# schem.net
KiCad netlist of a schematic drawn in EAGLE
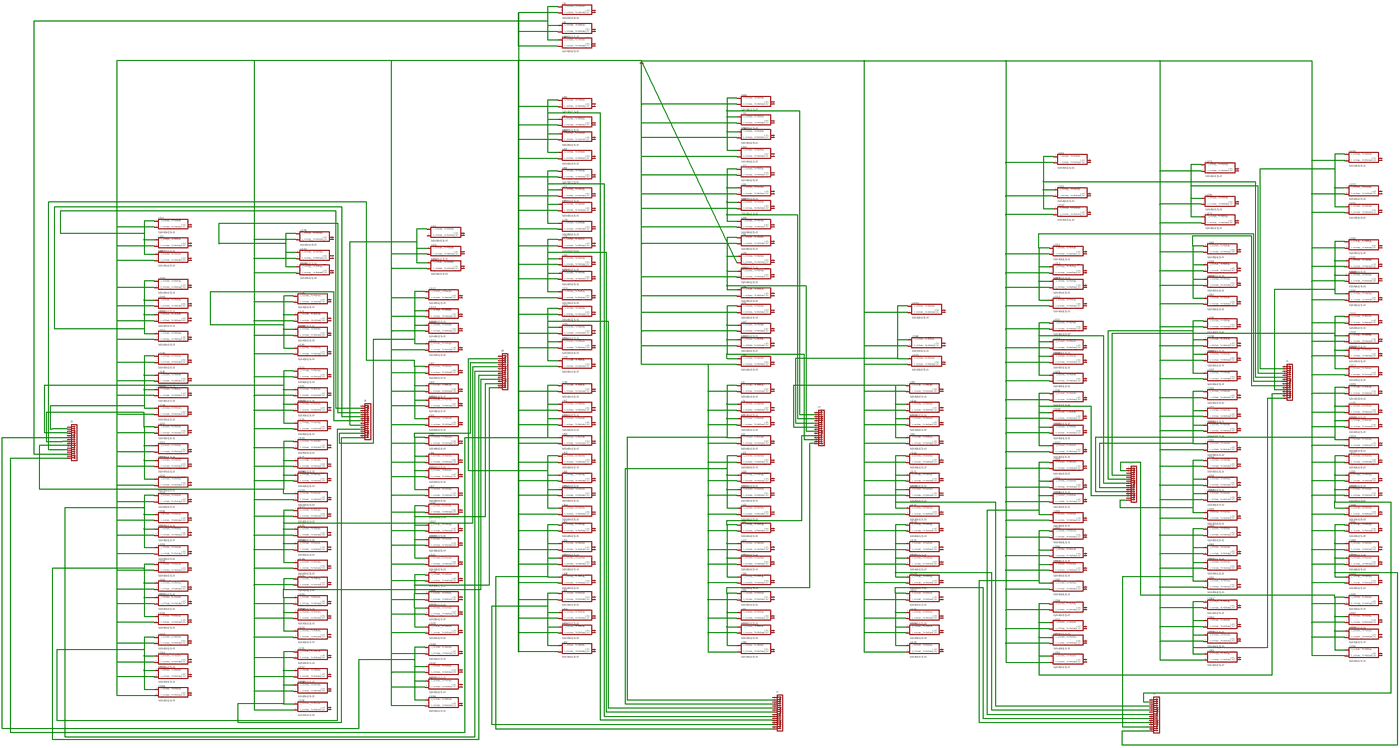
[diagram p0: schematic, sheet 1, overview]
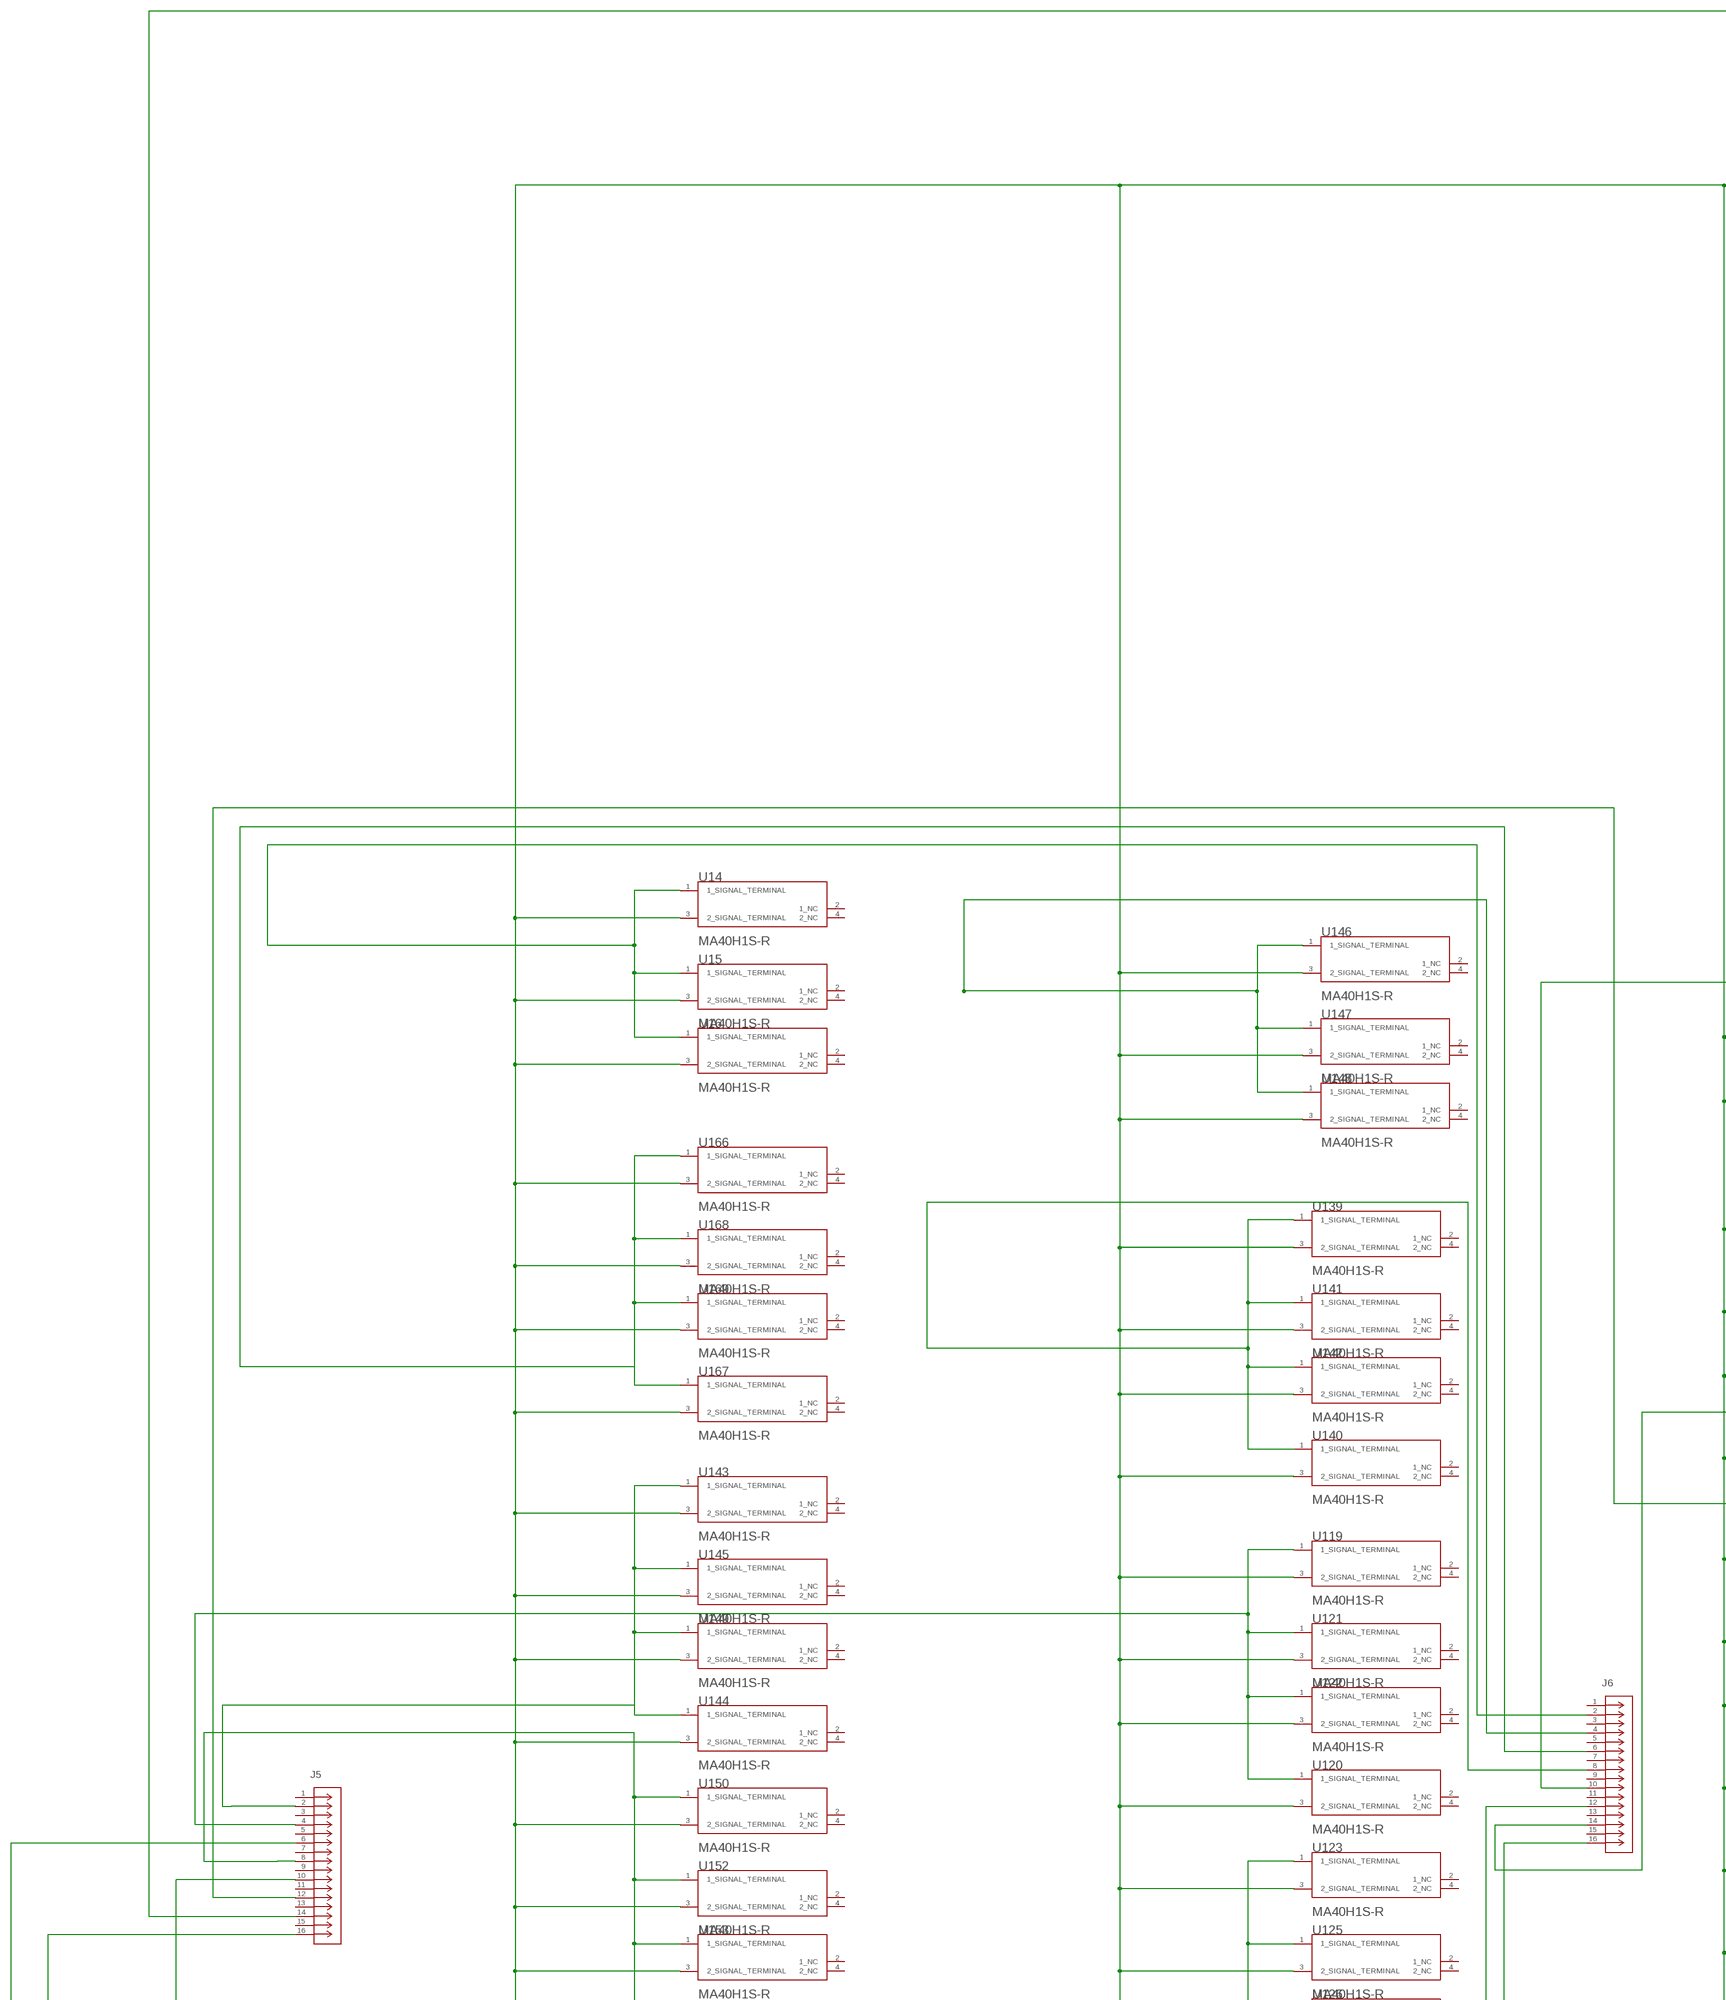
[diagram p1: schematic, sheet 1, part 1 of 8]
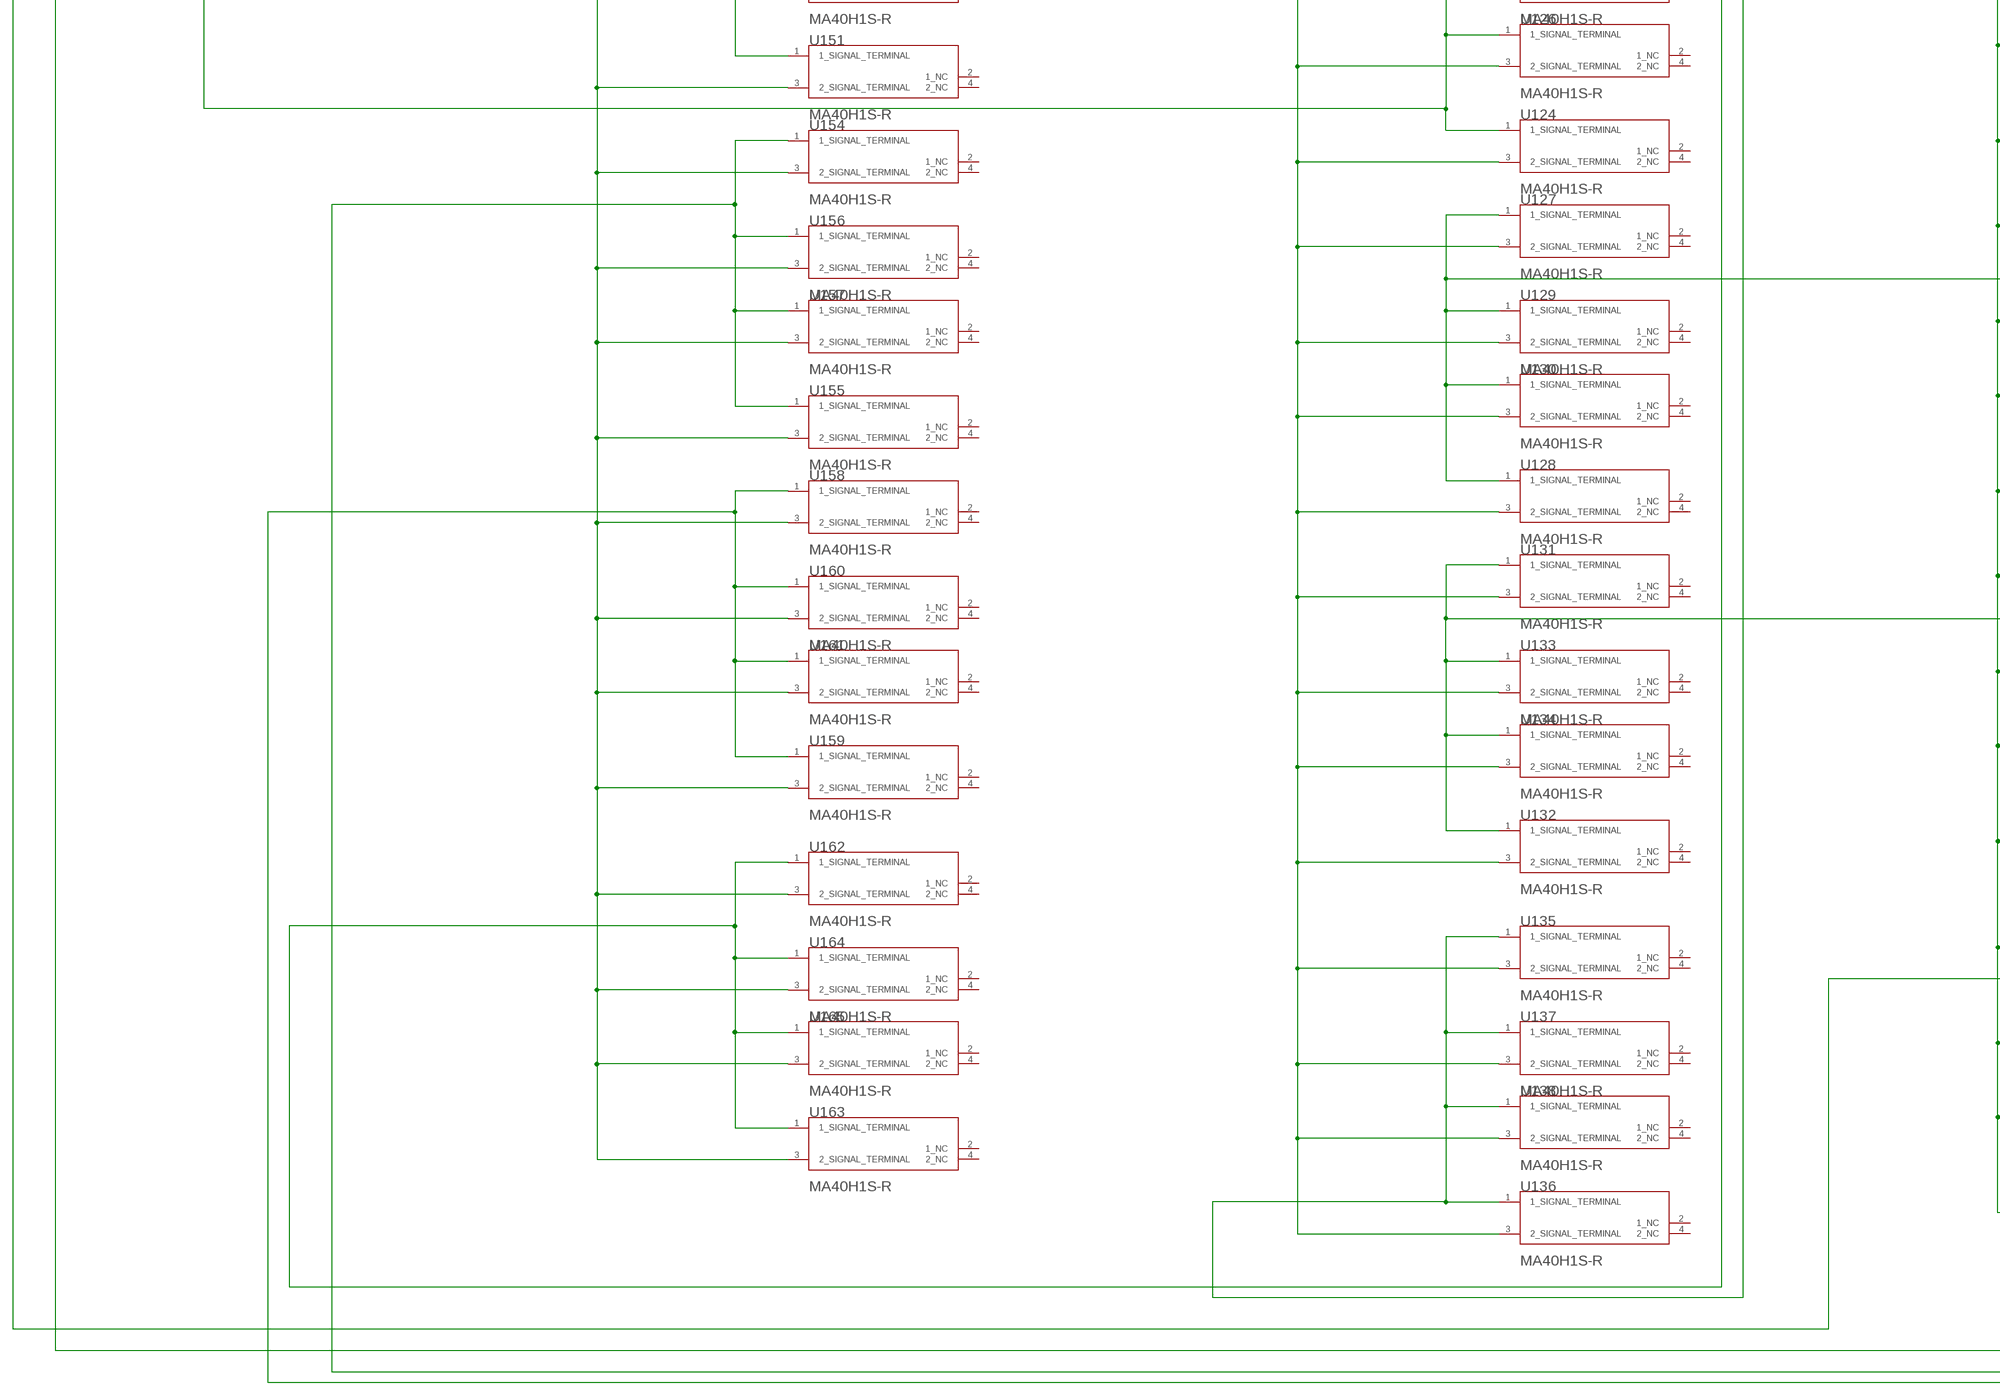
[diagram p2: schematic, sheet 1, part 2 of 8]
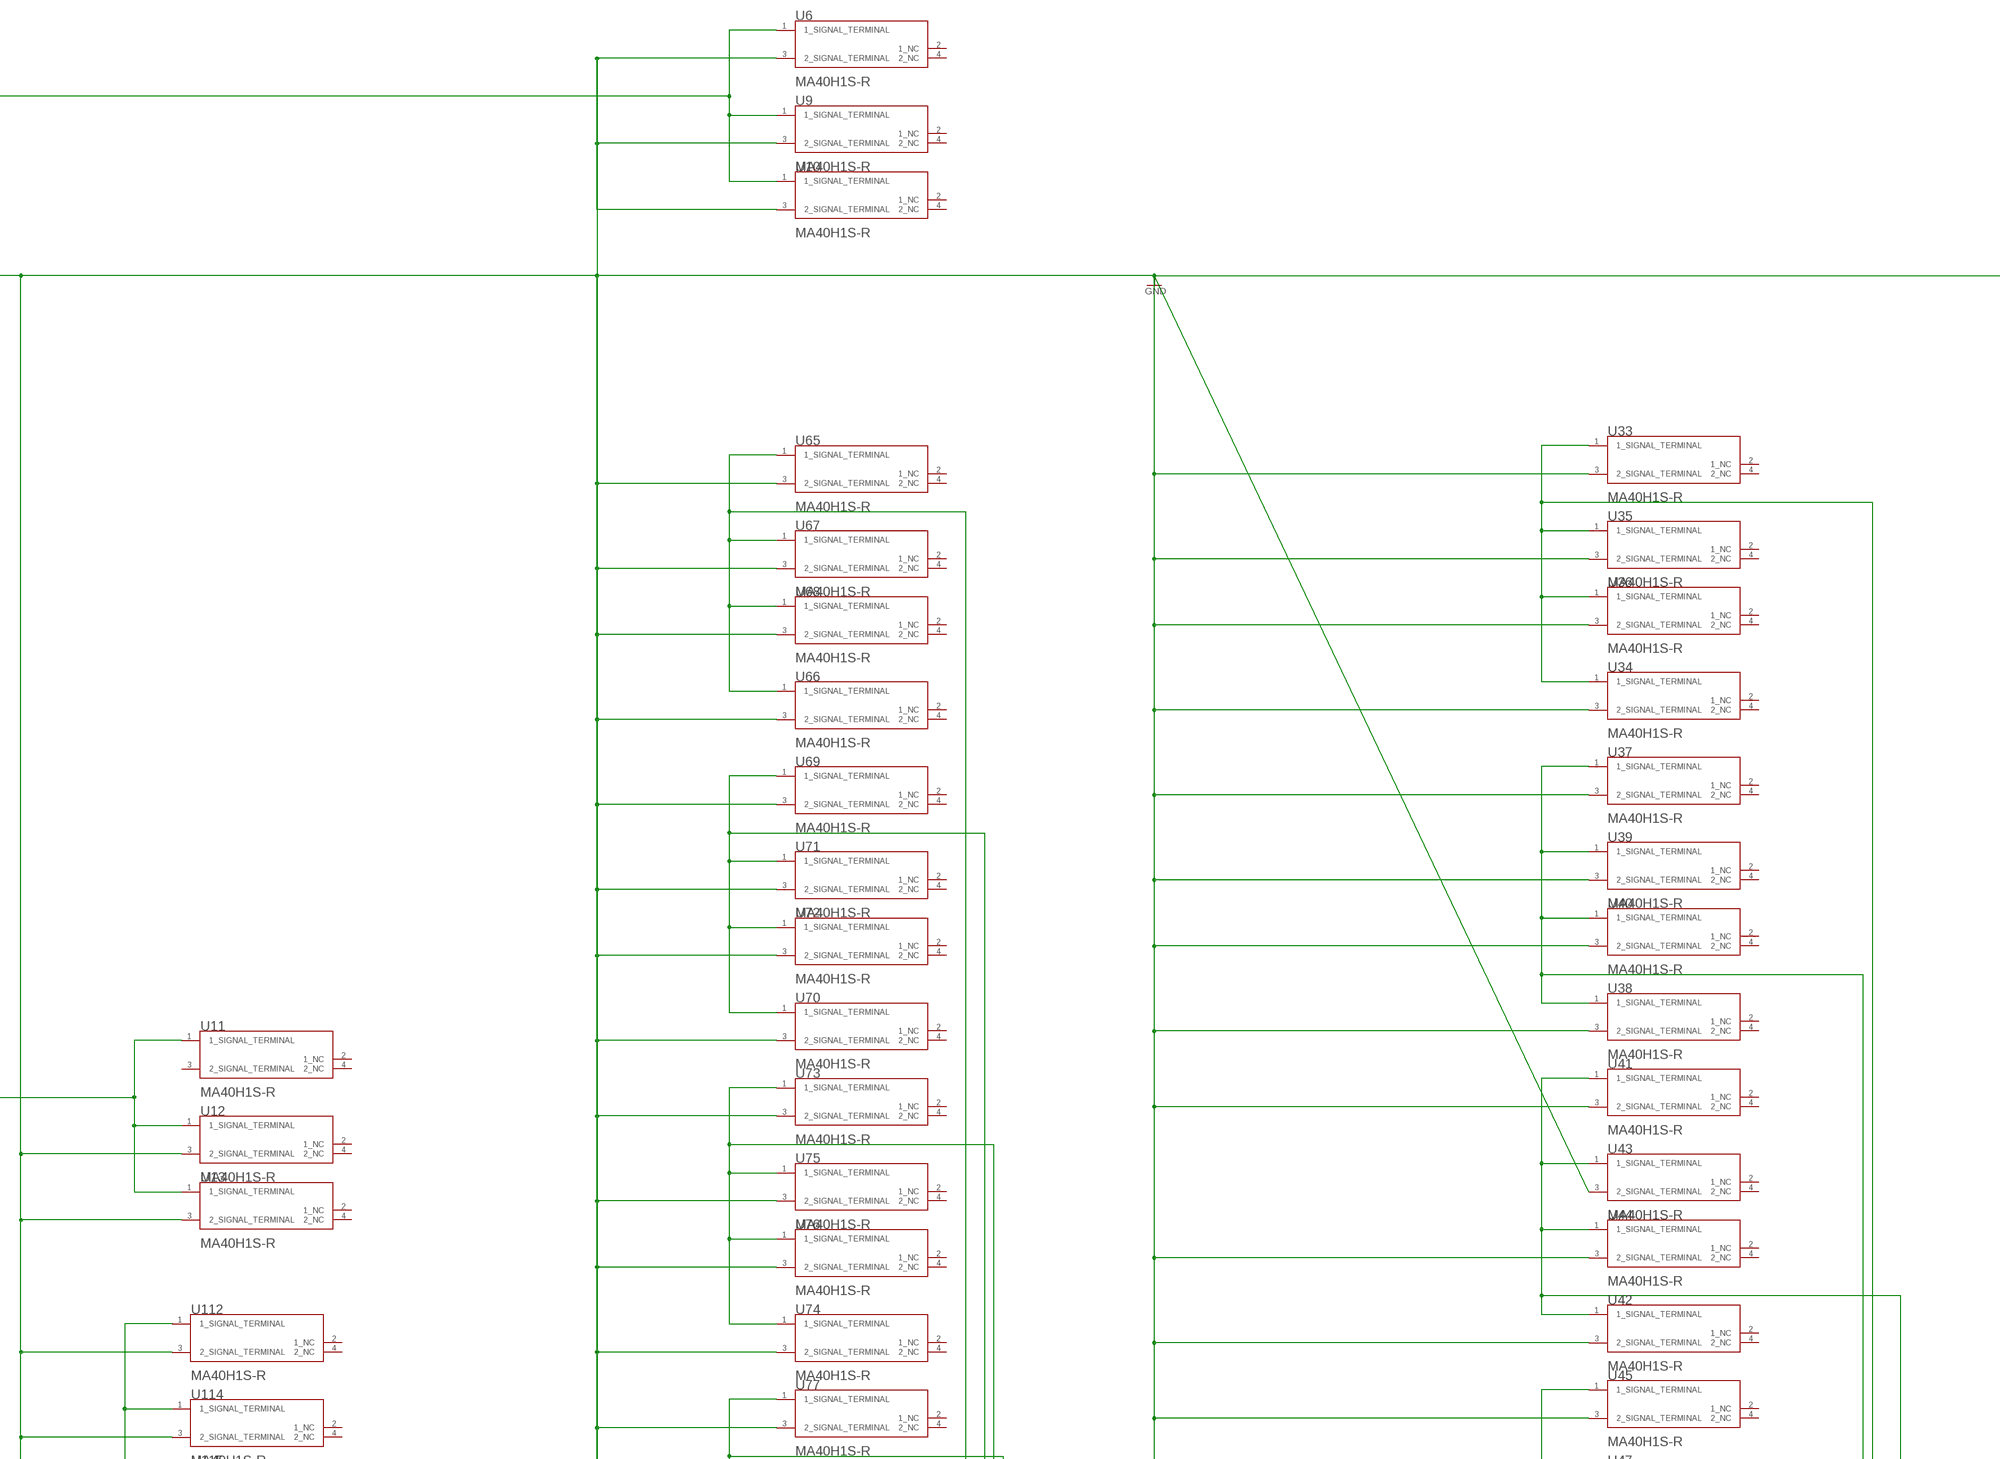
[diagram p3: schematic, sheet 1, part 3 of 8]
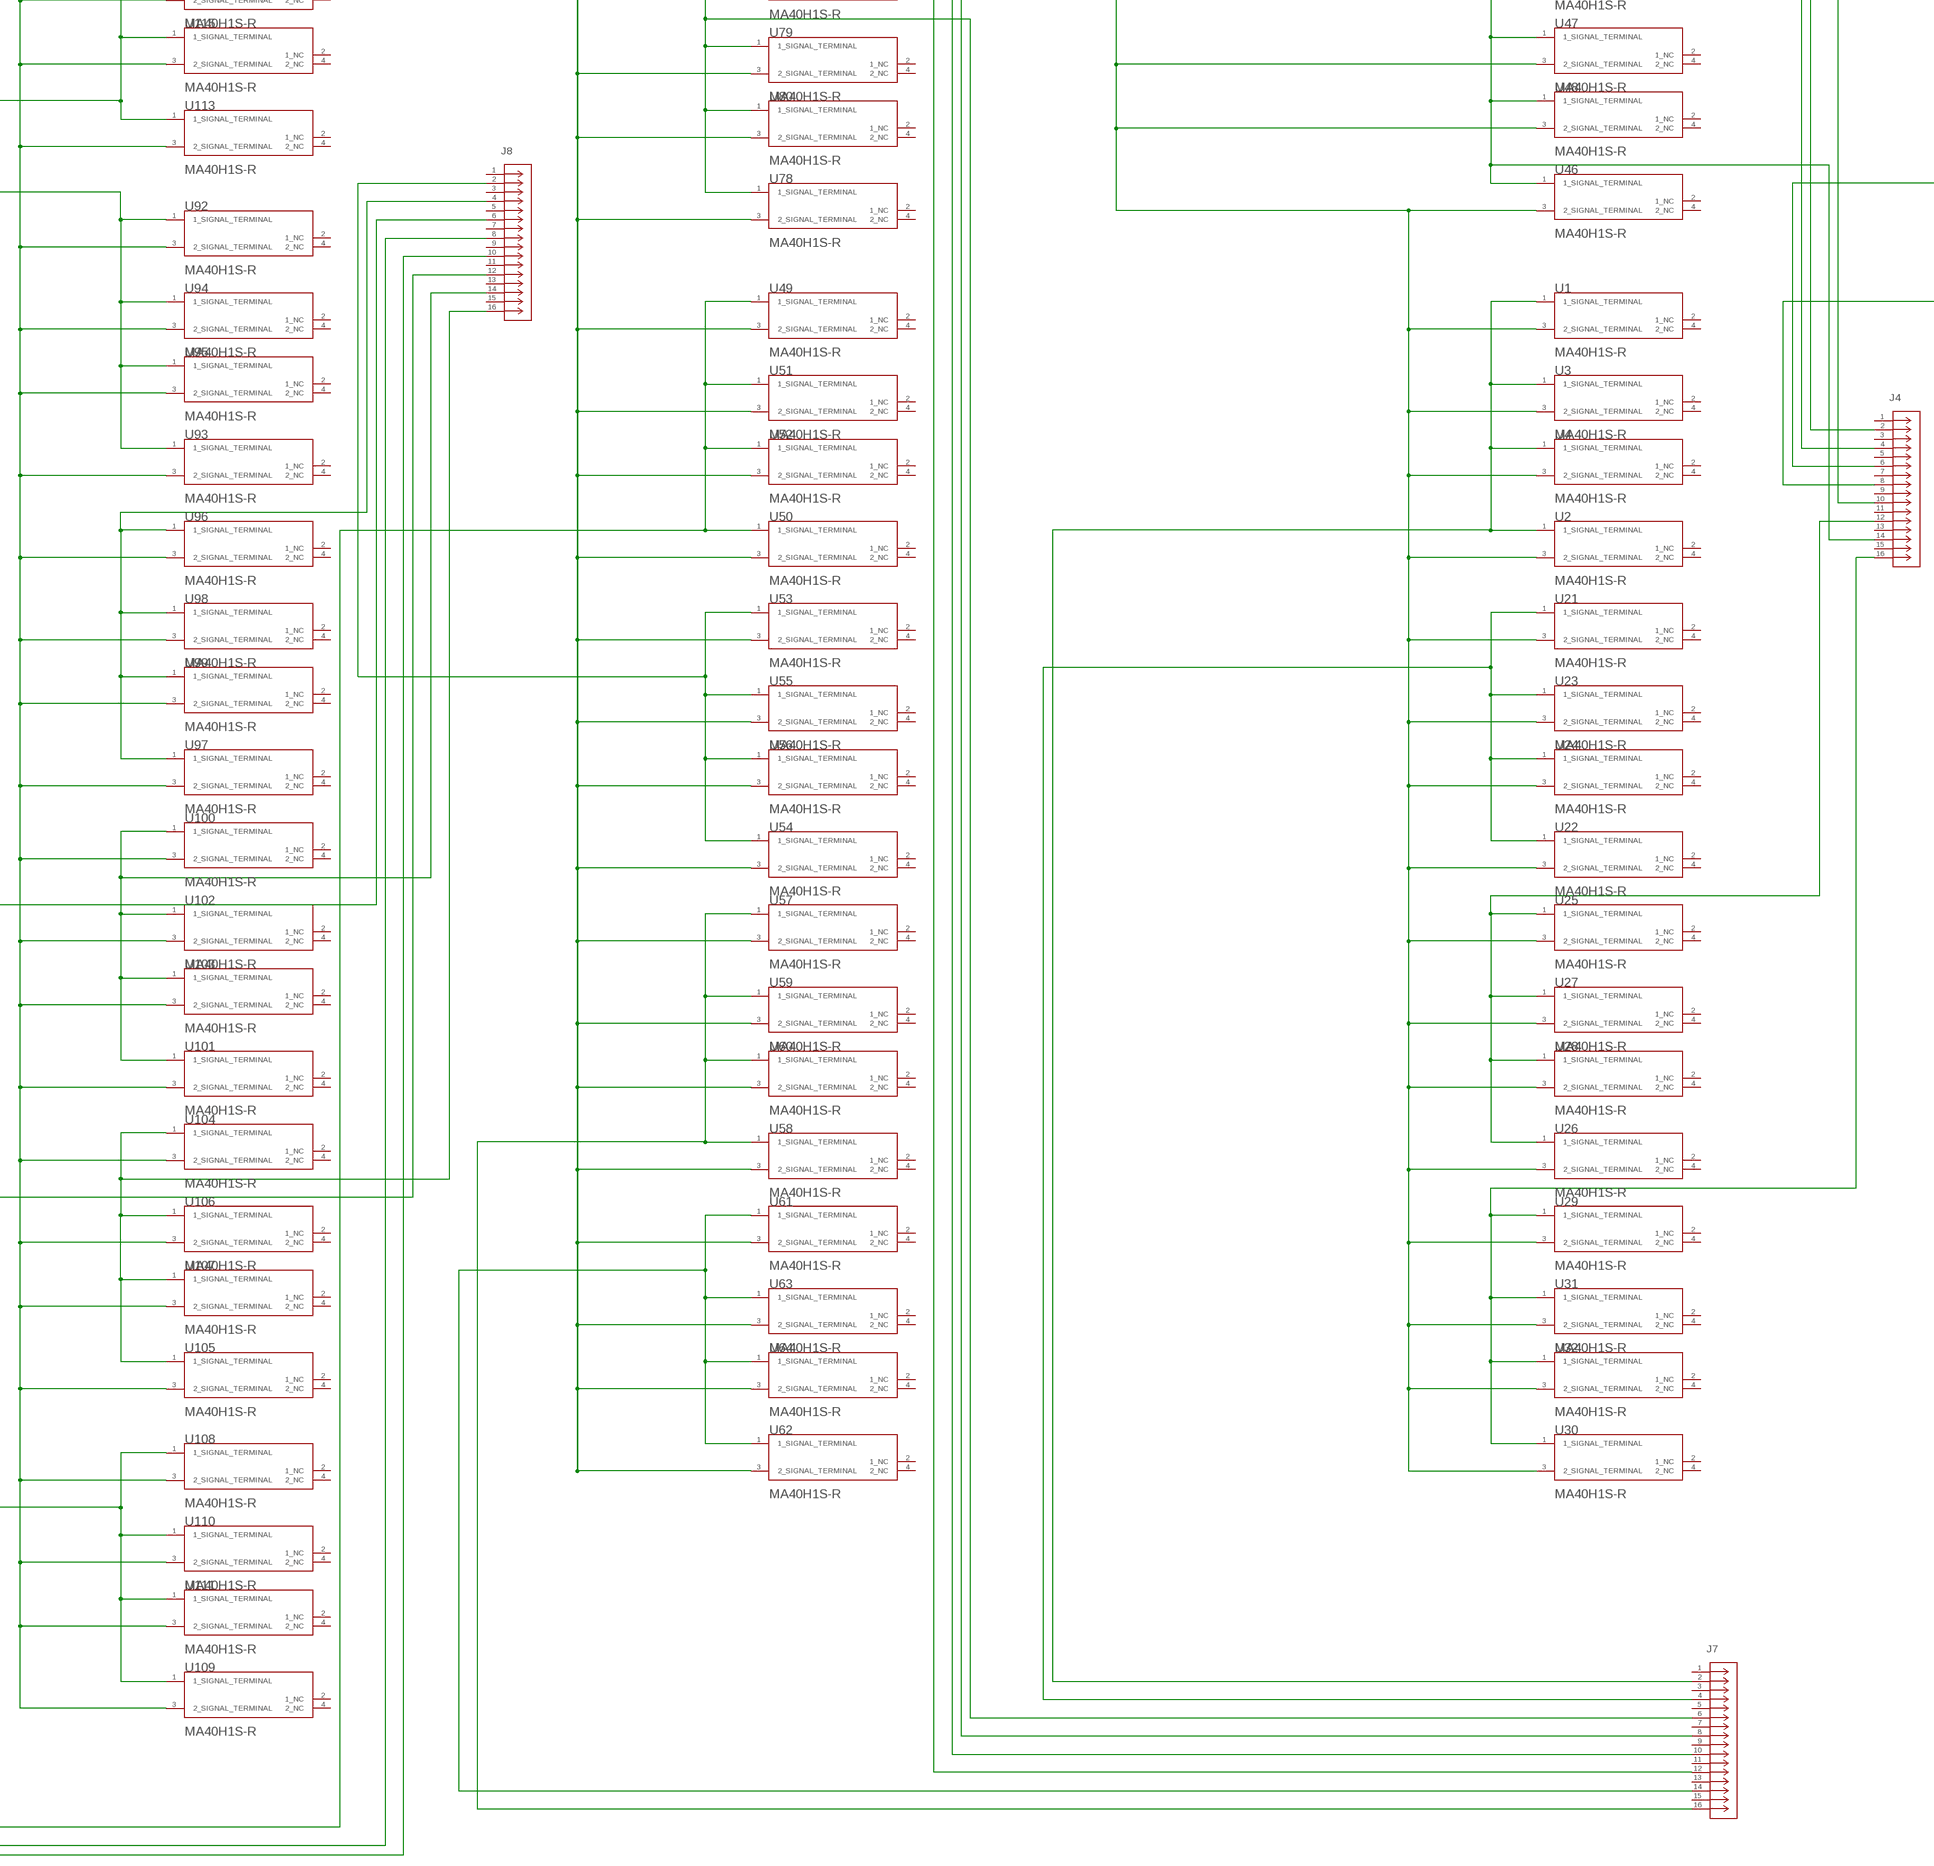
[diagram p4: schematic, sheet 1, part 4 of 8]
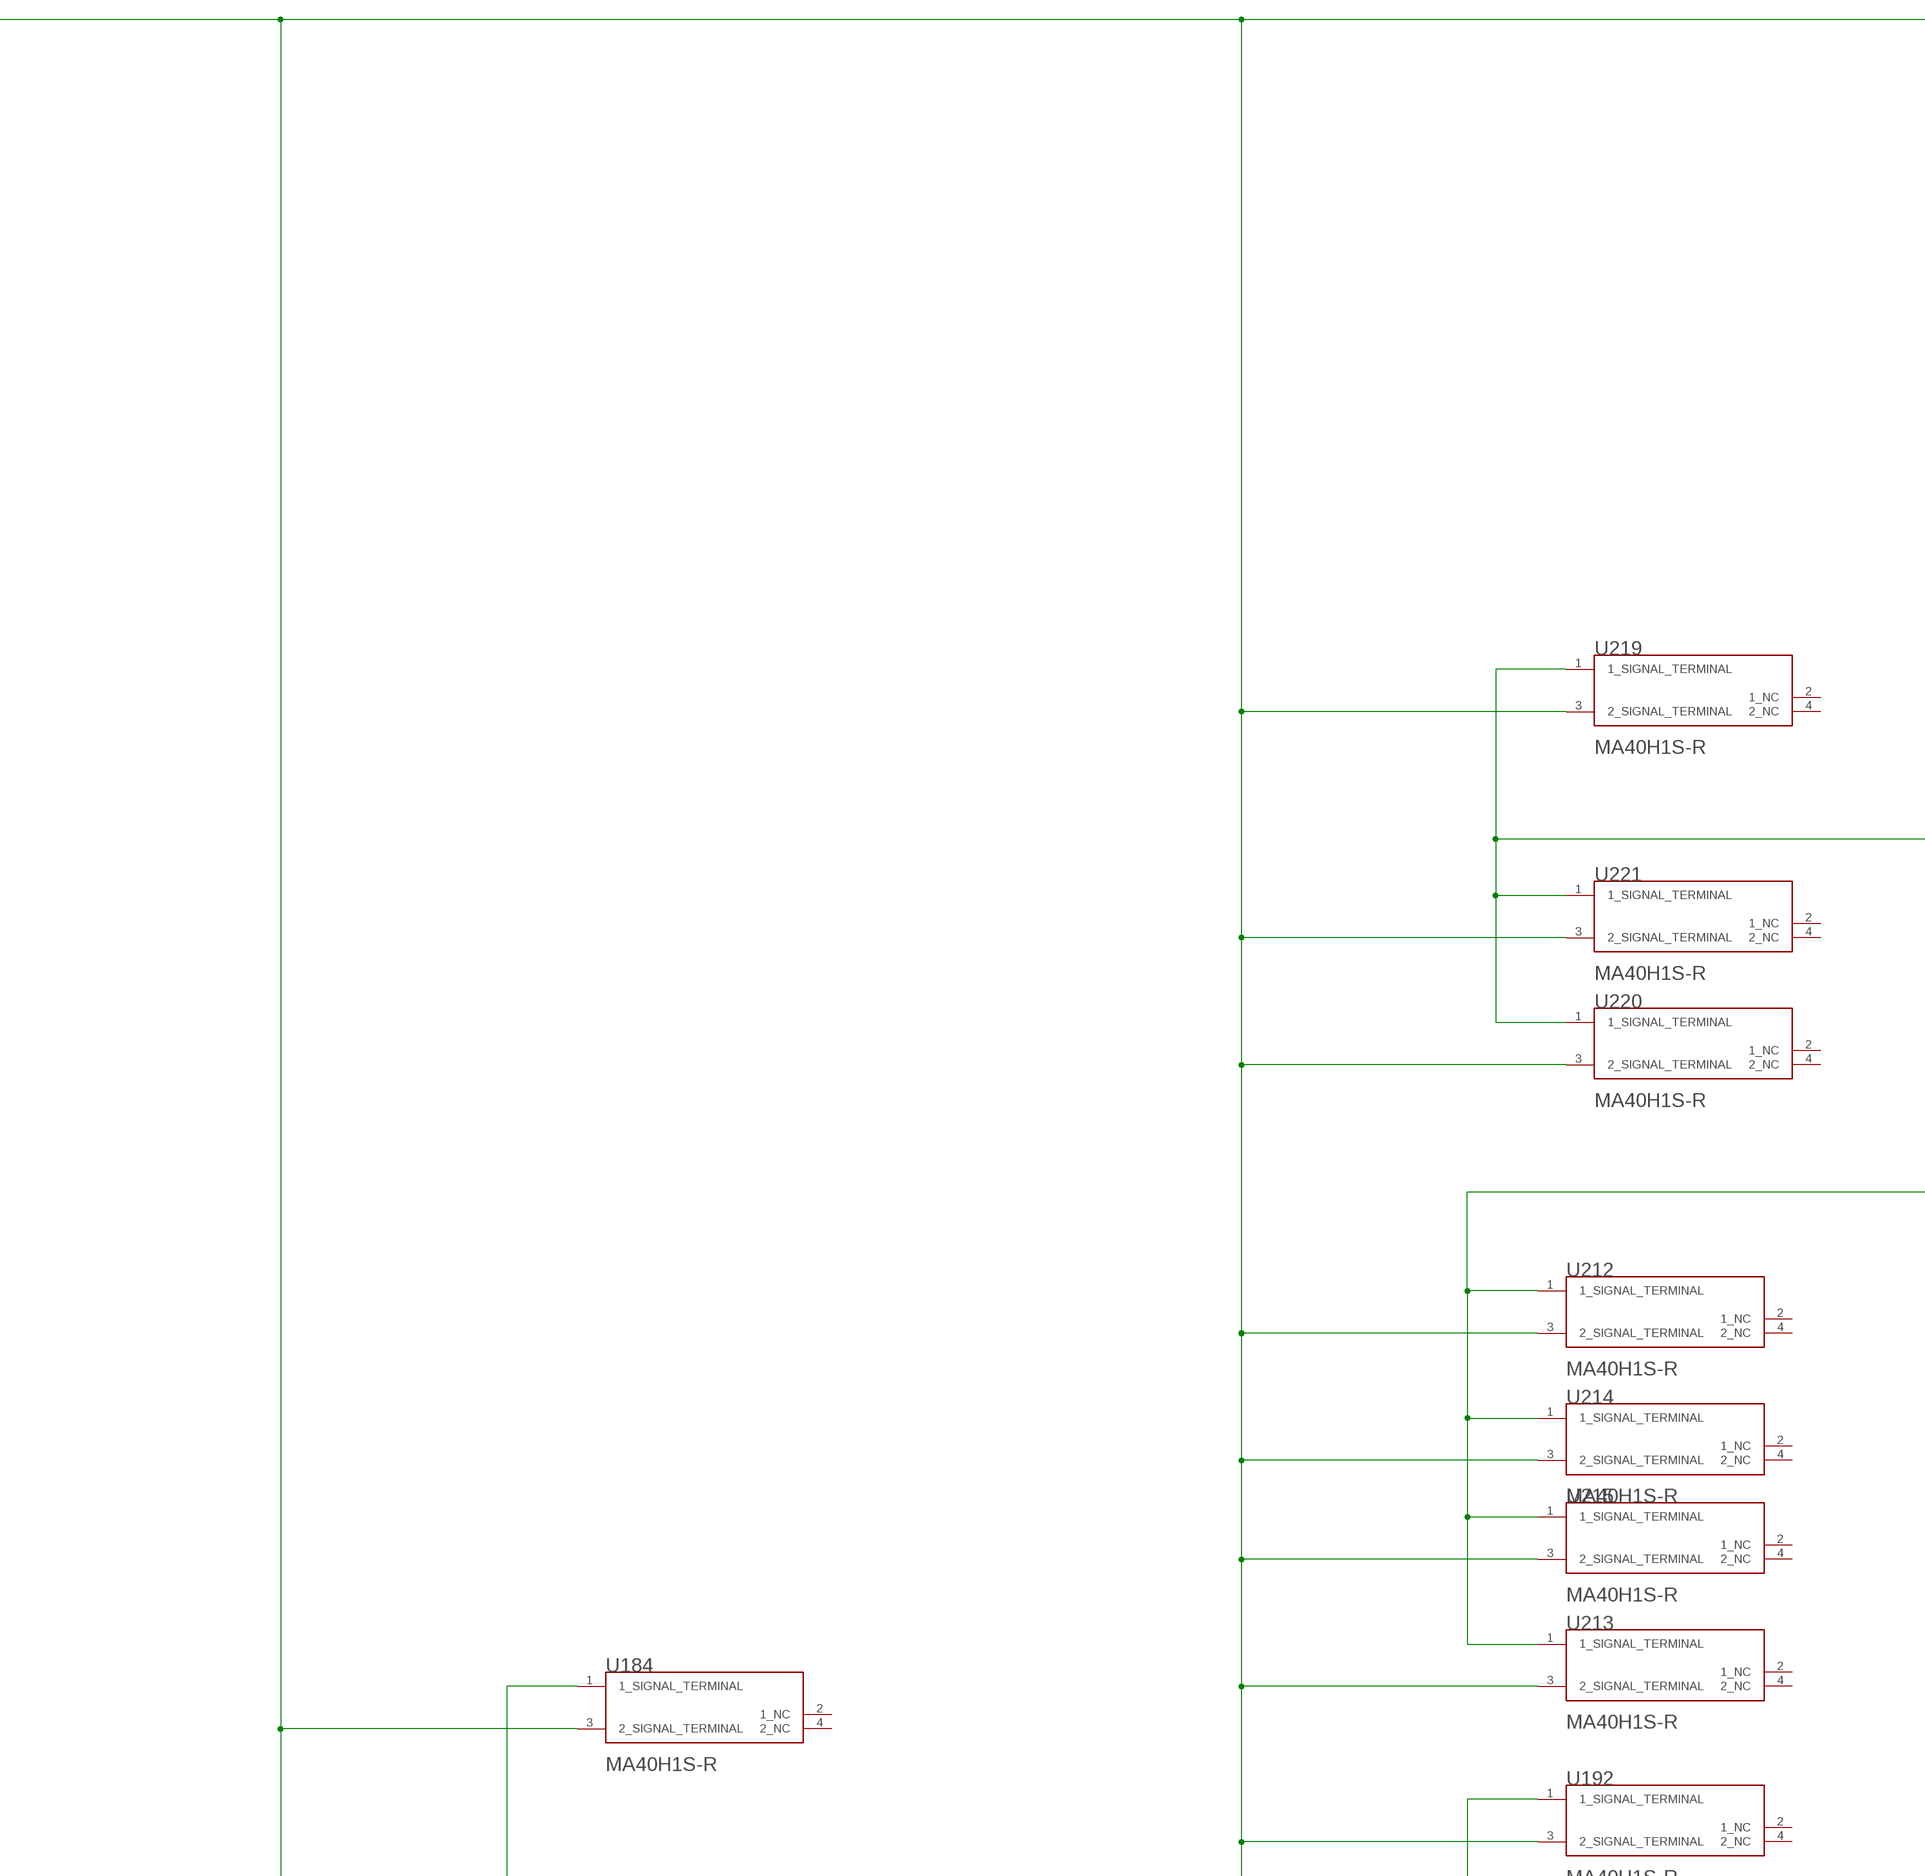
[diagram p5: schematic, sheet 1, part 5 of 8]
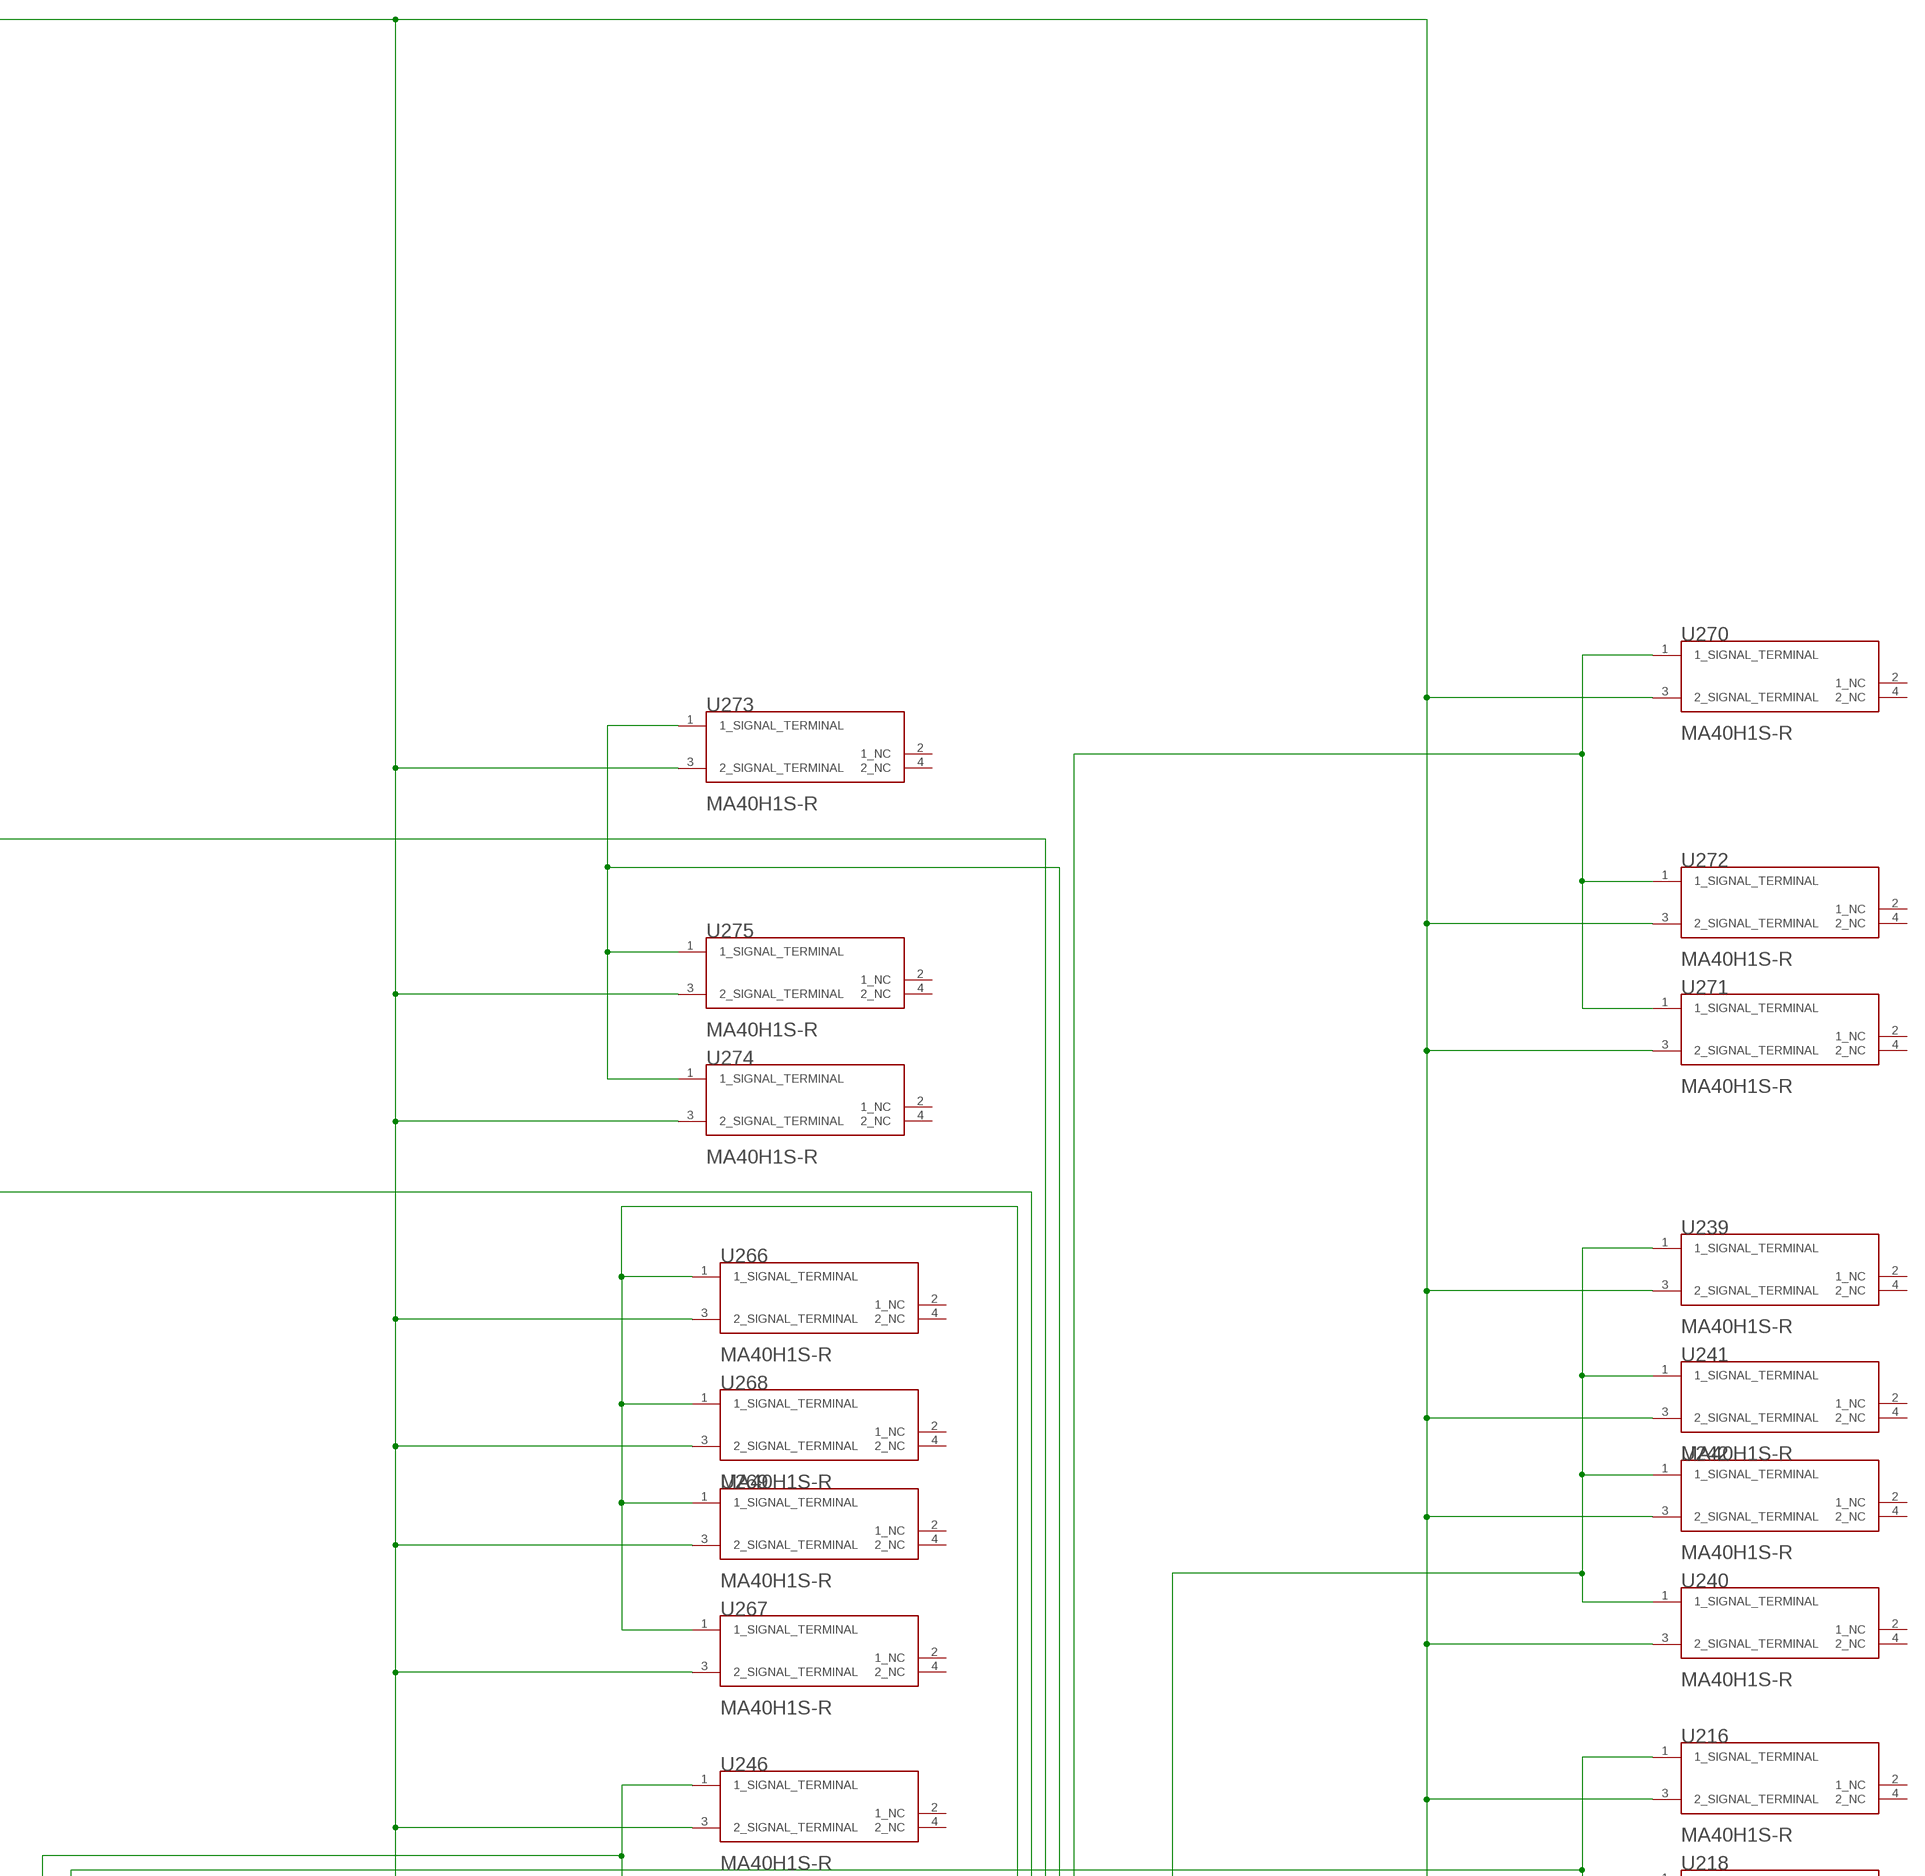
[diagram p6: schematic, sheet 1, part 6 of 8]
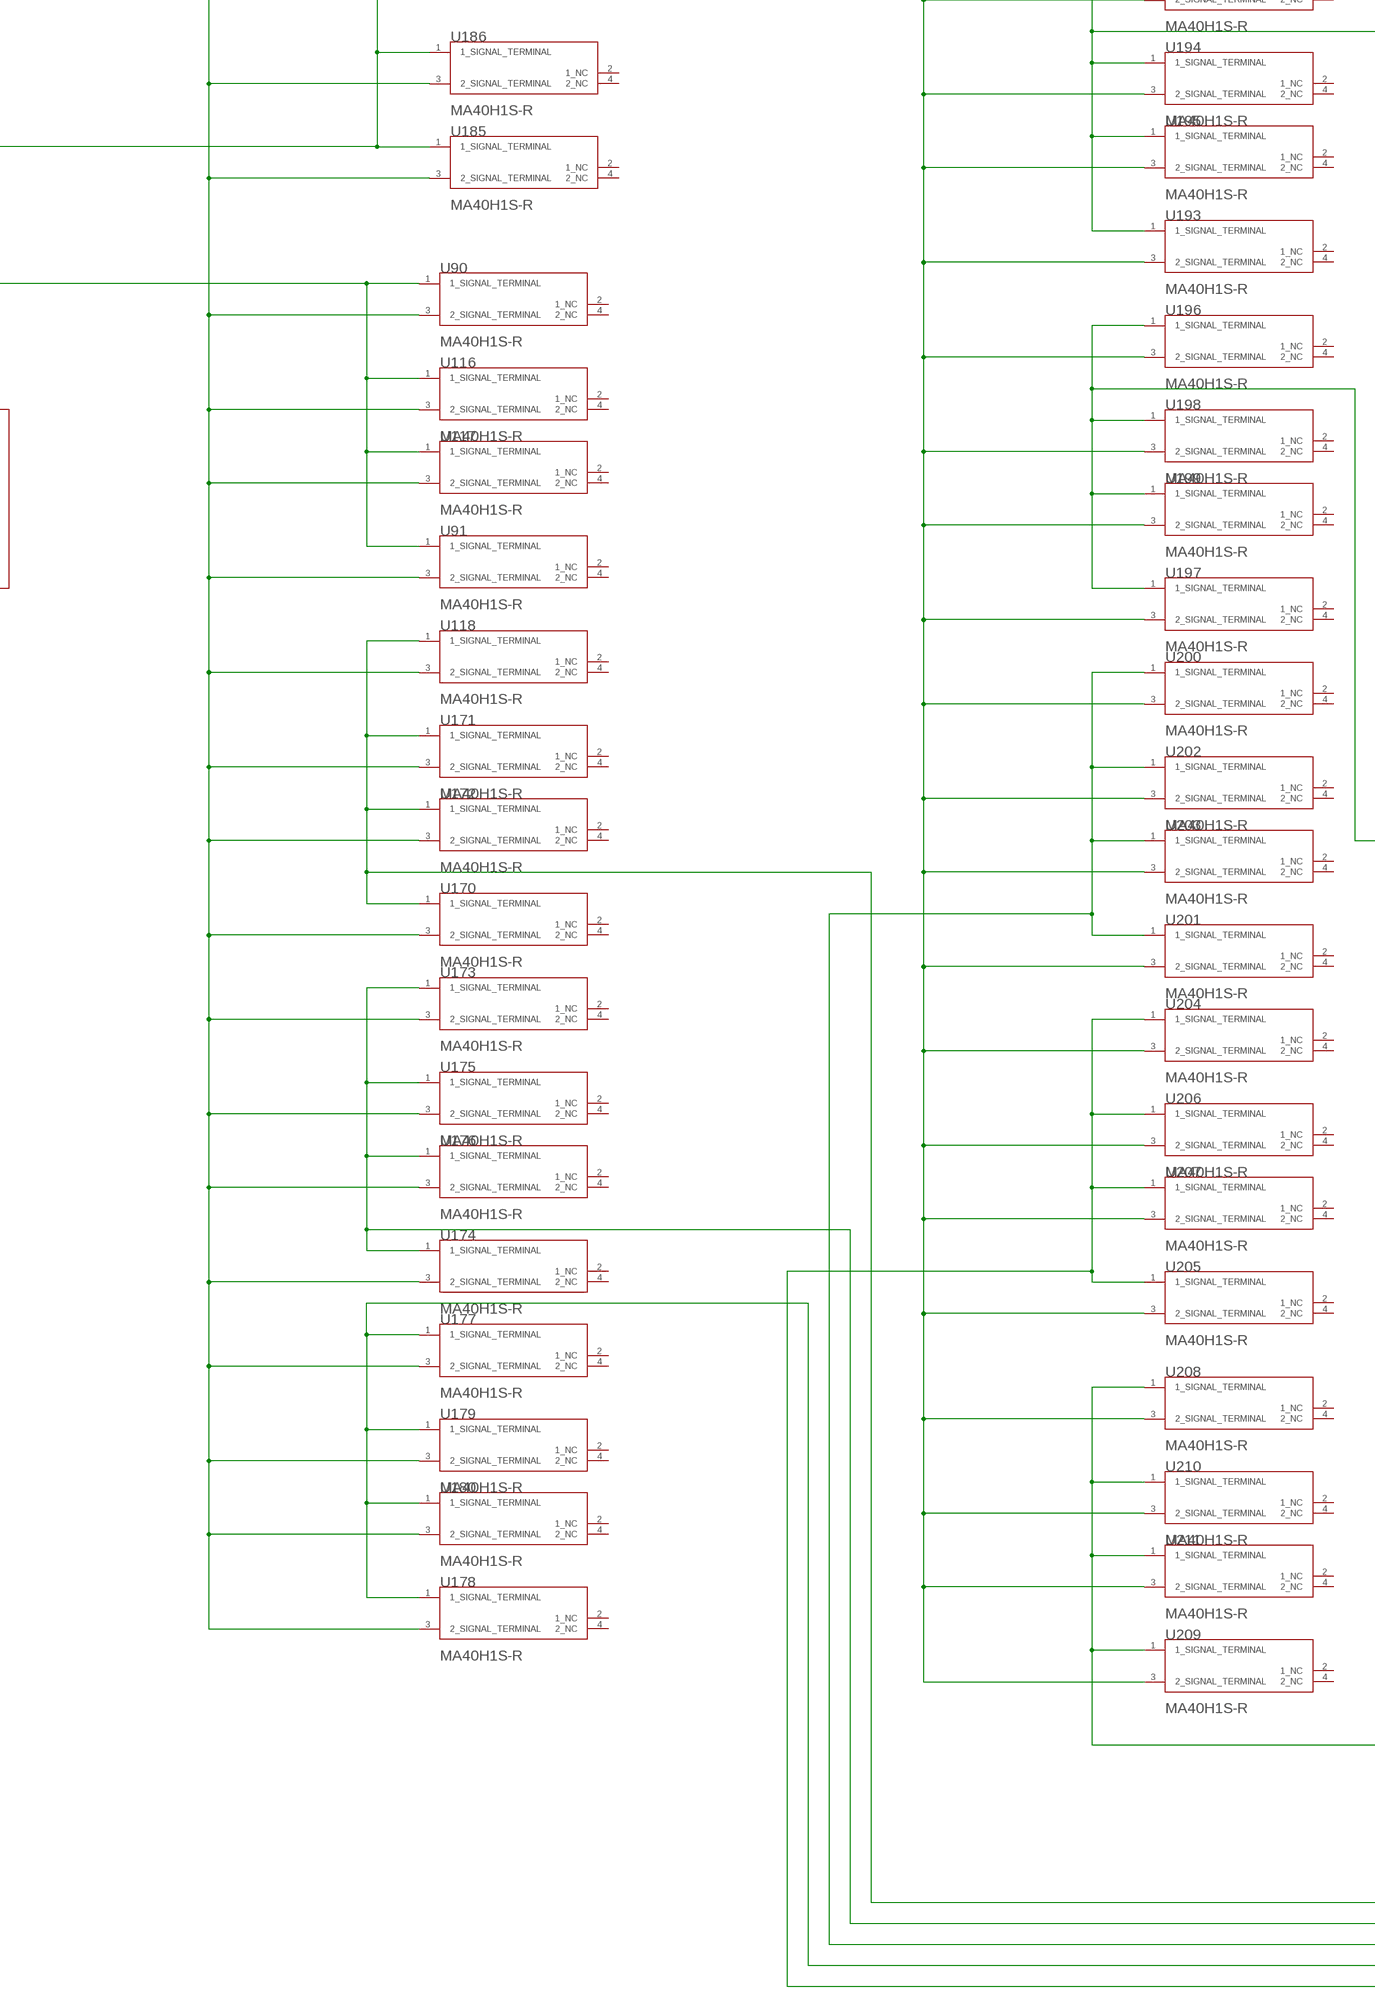
[diagram p7: schematic, sheet 1, part 7 of 8]
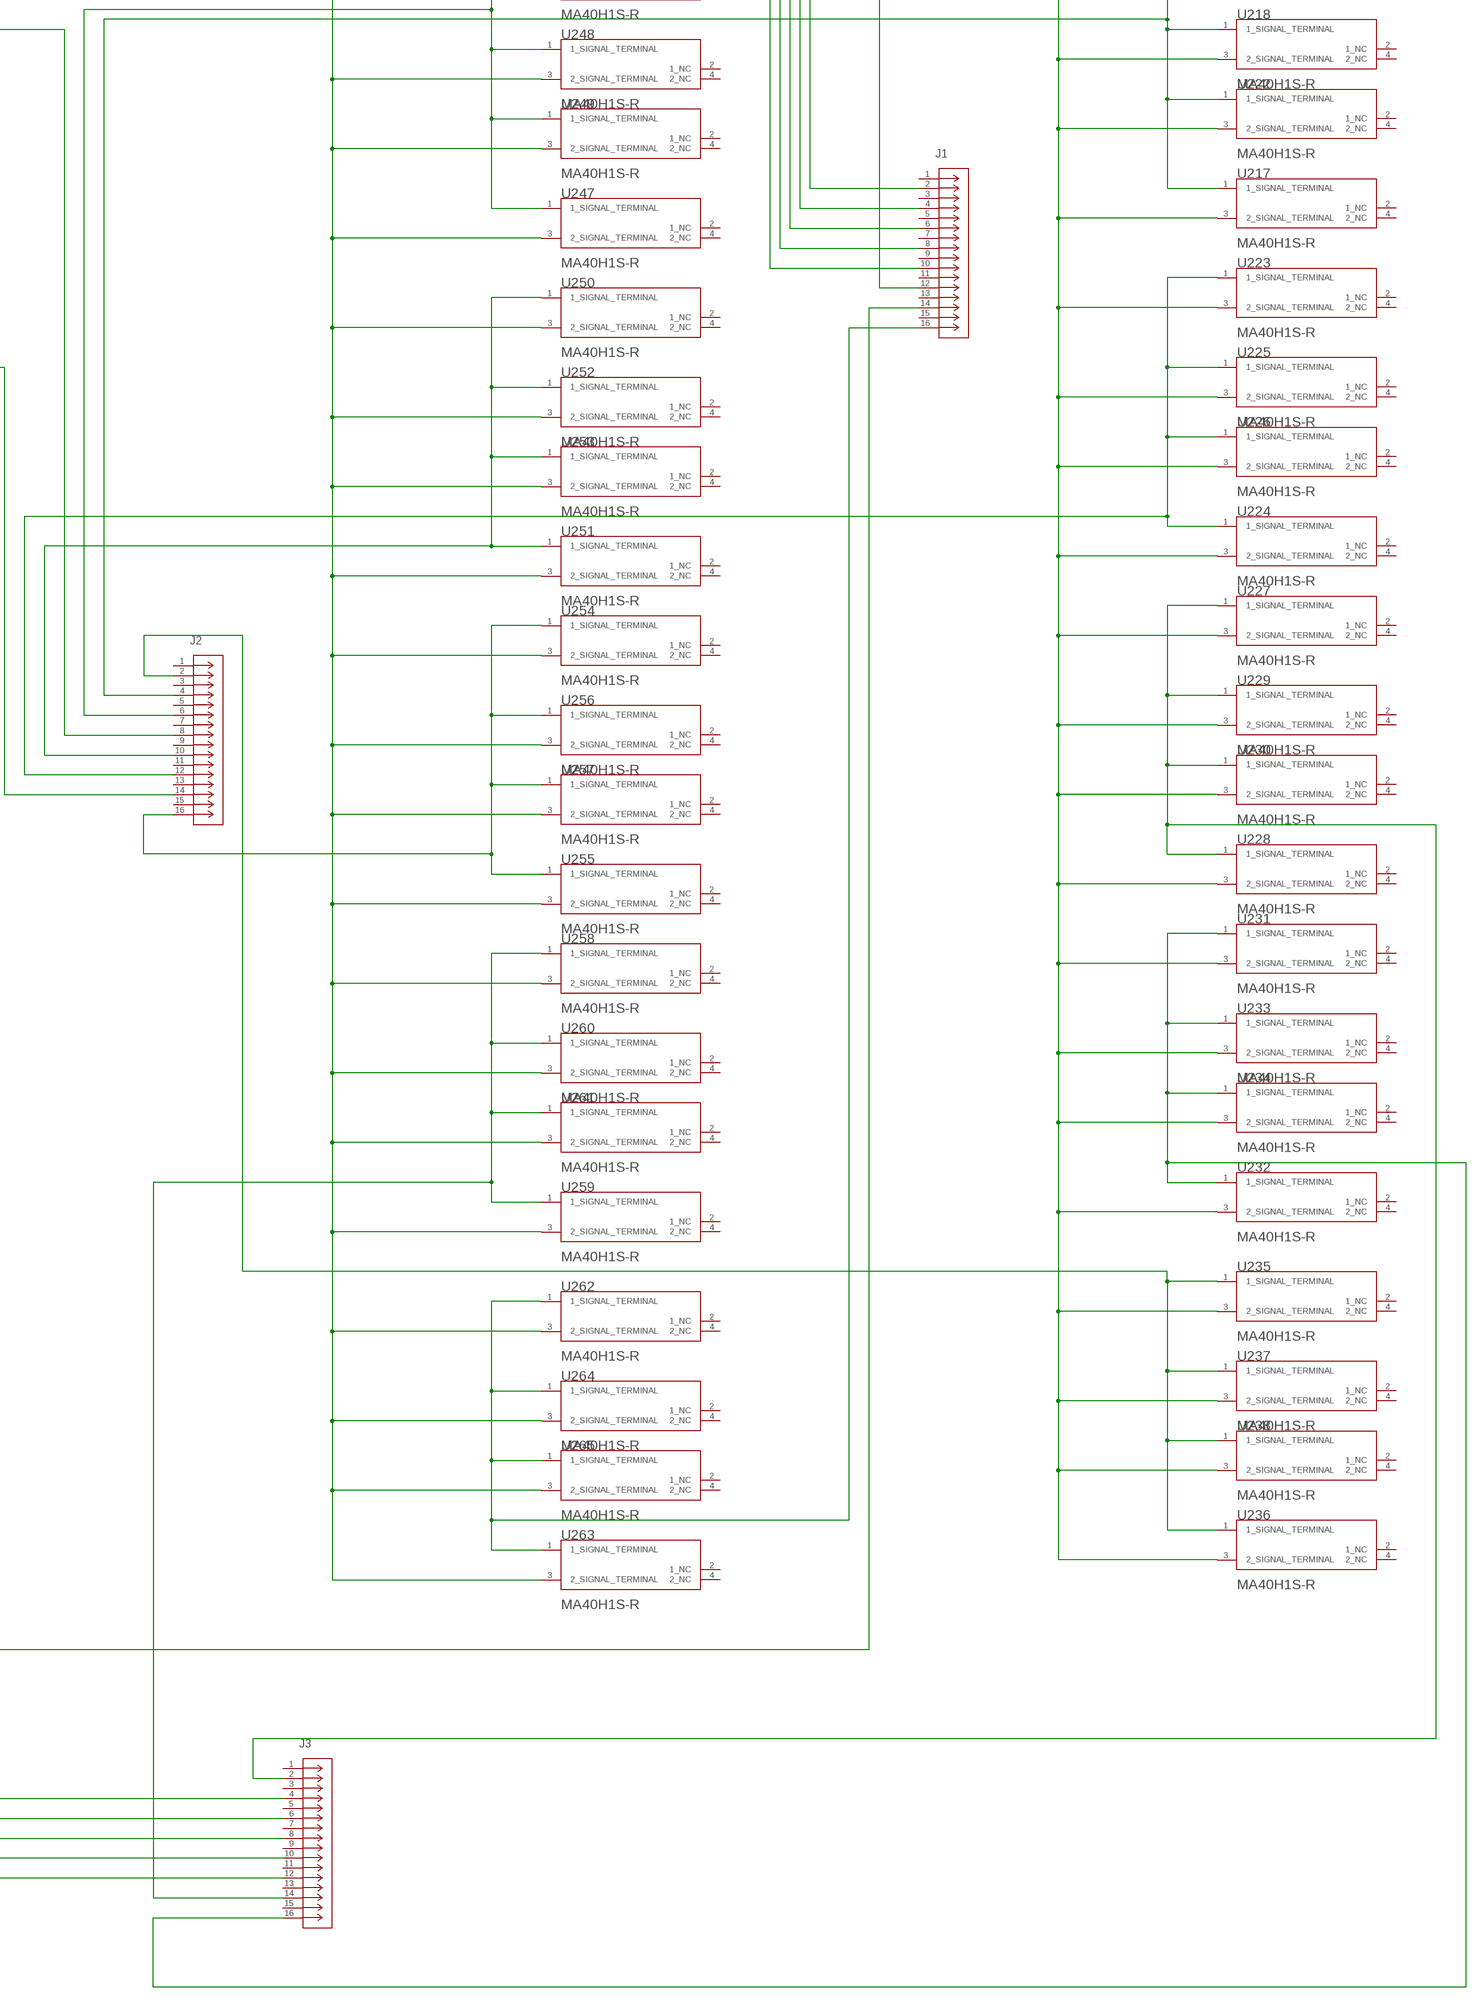
[diagram p8: schematic, sheet 1, part 8 of 8]

(export (version "E")
  (design (tool "Eeschema 10.0.6"))
  (components
    (comp (ref "J1")
      (value "70246-1201")
      (footprint "eagle-import:CONN_70246-1201_MOL")
      (fields (field (name "COPYRIGHT") "Copyright (C) 2018 Accelerated Designs. All rights reserved"))
      (libsource (lib "eagle-import") (part "70246-1201"))
    )
    (comp (ref "J2")
      (value "70246-1201")
      (footprint "eagle-import:CONN_70246-1201_MOL")
      (fields (field (name "COPYRIGHT") "Copyright (C) 2018 Accelerated Designs. All rights reserved"))
      (libsource (lib "eagle-import") (part "70246-1201"))
    )
    (comp (ref "J3")
      (value "70246-1201")
      (footprint "eagle-import:CONN_70246-1201_MOL")
      (fields (field (name "COPYRIGHT") "Copyright (C) 2018 Accelerated Designs. All rights reserved"))
      (libsource (lib "eagle-import") (part "70246-1201"))
    )
    (comp (ref "J4")
      (value "70246-1201")
      (footprint "eagle-import:CONN_70246-1201_MOL")
      (fields (field (name "COPYRIGHT") "Copyright (C) 2018 Accelerated Designs. All rights reserved"))
      (libsource (lib "eagle-import") (part "70246-1201"))
    )
    (comp (ref "J5")
      (value "70246-1201")
      (footprint "eagle-import:CONN_70246-1201_MOL")
      (fields (field (name "COPYRIGHT") "Copyright (C) 2018 Accelerated Designs. All rights reserved"))
      (libsource (lib "eagle-import") (part "70246-1201"))
    )
    (comp (ref "J6")
      (value "70246-1201")
      (footprint "eagle-import:CONN_70246-1201_MOL")
      (fields (field (name "COPYRIGHT") "Copyright (C) 2018 Accelerated Designs. All rights reserved"))
      (libsource (lib "eagle-import") (part "70246-1201"))
    )
    (comp (ref "J7")
      (value "70246-1201")
      (footprint "eagle-import:CONN_70246-1201_MOL")
      (fields (field (name "COPYRIGHT") "Copyright (C) 2018 Accelerated Designs. All rights reserved"))
      (libsource (lib "eagle-import") (part "70246-1201"))
    )
    (comp (ref "J8")
      (value "70246-1201")
      (footprint "eagle-import:CONN_70246-1201_MOL")
      (fields (field (name "COPYRIGHT") "Copyright (C) 2018 Accelerated Designs. All rights reserved"))
      (libsource (lib "eagle-import") (part "70246-1201"))
    )
    (comp (ref "U1")
      (value "MURATA_MA40H1S-RMURATA_MA40H1S-R_0_0")
      (footprint "eagle-import:MURATA_MA40H1S-R_0")
      (fields
        (field (name "DIGIKEY_PART_NUMBER") "490-MA40H1S-RCT-ND")
        (field (name "MF") "Murata")
        (field (name "MOUSER_PART_NUMBER") "81-MA40H1S-R")
      )
      (libsource (lib "eagle-import") (part "MURATA_MA40H1S-RMURATA_MA40H1S-R_0_0"))
    )
    (comp (ref "U2")
      (value "MURATA_MA40H1S-RMURATA_MA40H1S-R_0_0")
      (footprint "eagle-import:MURATA_MA40H1S-R_0")
      (fields
        (field (name "DIGIKEY_PART_NUMBER") "490-MA40H1S-RCT-ND")
        (field (name "MF") "Murata")
        (field (name "MOUSER_PART_NUMBER") "81-MA40H1S-R")
      )
      (libsource (lib "eagle-import") (part "MURATA_MA40H1S-RMURATA_MA40H1S-R_0_0"))
    )
    (comp (ref "U3")
      (value "MURATA_MA40H1S-RMURATA_MA40H1S-R_0_0")
      (footprint "eagle-import:MURATA_MA40H1S-R_0")
      (fields
        (field (name "DIGIKEY_PART_NUMBER") "490-MA40H1S-RCT-ND")
        (field (name "MF") "Murata")
        (field (name "MOUSER_PART_NUMBER") "81-MA40H1S-R")
      )
      (libsource (lib "eagle-import") (part "MURATA_MA40H1S-RMURATA_MA40H1S-R_0_0"))
    )
    (comp (ref "U4")
      (value "MURATA_MA40H1S-RMURATA_MA40H1S-R_0_0")
      (footprint "eagle-import:MURATA_MA40H1S-R_0")
      (fields
        (field (name "DIGIKEY_PART_NUMBER") "490-MA40H1S-RCT-ND")
        (field (name "MF") "Murata")
        (field (name "MOUSER_PART_NUMBER") "81-MA40H1S-R")
      )
      (libsource (lib "eagle-import") (part "MURATA_MA40H1S-RMURATA_MA40H1S-R_0_0"))
    )
    (comp (ref "U6")
      (value "MURATA_MA40H1S-RMURATA_MA40H1S-R_0_0")
      (footprint "eagle-import:MURATA_MA40H1S-R_0")
      (fields
        (field (name "DIGIKEY_PART_NUMBER") "490-MA40H1S-RCT-ND")
        (field (name "MF") "Murata")
        (field (name "MOUSER_PART_NUMBER") "81-MA40H1S-R")
      )
      (libsource (lib "eagle-import") (part "MURATA_MA40H1S-RMURATA_MA40H1S-R_0_0"))
    )
    (comp (ref "U9")
      (value "MURATA_MA40H1S-RMURATA_MA40H1S-R_0_0")
      (footprint "eagle-import:MURATA_MA40H1S-R_0")
      (fields
        (field (name "DIGIKEY_PART_NUMBER") "490-MA40H1S-RCT-ND")
        (field (name "MF") "Murata")
        (field (name "MOUSER_PART_NUMBER") "81-MA40H1S-R")
      )
      (libsource (lib "eagle-import") (part "MURATA_MA40H1S-RMURATA_MA40H1S-R_0_0"))
    )
    (comp (ref "U10")
      (value "MURATA_MA40H1S-RMURATA_MA40H1S-R_0_0")
      (footprint "eagle-import:MURATA_MA40H1S-R_0")
      (fields
        (field (name "DIGIKEY_PART_NUMBER") "490-MA40H1S-RCT-ND")
        (field (name "MF") "Murata")
        (field (name "MOUSER_PART_NUMBER") "81-MA40H1S-R")
      )
      (libsource (lib "eagle-import") (part "MURATA_MA40H1S-RMURATA_MA40H1S-R_0_0"))
    )
    (comp (ref "U11")
      (value "MURATA_MA40H1S-RMURATA_MA40H1S-R_0_0")
      (footprint "eagle-import:MURATA_MA40H1S-R_0")
      (fields
        (field (name "DIGIKEY_PART_NUMBER") "490-MA40H1S-RCT-ND")
        (field (name "MF") "Murata")
        (field (name "MOUSER_PART_NUMBER") "81-MA40H1S-R")
      )
      (libsource (lib "eagle-import") (part "MURATA_MA40H1S-RMURATA_MA40H1S-R_0_0"))
    )
    (comp (ref "U12")
      (value "MURATA_MA40H1S-RMURATA_MA40H1S-R_0_0")
      (footprint "eagle-import:MURATA_MA40H1S-R_0")
      (fields
        (field (name "DIGIKEY_PART_NUMBER") "490-MA40H1S-RCT-ND")
        (field (name "MF") "Murata")
        (field (name "MOUSER_PART_NUMBER") "81-MA40H1S-R")
      )
      (libsource (lib "eagle-import") (part "MURATA_MA40H1S-RMURATA_MA40H1S-R_0_0"))
    )
    (comp (ref "U13")
      (value "MURATA_MA40H1S-RMURATA_MA40H1S-R_0_0")
      (footprint "eagle-import:MURATA_MA40H1S-R_0")
      (fields
        (field (name "DIGIKEY_PART_NUMBER") "490-MA40H1S-RCT-ND")
        (field (name "MF") "Murata")
        (field (name "MOUSER_PART_NUMBER") "81-MA40H1S-R")
      )
      (libsource (lib "eagle-import") (part "MURATA_MA40H1S-RMURATA_MA40H1S-R_0_0"))
    )
    (comp (ref "U14")
      (value "MURATA_MA40H1S-RMURATA_MA40H1S-R_0_0")
      (footprint "eagle-import:MURATA_MA40H1S-R_0")
      (fields
        (field (name "DIGIKEY_PART_NUMBER") "490-MA40H1S-RCT-ND")
        (field (name "MF") "Murata")
        (field (name "MOUSER_PART_NUMBER") "81-MA40H1S-R")
      )
      (libsource (lib "eagle-import") (part "MURATA_MA40H1S-RMURATA_MA40H1S-R_0_0"))
    )
    (comp (ref "U15")
      (value "MURATA_MA40H1S-RMURATA_MA40H1S-R_0_0")
      (footprint "eagle-import:MURATA_MA40H1S-R_0")
      (fields
        (field (name "DIGIKEY_PART_NUMBER") "490-MA40H1S-RCT-ND")
        (field (name "MF") "Murata")
        (field (name "MOUSER_PART_NUMBER") "81-MA40H1S-R")
      )
      (libsource (lib "eagle-import") (part "MURATA_MA40H1S-RMURATA_MA40H1S-R_0_0"))
    )
    (comp (ref "U16")
      (value "MURATA_MA40H1S-RMURATA_MA40H1S-R_0_0")
      (footprint "eagle-import:MURATA_MA40H1S-R_0")
      (fields
        (field (name "DIGIKEY_PART_NUMBER") "490-MA40H1S-RCT-ND")
        (field (name "MF") "Murata")
        (field (name "MOUSER_PART_NUMBER") "81-MA40H1S-R")
      )
      (libsource (lib "eagle-import") (part "MURATA_MA40H1S-RMURATA_MA40H1S-R_0_0"))
    )
    (comp (ref "U21")
      (value "MURATA_MA40H1S-RMURATA_MA40H1S-R_0_0")
      (footprint "eagle-import:MURATA_MA40H1S-R_0")
      (fields
        (field (name "DIGIKEY_PART_NUMBER") "490-MA40H1S-RCT-ND")
        (field (name "MF") "Murata")
        (field (name "MOUSER_PART_NUMBER") "81-MA40H1S-R")
      )
      (libsource (lib "eagle-import") (part "MURATA_MA40H1S-RMURATA_MA40H1S-R_0_0"))
    )
    (comp (ref "U22")
      (value "MURATA_MA40H1S-RMURATA_MA40H1S-R_0_0")
      (footprint "eagle-import:MURATA_MA40H1S-R_0")
      (fields
        (field (name "DIGIKEY_PART_NUMBER") "490-MA40H1S-RCT-ND")
        (field (name "MF") "Murata")
        (field (name "MOUSER_PART_NUMBER") "81-MA40H1S-R")
      )
      (libsource (lib "eagle-import") (part "MURATA_MA40H1S-RMURATA_MA40H1S-R_0_0"))
    )
    (comp (ref "U23")
      (value "MURATA_MA40H1S-RMURATA_MA40H1S-R_0_0")
      (footprint "eagle-import:MURATA_MA40H1S-R_0")
      (fields
        (field (name "DIGIKEY_PART_NUMBER") "490-MA40H1S-RCT-ND")
        (field (name "MF") "Murata")
        (field (name "MOUSER_PART_NUMBER") "81-MA40H1S-R")
      )
      (libsource (lib "eagle-import") (part "MURATA_MA40H1S-RMURATA_MA40H1S-R_0_0"))
    )
    (comp (ref "U24")
      (value "MURATA_MA40H1S-RMURATA_MA40H1S-R_0_0")
      (footprint "eagle-import:MURATA_MA40H1S-R_0")
      (fields
        (field (name "DIGIKEY_PART_NUMBER") "490-MA40H1S-RCT-ND")
        (field (name "MF") "Murata")
        (field (name "MOUSER_PART_NUMBER") "81-MA40H1S-R")
      )
      (libsource (lib "eagle-import") (part "MURATA_MA40H1S-RMURATA_MA40H1S-R_0_0"))
    )
    (comp (ref "U25")
      (value "MURATA_MA40H1S-RMURATA_MA40H1S-R_0_0")
      (footprint "eagle-import:MURATA_MA40H1S-R_0")
      (fields
        (field (name "DIGIKEY_PART_NUMBER") "490-MA40H1S-RCT-ND")
        (field (name "MF") "Murata")
        (field (name "MOUSER_PART_NUMBER") "81-MA40H1S-R")
      )
      (libsource (lib "eagle-import") (part "MURATA_MA40H1S-RMURATA_MA40H1S-R_0_0"))
    )
    (comp (ref "U26")
      (value "MURATA_MA40H1S-RMURATA_MA40H1S-R_0_0")
      (footprint "eagle-import:MURATA_MA40H1S-R_0")
      (fields
        (field (name "DIGIKEY_PART_NUMBER") "490-MA40H1S-RCT-ND")
        (field (name "MF") "Murata")
        (field (name "MOUSER_PART_NUMBER") "81-MA40H1S-R")
      )
      (libsource (lib "eagle-import") (part "MURATA_MA40H1S-RMURATA_MA40H1S-R_0_0"))
    )
    (comp (ref "U27")
      (value "MURATA_MA40H1S-RMURATA_MA40H1S-R_0_0")
      (footprint "eagle-import:MURATA_MA40H1S-R_0")
      (fields
        (field (name "DIGIKEY_PART_NUMBER") "490-MA40H1S-RCT-ND")
        (field (name "MF") "Murata")
        (field (name "MOUSER_PART_NUMBER") "81-MA40H1S-R")
      )
      (libsource (lib "eagle-import") (part "MURATA_MA40H1S-RMURATA_MA40H1S-R_0_0"))
    )
    (comp (ref "U28")
      (value "MURATA_MA40H1S-RMURATA_MA40H1S-R_0_0")
      (footprint "eagle-import:MURATA_MA40H1S-R_0")
      (fields
        (field (name "DIGIKEY_PART_NUMBER") "490-MA40H1S-RCT-ND")
        (field (name "MF") "Murata")
        (field (name "MOUSER_PART_NUMBER") "81-MA40H1S-R")
      )
      (libsource (lib "eagle-import") (part "MURATA_MA40H1S-RMURATA_MA40H1S-R_0_0"))
    )
    (comp (ref "U29")
      (value "MURATA_MA40H1S-RMURATA_MA40H1S-R_0_0")
      (footprint "eagle-import:MURATA_MA40H1S-R_0")
      (fields
        (field (name "DIGIKEY_PART_NUMBER") "490-MA40H1S-RCT-ND")
        (field (name "MF") "Murata")
        (field (name "MOUSER_PART_NUMBER") "81-MA40H1S-R")
      )
      (libsource (lib "eagle-import") (part "MURATA_MA40H1S-RMURATA_MA40H1S-R_0_0"))
    )
    (comp (ref "U30")
      (value "MURATA_MA40H1S-RMURATA_MA40H1S-R_0_0")
      (footprint "eagle-import:MURATA_MA40H1S-R_0")
      (fields
        (field (name "DIGIKEY_PART_NUMBER") "490-MA40H1S-RCT-ND")
        (field (name "MF") "Murata")
        (field (name "MOUSER_PART_NUMBER") "81-MA40H1S-R")
      )
      (libsource (lib "eagle-import") (part "MURATA_MA40H1S-RMURATA_MA40H1S-R_0_0"))
    )
    (comp (ref "U31")
      (value "MURATA_MA40H1S-RMURATA_MA40H1S-R_0_0")
      (footprint "eagle-import:MURATA_MA40H1S-R_0")
      (fields
        (field (name "DIGIKEY_PART_NUMBER") "490-MA40H1S-RCT-ND")
        (field (name "MF") "Murata")
        (field (name "MOUSER_PART_NUMBER") "81-MA40H1S-R")
      )
      (libsource (lib "eagle-import") (part "MURATA_MA40H1S-RMURATA_MA40H1S-R_0_0"))
    )
    (comp (ref "U32")
      (value "MURATA_MA40H1S-RMURATA_MA40H1S-R_0_0")
      (footprint "eagle-import:MURATA_MA40H1S-R_0")
      (fields
        (field (name "DIGIKEY_PART_NUMBER") "490-MA40H1S-RCT-ND")
        (field (name "MF") "Murata")
        (field (name "MOUSER_PART_NUMBER") "81-MA40H1S-R")
      )
      (libsource (lib "eagle-import") (part "MURATA_MA40H1S-RMURATA_MA40H1S-R_0_0"))
    )
    (comp (ref "U33")
      (value "MURATA_MA40H1S-RMURATA_MA40H1S-R_0_0")
      (footprint "eagle-import:MURATA_MA40H1S-R_0")
      (fields
        (field (name "DIGIKEY_PART_NUMBER") "490-MA40H1S-RCT-ND")
        (field (name "MF") "Murata")
        (field (name "MOUSER_PART_NUMBER") "81-MA40H1S-R")
      )
      (libsource (lib "eagle-import") (part "MURATA_MA40H1S-RMURATA_MA40H1S-R_0_0"))
    )
    (comp (ref "U34")
      (value "MURATA_MA40H1S-RMURATA_MA40H1S-R_0_0")
      (footprint "eagle-import:MURATA_MA40H1S-R_0")
      (fields
        (field (name "DIGIKEY_PART_NUMBER") "490-MA40H1S-RCT-ND")
        (field (name "MF") "Murata")
        (field (name "MOUSER_PART_NUMBER") "81-MA40H1S-R")
      )
      (libsource (lib "eagle-import") (part "MURATA_MA40H1S-RMURATA_MA40H1S-R_0_0"))
    )
    (comp (ref "U35")
      (value "MURATA_MA40H1S-RMURATA_MA40H1S-R_0_0")
      (footprint "eagle-import:MURATA_MA40H1S-R_0")
      (fields
        (field (name "DIGIKEY_PART_NUMBER") "490-MA40H1S-RCT-ND")
        (field (name "MF") "Murata")
        (field (name "MOUSER_PART_NUMBER") "81-MA40H1S-R")
      )
      (libsource (lib "eagle-import") (part "MURATA_MA40H1S-RMURATA_MA40H1S-R_0_0"))
    )
    (comp (ref "U36")
      (value "MURATA_MA40H1S-RMURATA_MA40H1S-R_0_0")
      (footprint "eagle-import:MURATA_MA40H1S-R_0")
      (fields
        (field (name "DIGIKEY_PART_NUMBER") "490-MA40H1S-RCT-ND")
        (field (name "MF") "Murata")
        (field (name "MOUSER_PART_NUMBER") "81-MA40H1S-R")
      )
      (libsource (lib "eagle-import") (part "MURATA_MA40H1S-RMURATA_MA40H1S-R_0_0"))
    )
    (comp (ref "U37")
      (value "MURATA_MA40H1S-RMURATA_MA40H1S-R_0_0")
      (footprint "eagle-import:MURATA_MA40H1S-R_0")
      (fields
        (field (name "DIGIKEY_PART_NUMBER") "490-MA40H1S-RCT-ND")
        (field (name "MF") "Murata")
        (field (name "MOUSER_PART_NUMBER") "81-MA40H1S-R")
      )
      (libsource (lib "eagle-import") (part "MURATA_MA40H1S-RMURATA_MA40H1S-R_0_0"))
    )
    (comp (ref "U38")
      (value "MURATA_MA40H1S-RMURATA_MA40H1S-R_0_0")
      (footprint "eagle-import:MURATA_MA40H1S-R_0")
      (fields
        (field (name "DIGIKEY_PART_NUMBER") "490-MA40H1S-RCT-ND")
        (field (name "MF") "Murata")
        (field (name "MOUSER_PART_NUMBER") "81-MA40H1S-R")
      )
      (libsource (lib "eagle-import") (part "MURATA_MA40H1S-RMURATA_MA40H1S-R_0_0"))
    )
    (comp (ref "U39")
      (value "MURATA_MA40H1S-RMURATA_MA40H1S-R_0_0")
      (footprint "eagle-import:MURATA_MA40H1S-R_0")
      (fields
        (field (name "DIGIKEY_PART_NUMBER") "490-MA40H1S-RCT-ND")
        (field (name "MF") "Murata")
        (field (name "MOUSER_PART_NUMBER") "81-MA40H1S-R")
      )
      (libsource (lib "eagle-import") (part "MURATA_MA40H1S-RMURATA_MA40H1S-R_0_0"))
    )
    (comp (ref "U40")
      (value "MURATA_MA40H1S-RMURATA_MA40H1S-R_0_0")
      (footprint "eagle-import:MURATA_MA40H1S-R_0")
      (fields
        (field (name "DIGIKEY_PART_NUMBER") "490-MA40H1S-RCT-ND")
        (field (name "MF") "Murata")
        (field (name "MOUSER_PART_NUMBER") "81-MA40H1S-R")
      )
      (libsource (lib "eagle-import") (part "MURATA_MA40H1S-RMURATA_MA40H1S-R_0_0"))
    )
    (comp (ref "U41")
      (value "MURATA_MA40H1S-RMURATA_MA40H1S-R_0_0")
      (footprint "eagle-import:MURATA_MA40H1S-R_0")
      (fields
        (field (name "DIGIKEY_PART_NUMBER") "490-MA40H1S-RCT-ND")
        (field (name "MF") "Murata")
        (field (name "MOUSER_PART_NUMBER") "81-MA40H1S-R")
      )
      (libsource (lib "eagle-import") (part "MURATA_MA40H1S-RMURATA_MA40H1S-R_0_0"))
    )
    (comp (ref "U42")
      (value "MURATA_MA40H1S-RMURATA_MA40H1S-R_0_0")
      (footprint "eagle-import:MURATA_MA40H1S-R_0")
      (fields
        (field (name "DIGIKEY_PART_NUMBER") "490-MA40H1S-RCT-ND")
        (field (name "MF") "Murata")
        (field (name "MOUSER_PART_NUMBER") "81-MA40H1S-R")
      )
      (libsource (lib "eagle-import") (part "MURATA_MA40H1S-RMURATA_MA40H1S-R_0_0"))
    )
    (comp (ref "U43")
      (value "MURATA_MA40H1S-RMURATA_MA40H1S-R_0_0")
      (footprint "eagle-import:MURATA_MA40H1S-R_0")
      (fields
        (field (name "DIGIKEY_PART_NUMBER") "490-MA40H1S-RCT-ND")
        (field (name "MF") "Murata")
        (field (name "MOUSER_PART_NUMBER") "81-MA40H1S-R")
      )
      (libsource (lib "eagle-import") (part "MURATA_MA40H1S-RMURATA_MA40H1S-R_0_0"))
    )
    (comp (ref "U44")
      (value "MURATA_MA40H1S-RMURATA_MA40H1S-R_0_0")
      (footprint "eagle-import:MURATA_MA40H1S-R_0")
      (fields
        (field (name "DIGIKEY_PART_NUMBER") "490-MA40H1S-RCT-ND")
        (field (name "MF") "Murata")
        (field (name "MOUSER_PART_NUMBER") "81-MA40H1S-R")
      )
      (libsource (lib "eagle-import") (part "MURATA_MA40H1S-RMURATA_MA40H1S-R_0_0"))
    )
    (comp (ref "U45")
      (value "MURATA_MA40H1S-RMURATA_MA40H1S-R_0_0")
      (footprint "eagle-import:MURATA_MA40H1S-R_0")
      (fields
        (field (name "DIGIKEY_PART_NUMBER") "490-MA40H1S-RCT-ND")
        (field (name "MF") "Murata")
        (field (name "MOUSER_PART_NUMBER") "81-MA40H1S-R")
      )
      (libsource (lib "eagle-import") (part "MURATA_MA40H1S-RMURATA_MA40H1S-R_0_0"))
    )
    (comp (ref "U46")
      (value "MURATA_MA40H1S-RMURATA_MA40H1S-R_0_0")
      (footprint "eagle-import:MURATA_MA40H1S-R_0")
      (fields
        (field (name "DIGIKEY_PART_NUMBER") "490-MA40H1S-RCT-ND")
        (field (name "MF") "Murata")
        (field (name "MOUSER_PART_NUMBER") "81-MA40H1S-R")
      )
      (libsource (lib "eagle-import") (part "MURATA_MA40H1S-RMURATA_MA40H1S-R_0_0"))
    )
    (comp (ref "U47")
      (value "MURATA_MA40H1S-RMURATA_MA40H1S-R_0_0")
      (footprint "eagle-import:MURATA_MA40H1S-R_0")
      (fields
        (field (name "DIGIKEY_PART_NUMBER") "490-MA40H1S-RCT-ND")
        (field (name "MF") "Murata")
        (field (name "MOUSER_PART_NUMBER") "81-MA40H1S-R")
      )
      (libsource (lib "eagle-import") (part "MURATA_MA40H1S-RMURATA_MA40H1S-R_0_0"))
    )
    (comp (ref "U48")
      (value "MURATA_MA40H1S-RMURATA_MA40H1S-R_0_0")
      (footprint "eagle-import:MURATA_MA40H1S-R_0")
      (fields
        (field (name "DIGIKEY_PART_NUMBER") "490-MA40H1S-RCT-ND")
        (field (name "MF") "Murata")
        (field (name "MOUSER_PART_NUMBER") "81-MA40H1S-R")
      )
      (libsource (lib "eagle-import") (part "MURATA_MA40H1S-RMURATA_MA40H1S-R_0_0"))
    )
    (comp (ref "U49")
      (value "MURATA_MA40H1S-RMURATA_MA40H1S-R_0_0")
      (footprint "eagle-import:MURATA_MA40H1S-R_0")
      (fields
        (field (name "DIGIKEY_PART_NUMBER") "490-MA40H1S-RCT-ND")
        (field (name "MF") "Murata")
        (field (name "MOUSER_PART_NUMBER") "81-MA40H1S-R")
      )
      (libsource (lib "eagle-import") (part "MURATA_MA40H1S-RMURATA_MA40H1S-R_0_0"))
    )
    (comp (ref "U50")
      (value "MURATA_MA40H1S-RMURATA_MA40H1S-R_0_0")
      (footprint "eagle-import:MURATA_MA40H1S-R_0")
      (fields
        (field (name "DIGIKEY_PART_NUMBER") "490-MA40H1S-RCT-ND")
        (field (name "MF") "Murata")
        (field (name "MOUSER_PART_NUMBER") "81-MA40H1S-R")
      )
      (libsource (lib "eagle-import") (part "MURATA_MA40H1S-RMURATA_MA40H1S-R_0_0"))
    )
    (comp (ref "U51")
      (value "MURATA_MA40H1S-RMURATA_MA40H1S-R_0_0")
      (footprint "eagle-import:MURATA_MA40H1S-R_0")
      (fields
        (field (name "DIGIKEY_PART_NUMBER") "490-MA40H1S-RCT-ND")
        (field (name "MF") "Murata")
        (field (name "MOUSER_PART_NUMBER") "81-MA40H1S-R")
      )
      (libsource (lib "eagle-import") (part "MURATA_MA40H1S-RMURATA_MA40H1S-R_0_0"))
    )
    (comp (ref "U52")
      (value "MURATA_MA40H1S-RMURATA_MA40H1S-R_0_0")
      (footprint "eagle-import:MURATA_MA40H1S-R_0")
      (fields
        (field (name "DIGIKEY_PART_NUMBER") "490-MA40H1S-RCT-ND")
        (field (name "MF") "Murata")
        (field (name "MOUSER_PART_NUMBER") "81-MA40H1S-R")
      )
      (libsource (lib "eagle-import") (part "MURATA_MA40H1S-RMURATA_MA40H1S-R_0_0"))
    )
    (comp (ref "U53")
      (value "MURATA_MA40H1S-RMURATA_MA40H1S-R_0_0")
      (footprint "eagle-import:MURATA_MA40H1S-R_0")
      (fields
        (field (name "DIGIKEY_PART_NUMBER") "490-MA40H1S-RCT-ND")
        (field (name "MF") "Murata")
        (field (name "MOUSER_PART_NUMBER") "81-MA40H1S-R")
      )
      (libsource (lib "eagle-import") (part "MURATA_MA40H1S-RMURATA_MA40H1S-R_0_0"))
    )
    (comp (ref "U54")
      (value "MURATA_MA40H1S-RMURATA_MA40H1S-R_0_0")
      (footprint "eagle-import:MURATA_MA40H1S-R_0")
      (fields
        (field (name "DIGIKEY_PART_NUMBER") "490-MA40H1S-RCT-ND")
        (field (name "MF") "Murata")
        (field (name "MOUSER_PART_NUMBER") "81-MA40H1S-R")
      )
      (libsource (lib "eagle-import") (part "MURATA_MA40H1S-RMURATA_MA40H1S-R_0_0"))
    )
    (comp (ref "U55")
      (value "MURATA_MA40H1S-RMURATA_MA40H1S-R_0_0")
      (footprint "eagle-import:MURATA_MA40H1S-R_0")
      (fields
        (field (name "DIGIKEY_PART_NUMBER") "490-MA40H1S-RCT-ND")
        (field (name "MF") "Murata")
        (field (name "MOUSER_PART_NUMBER") "81-MA40H1S-R")
      )
      (libsource (lib "eagle-import") (part "MURATA_MA40H1S-RMURATA_MA40H1S-R_0_0"))
    )
    (comp (ref "U56")
      (value "MURATA_MA40H1S-RMURATA_MA40H1S-R_0_0")
      (footprint "eagle-import:MURATA_MA40H1S-R_0")
      (fields
        (field (name "DIGIKEY_PART_NUMBER") "490-MA40H1S-RCT-ND")
        (field (name "MF") "Murata")
        (field (name "MOUSER_PART_NUMBER") "81-MA40H1S-R")
      )
      (libsource (lib "eagle-import") (part "MURATA_MA40H1S-RMURATA_MA40H1S-R_0_0"))
    )
    (comp (ref "U57")
      (value "MURATA_MA40H1S-RMURATA_MA40H1S-R_0_0")
      (footprint "eagle-import:MURATA_MA40H1S-R_0")
      (fields
        (field (name "DIGIKEY_PART_NUMBER") "490-MA40H1S-RCT-ND")
        (field (name "MF") "Murata")
        (field (name "MOUSER_PART_NUMBER") "81-MA40H1S-R")
      )
      (libsource (lib "eagle-import") (part "MURATA_MA40H1S-RMURATA_MA40H1S-R_0_0"))
    )
    (comp (ref "U58")
      (value "MURATA_MA40H1S-RMURATA_MA40H1S-R_0_0")
      (footprint "eagle-import:MURATA_MA40H1S-R_0")
      (fields
        (field (name "DIGIKEY_PART_NUMBER") "490-MA40H1S-RCT-ND")
        (field (name "MF") "Murata")
        (field (name "MOUSER_PART_NUMBER") "81-MA40H1S-R")
      )
      (libsource (lib "eagle-import") (part "MURATA_MA40H1S-RMURATA_MA40H1S-R_0_0"))
    )
    (comp (ref "U59")
      (value "MURATA_MA40H1S-RMURATA_MA40H1S-R_0_0")
      (footprint "eagle-import:MURATA_MA40H1S-R_0")
      (fields
        (field (name "DIGIKEY_PART_NUMBER") "490-MA40H1S-RCT-ND")
        (field (name "MF") "Murata")
        (field (name "MOUSER_PART_NUMBER") "81-MA40H1S-R")
      )
      (libsource (lib "eagle-import") (part "MURATA_MA40H1S-RMURATA_MA40H1S-R_0_0"))
    )
    (comp (ref "U60")
      (value "MURATA_MA40H1S-RMURATA_MA40H1S-R_0_0")
      (footprint "eagle-import:MURATA_MA40H1S-R_0")
      (fields
        (field (name "DIGIKEY_PART_NUMBER") "490-MA40H1S-RCT-ND")
        (field (name "MF") "Murata")
        (field (name "MOUSER_PART_NUMBER") "81-MA40H1S-R")
      )
      (libsource (lib "eagle-import") (part "MURATA_MA40H1S-RMURATA_MA40H1S-R_0_0"))
    )
    (comp (ref "U61")
      (value "MURATA_MA40H1S-RMURATA_MA40H1S-R_0_0")
      (footprint "eagle-import:MURATA_MA40H1S-R_0")
      (fields
        (field (name "DIGIKEY_PART_NUMBER") "490-MA40H1S-RCT-ND")
        (field (name "MF") "Murata")
        (field (name "MOUSER_PART_NUMBER") "81-MA40H1S-R")
      )
      (libsource (lib "eagle-import") (part "MURATA_MA40H1S-RMURATA_MA40H1S-R_0_0"))
    )
    (comp (ref "U62")
      (value "MURATA_MA40H1S-RMURATA_MA40H1S-R_0_0")
      (footprint "eagle-import:MURATA_MA40H1S-R_0")
      (fields
        (field (name "DIGIKEY_PART_NUMBER") "490-MA40H1S-RCT-ND")
        (field (name "MF") "Murata")
        (field (name "MOUSER_PART_NUMBER") "81-MA40H1S-R")
      )
      (libsource (lib "eagle-import") (part "MURATA_MA40H1S-RMURATA_MA40H1S-R_0_0"))
    )
    (comp (ref "U63")
      (value "MURATA_MA40H1S-RMURATA_MA40H1S-R_0_0")
      (footprint "eagle-import:MURATA_MA40H1S-R_0")
      (fields
        (field (name "DIGIKEY_PART_NUMBER") "490-MA40H1S-RCT-ND")
        (field (name "MF") "Murata")
        (field (name "MOUSER_PART_NUMBER") "81-MA40H1S-R")
      )
      (libsource (lib "eagle-import") (part "MURATA_MA40H1S-RMURATA_MA40H1S-R_0_0"))
    )
    (comp (ref "U64")
      (value "MURATA_MA40H1S-RMURATA_MA40H1S-R_0_0")
      (footprint "eagle-import:MURATA_MA40H1S-R_0")
      (fields
        (field (name "DIGIKEY_PART_NUMBER") "490-MA40H1S-RCT-ND")
        (field (name "MF") "Murata")
        (field (name "MOUSER_PART_NUMBER") "81-MA40H1S-R")
      )
      (libsource (lib "eagle-import") (part "MURATA_MA40H1S-RMURATA_MA40H1S-R_0_0"))
    )
    (comp (ref "U65")
      (value "MURATA_MA40H1S-RMURATA_MA40H1S-R_0_0")
      (footprint "eagle-import:MURATA_MA40H1S-R_0")
      (fields
        (field (name "DIGIKEY_PART_NUMBER") "490-MA40H1S-RCT-ND")
        (field (name "MF") "Murata")
        (field (name "MOUSER_PART_NUMBER") "81-MA40H1S-R")
      )
      (libsource (lib "eagle-import") (part "MURATA_MA40H1S-RMURATA_MA40H1S-R_0_0"))
    )
    (comp (ref "U66")
      (value "MURATA_MA40H1S-RMURATA_MA40H1S-R_0_0")
      (footprint "eagle-import:MURATA_MA40H1S-R_0")
      (fields
        (field (name "DIGIKEY_PART_NUMBER") "490-MA40H1S-RCT-ND")
        (field (name "MF") "Murata")
        (field (name "MOUSER_PART_NUMBER") "81-MA40H1S-R")
      )
      (libsource (lib "eagle-import") (part "MURATA_MA40H1S-RMURATA_MA40H1S-R_0_0"))
    )
    (comp (ref "U67")
      (value "MURATA_MA40H1S-RMURATA_MA40H1S-R_0_0")
      (footprint "eagle-import:MURATA_MA40H1S-R_0")
      (fields
        (field (name "DIGIKEY_PART_NUMBER") "490-MA40H1S-RCT-ND")
        (field (name "MF") "Murata")
        (field (name "MOUSER_PART_NUMBER") "81-MA40H1S-R")
      )
      (libsource (lib "eagle-import") (part "MURATA_MA40H1S-RMURATA_MA40H1S-R_0_0"))
    )
    (comp (ref "U68")
      (value "MURATA_MA40H1S-RMURATA_MA40H1S-R_0_0")
      (footprint "eagle-import:MURATA_MA40H1S-R_0")
      (fields
        (field (name "DIGIKEY_PART_NUMBER") "490-MA40H1S-RCT-ND")
        (field (name "MF") "Murata")
        (field (name "MOUSER_PART_NUMBER") "81-MA40H1S-R")
      )
      (libsource (lib "eagle-import") (part "MURATA_MA40H1S-RMURATA_MA40H1S-R_0_0"))
    )
    (comp (ref "U69")
      (value "MURATA_MA40H1S-RMURATA_MA40H1S-R_0_0")
      (footprint "eagle-import:MURATA_MA40H1S-R_0")
      (fields
        (field (name "DIGIKEY_PART_NUMBER") "490-MA40H1S-RCT-ND")
        (field (name "MF") "Murata")
        (field (name "MOUSER_PART_NUMBER") "81-MA40H1S-R")
      )
      (libsource (lib "eagle-import") (part "MURATA_MA40H1S-RMURATA_MA40H1S-R_0_0"))
    )
    (comp (ref "U70")
      (value "MURATA_MA40H1S-RMURATA_MA40H1S-R_0_0")
      (footprint "eagle-import:MURATA_MA40H1S-R_0")
      (fields
        (field (name "DIGIKEY_PART_NUMBER") "490-MA40H1S-RCT-ND")
        (field (name "MF") "Murata")
        (field (name "MOUSER_PART_NUMBER") "81-MA40H1S-R")
      )
      (libsource (lib "eagle-import") (part "MURATA_MA40H1S-RMURATA_MA40H1S-R_0_0"))
    )
    (comp (ref "U71")
      (value "MURATA_MA40H1S-RMURATA_MA40H1S-R_0_0")
      (footprint "eagle-import:MURATA_MA40H1S-R_0")
      (fields
        (field (name "DIGIKEY_PART_NUMBER") "490-MA40H1S-RCT-ND")
        (field (name "MF") "Murata")
        (field (name "MOUSER_PART_NUMBER") "81-MA40H1S-R")
      )
      (libsource (lib "eagle-import") (part "MURATA_MA40H1S-RMURATA_MA40H1S-R_0_0"))
    )
    (comp (ref "U72")
      (value "MURATA_MA40H1S-RMURATA_MA40H1S-R_0_0")
      (footprint "eagle-import:MURATA_MA40H1S-R_0")
      (fields
        (field (name "DIGIKEY_PART_NUMBER") "490-MA40H1S-RCT-ND")
        (field (name "MF") "Murata")
        (field (name "MOUSER_PART_NUMBER") "81-MA40H1S-R")
      )
      (libsource (lib "eagle-import") (part "MURATA_MA40H1S-RMURATA_MA40H1S-R_0_0"))
    )
    (comp (ref "U73")
      (value "MURATA_MA40H1S-RMURATA_MA40H1S-R_0_0")
      (footprint "eagle-import:MURATA_MA40H1S-R_0")
      (fields
        (field (name "DIGIKEY_PART_NUMBER") "490-MA40H1S-RCT-ND")
        (field (name "MF") "Murata")
        (field (name "MOUSER_PART_NUMBER") "81-MA40H1S-R")
      )
      (libsource (lib "eagle-import") (part "MURATA_MA40H1S-RMURATA_MA40H1S-R_0_0"))
    )
    (comp (ref "U74")
      (value "MURATA_MA40H1S-RMURATA_MA40H1S-R_0_0")
      (footprint "eagle-import:MURATA_MA40H1S-R_0")
      (fields
        (field (name "DIGIKEY_PART_NUMBER") "490-MA40H1S-RCT-ND")
        (field (name "MF") "Murata")
        (field (name "MOUSER_PART_NUMBER") "81-MA40H1S-R")
      )
      (libsource (lib "eagle-import") (part "MURATA_MA40H1S-RMURATA_MA40H1S-R_0_0"))
    )
    (comp (ref "U75")
      (value "MURATA_MA40H1S-RMURATA_MA40H1S-R_0_0")
      (footprint "eagle-import:MURATA_MA40H1S-R_0")
      (fields
        (field (name "DIGIKEY_PART_NUMBER") "490-MA40H1S-RCT-ND")
        (field (name "MF") "Murata")
        (field (name "MOUSER_PART_NUMBER") "81-MA40H1S-R")
      )
      (libsource (lib "eagle-import") (part "MURATA_MA40H1S-RMURATA_MA40H1S-R_0_0"))
    )
    (comp (ref "U76")
      (value "MURATA_MA40H1S-RMURATA_MA40H1S-R_0_0")
      (footprint "eagle-import:MURATA_MA40H1S-R_0")
      (fields
        (field (name "DIGIKEY_PART_NUMBER") "490-MA40H1S-RCT-ND")
        (field (name "MF") "Murata")
        (field (name "MOUSER_PART_NUMBER") "81-MA40H1S-R")
      )
      (libsource (lib "eagle-import") (part "MURATA_MA40H1S-RMURATA_MA40H1S-R_0_0"))
    )
    (comp (ref "U77")
      (value "MURATA_MA40H1S-RMURATA_MA40H1S-R_0_0")
      (footprint "eagle-import:MURATA_MA40H1S-R_0")
      (fields
        (field (name "DIGIKEY_PART_NUMBER") "490-MA40H1S-RCT-ND")
        (field (name "MF") "Murata")
        (field (name "MOUSER_PART_NUMBER") "81-MA40H1S-R")
      )
      (libsource (lib "eagle-import") (part "MURATA_MA40H1S-RMURATA_MA40H1S-R_0_0"))
    )
    (comp (ref "U78")
      (value "MURATA_MA40H1S-RMURATA_MA40H1S-R_0_0")
      (footprint "eagle-import:MURATA_MA40H1S-R_0")
      (fields
        (field (name "DIGIKEY_PART_NUMBER") "490-MA40H1S-RCT-ND")
        (field (name "MF") "Murata")
        (field (name "MOUSER_PART_NUMBER") "81-MA40H1S-R")
      )
      (libsource (lib "eagle-import") (part "MURATA_MA40H1S-RMURATA_MA40H1S-R_0_0"))
    )
    (comp (ref "U79")
      (value "MURATA_MA40H1S-RMURATA_MA40H1S-R_0_0")
      (footprint "eagle-import:MURATA_MA40H1S-R_0")
      (fields
        (field (name "DIGIKEY_PART_NUMBER") "490-MA40H1S-RCT-ND")
        (field (name "MF") "Murata")
        (field (name "MOUSER_PART_NUMBER") "81-MA40H1S-R")
      )
      (libsource (lib "eagle-import") (part "MURATA_MA40H1S-RMURATA_MA40H1S-R_0_0"))
    )
    (comp (ref "U80")
      (value "MURATA_MA40H1S-RMURATA_MA40H1S-R_0_0")
      (footprint "eagle-import:MURATA_MA40H1S-R_0")
      (fields
        (field (name "DIGIKEY_PART_NUMBER") "490-MA40H1S-RCT-ND")
        (field (name "MF") "Murata")
        (field (name "MOUSER_PART_NUMBER") "81-MA40H1S-R")
      )
      (libsource (lib "eagle-import") (part "MURATA_MA40H1S-RMURATA_MA40H1S-R_0_0"))
    )
    (comp (ref "U90")
      (value "MURATA_MA40H1S-RMURATA_MA40H1S-R_0_0")
      (footprint "eagle-import:MURATA_MA40H1S-R_0")
      (fields
        (field (name "DIGIKEY_PART_NUMBER") "490-MA40H1S-RCT-ND")
        (field (name "MF") "Murata")
        (field (name "MOUSER_PART_NUMBER") "81-MA40H1S-R")
      )
      (libsource (lib "eagle-import") (part "MURATA_MA40H1S-RMURATA_MA40H1S-R_0_0"))
    )
    (comp (ref "U91")
      (value "MURATA_MA40H1S-RMURATA_MA40H1S-R_0_0")
      (footprint "eagle-import:MURATA_MA40H1S-R_0")
      (fields
        (field (name "DIGIKEY_PART_NUMBER") "490-MA40H1S-RCT-ND")
        (field (name "MF") "Murata")
        (field (name "MOUSER_PART_NUMBER") "81-MA40H1S-R")
      )
      (libsource (lib "eagle-import") (part "MURATA_MA40H1S-RMURATA_MA40H1S-R_0_0"))
    )
    (comp (ref "U92")
      (value "MURATA_MA40H1S-RMURATA_MA40H1S-R_0_0")
      (footprint "eagle-import:MURATA_MA40H1S-R_0")
      (fields
        (field (name "DIGIKEY_PART_NUMBER") "490-MA40H1S-RCT-ND")
        (field (name "MF") "Murata")
        (field (name "MOUSER_PART_NUMBER") "81-MA40H1S-R")
      )
      (libsource (lib "eagle-import") (part "MURATA_MA40H1S-RMURATA_MA40H1S-R_0_0"))
    )
    (comp (ref "U93")
      (value "MURATA_MA40H1S-RMURATA_MA40H1S-R_0_0")
      (footprint "eagle-import:MURATA_MA40H1S-R_0")
      (fields
        (field (name "DIGIKEY_PART_NUMBER") "490-MA40H1S-RCT-ND")
        (field (name "MF") "Murata")
        (field (name "MOUSER_PART_NUMBER") "81-MA40H1S-R")
      )
      (libsource (lib "eagle-import") (part "MURATA_MA40H1S-RMURATA_MA40H1S-R_0_0"))
    )
    (comp (ref "U94")
      (value "MURATA_MA40H1S-RMURATA_MA40H1S-R_0_0")
      (footprint "eagle-import:MURATA_MA40H1S-R_0")
      (fields
        (field (name "DIGIKEY_PART_NUMBER") "490-MA40H1S-RCT-ND")
        (field (name "MF") "Murata")
        (field (name "MOUSER_PART_NUMBER") "81-MA40H1S-R")
      )
      (libsource (lib "eagle-import") (part "MURATA_MA40H1S-RMURATA_MA40H1S-R_0_0"))
    )
    (comp (ref "U95")
      (value "MURATA_MA40H1S-RMURATA_MA40H1S-R_0_0")
      (footprint "eagle-import:MURATA_MA40H1S-R_0")
      (fields
        (field (name "DIGIKEY_PART_NUMBER") "490-MA40H1S-RCT-ND")
        (field (name "MF") "Murata")
        (field (name "MOUSER_PART_NUMBER") "81-MA40H1S-R")
      )
      (libsource (lib "eagle-import") (part "MURATA_MA40H1S-RMURATA_MA40H1S-R_0_0"))
    )
    (comp (ref "U96")
      (value "MURATA_MA40H1S-RMURATA_MA40H1S-R_0_0")
      (footprint "eagle-import:MURATA_MA40H1S-R_0")
      (fields
        (field (name "DIGIKEY_PART_NUMBER") "490-MA40H1S-RCT-ND")
        (field (name "MF") "Murata")
        (field (name "MOUSER_PART_NUMBER") "81-MA40H1S-R")
      )
      (libsource (lib "eagle-import") (part "MURATA_MA40H1S-RMURATA_MA40H1S-R_0_0"))
    )
    (comp (ref "U97")
      (value "MURATA_MA40H1S-RMURATA_MA40H1S-R_0_0")
      (footprint "eagle-import:MURATA_MA40H1S-R_0")
      (fields
        (field (name "DIGIKEY_PART_NUMBER") "490-MA40H1S-RCT-ND")
        (field (name "MF") "Murata")
        (field (name "MOUSER_PART_NUMBER") "81-MA40H1S-R")
      )
      (libsource (lib "eagle-import") (part "MURATA_MA40H1S-RMURATA_MA40H1S-R_0_0"))
    )
    (comp (ref "U98")
      (value "MURATA_MA40H1S-RMURATA_MA40H1S-R_0_0")
      (footprint "eagle-import:MURATA_MA40H1S-R_0")
      (fields
        (field (name "DIGIKEY_PART_NUMBER") "490-MA40H1S-RCT-ND")
        (field (name "MF") "Murata")
        (field (name "MOUSER_PART_NUMBER") "81-MA40H1S-R")
      )
      (libsource (lib "eagle-import") (part "MURATA_MA40H1S-RMURATA_MA40H1S-R_0_0"))
    )
    (comp (ref "U99")
      (value "MURATA_MA40H1S-RMURATA_MA40H1S-R_0_0")
      (footprint "eagle-import:MURATA_MA40H1S-R_0")
      (fields
        (field (name "DIGIKEY_PART_NUMBER") "490-MA40H1S-RCT-ND")
        (field (name "MF") "Murata")
        (field (name "MOUSER_PART_NUMBER") "81-MA40H1S-R")
      )
      (libsource (lib "eagle-import") (part "MURATA_MA40H1S-RMURATA_MA40H1S-R_0_0"))
    )
    (comp (ref "U100")
      (value "MURATA_MA40H1S-RMURATA_MA40H1S-R_0_0")
      (footprint "eagle-import:MURATA_MA40H1S-R_0")
      (fields
        (field (name "DIGIKEY_PART_NUMBER") "490-MA40H1S-RCT-ND")
        (field (name "MF") "Murata")
        (field (name "MOUSER_PART_NUMBER") "81-MA40H1S-R")
      )
      (libsource (lib "eagle-import") (part "MURATA_MA40H1S-RMURATA_MA40H1S-R_0_0"))
    )
    (comp (ref "U101")
      (value "MURATA_MA40H1S-RMURATA_MA40H1S-R_0_0")
      (footprint "eagle-import:MURATA_MA40H1S-R_0")
      (fields
        (field (name "DIGIKEY_PART_NUMBER") "490-MA40H1S-RCT-ND")
        (field (name "MF") "Murata")
        (field (name "MOUSER_PART_NUMBER") "81-MA40H1S-R")
      )
      (libsource (lib "eagle-import") (part "MURATA_MA40H1S-RMURATA_MA40H1S-R_0_0"))
    )
    (comp (ref "U102")
      (value "MURATA_MA40H1S-RMURATA_MA40H1S-R_0_0")
      (footprint "eagle-import:MURATA_MA40H1S-R_0")
      (fields
        (field (name "DIGIKEY_PART_NUMBER") "490-MA40H1S-RCT-ND")
        (field (name "MF") "Murata")
        (field (name "MOUSER_PART_NUMBER") "81-MA40H1S-R")
      )
      (libsource (lib "eagle-import") (part "MURATA_MA40H1S-RMURATA_MA40H1S-R_0_0"))
    )
    (comp (ref "U103")
      (value "MURATA_MA40H1S-RMURATA_MA40H1S-R_0_0")
      (footprint "eagle-import:MURATA_MA40H1S-R_0")
      (fields
        (field (name "DIGIKEY_PART_NUMBER") "490-MA40H1S-RCT-ND")
        (field (name "MF") "Murata")
        (field (name "MOUSER_PART_NUMBER") "81-MA40H1S-R")
      )
      (libsource (lib "eagle-import") (part "MURATA_MA40H1S-RMURATA_MA40H1S-R_0_0"))
    )
    (comp (ref "U104")
      (value "MURATA_MA40H1S-RMURATA_MA40H1S-R_0_0")
      (footprint "eagle-import:MURATA_MA40H1S-R_0")
      (fields
        (field (name "DIGIKEY_PART_NUMBER") "490-MA40H1S-RCT-ND")
        (field (name "MF") "Murata")
        (field (name "MOUSER_PART_NUMBER") "81-MA40H1S-R")
      )
      (libsource (lib "eagle-import") (part "MURATA_MA40H1S-RMURATA_MA40H1S-R_0_0"))
    )
    (comp (ref "U105")
      (value "MURATA_MA40H1S-RMURATA_MA40H1S-R_0_0")
      (footprint "eagle-import:MURATA_MA40H1S-R_0")
      (fields
        (field (name "DIGIKEY_PART_NUMBER") "490-MA40H1S-RCT-ND")
        (field (name "MF") "Murata")
        (field (name "MOUSER_PART_NUMBER") "81-MA40H1S-R")
      )
      (libsource (lib "eagle-import") (part "MURATA_MA40H1S-RMURATA_MA40H1S-R_0_0"))
    )
    (comp (ref "U106")
      (value "MURATA_MA40H1S-RMURATA_MA40H1S-R_0_0")
      (footprint "eagle-import:MURATA_MA40H1S-R_0")
      (fields
        (field (name "DIGIKEY_PART_NUMBER") "490-MA40H1S-RCT-ND")
        (field (name "MF") "Murata")
        (field (name "MOUSER_PART_NUMBER") "81-MA40H1S-R")
      )
      (libsource (lib "eagle-import") (part "MURATA_MA40H1S-RMURATA_MA40H1S-R_0_0"))
    )
    (comp (ref "U107")
      (value "MURATA_MA40H1S-RMURATA_MA40H1S-R_0_0")
      (footprint "eagle-import:MURATA_MA40H1S-R_0")
      (fields
        (field (name "DIGIKEY_PART_NUMBER") "490-MA40H1S-RCT-ND")
        (field (name "MF") "Murata")
        (field (name "MOUSER_PART_NUMBER") "81-MA40H1S-R")
      )
      (libsource (lib "eagle-import") (part "MURATA_MA40H1S-RMURATA_MA40H1S-R_0_0"))
    )
    (comp (ref "U108")
      (value "MURATA_MA40H1S-RMURATA_MA40H1S-R_0_0")
      (footprint "eagle-import:MURATA_MA40H1S-R_0")
      (fields
        (field (name "DIGIKEY_PART_NUMBER") "490-MA40H1S-RCT-ND")
        (field (name "MF") "Murata")
        (field (name "MOUSER_PART_NUMBER") "81-MA40H1S-R")
      )
      (libsource (lib "eagle-import") (part "MURATA_MA40H1S-RMURATA_MA40H1S-R_0_0"))
    )
    (comp (ref "U109")
      (value "MURATA_MA40H1S-RMURATA_MA40H1S-R_0_0")
      (footprint "eagle-import:MURATA_MA40H1S-R_0")
      (fields
        (field (name "DIGIKEY_PART_NUMBER") "490-MA40H1S-RCT-ND")
        (field (name "MF") "Murata")
        (field (name "MOUSER_PART_NUMBER") "81-MA40H1S-R")
      )
      (libsource (lib "eagle-import") (part "MURATA_MA40H1S-RMURATA_MA40H1S-R_0_0"))
    )
    (comp (ref "U110")
      (value "MURATA_MA40H1S-RMURATA_MA40H1S-R_0_0")
      (footprint "eagle-import:MURATA_MA40H1S-R_0")
      (fields
        (field (name "DIGIKEY_PART_NUMBER") "490-MA40H1S-RCT-ND")
        (field (name "MF") "Murata")
        (field (name "MOUSER_PART_NUMBER") "81-MA40H1S-R")
      )
      (libsource (lib "eagle-import") (part "MURATA_MA40H1S-RMURATA_MA40H1S-R_0_0"))
    )
    (comp (ref "U111")
      (value "MURATA_MA40H1S-RMURATA_MA40H1S-R_0_0")
      (footprint "eagle-import:MURATA_MA40H1S-R_0")
      (fields
        (field (name "DIGIKEY_PART_NUMBER") "490-MA40H1S-RCT-ND")
        (field (name "MF") "Murata")
        (field (name "MOUSER_PART_NUMBER") "81-MA40H1S-R")
      )
      (libsource (lib "eagle-import") (part "MURATA_MA40H1S-RMURATA_MA40H1S-R_0_0"))
    )
    (comp (ref "U112")
      (value "MURATA_MA40H1S-RMURATA_MA40H1S-R_0_0")
      (footprint "eagle-import:MURATA_MA40H1S-R_0")
      (fields
        (field (name "DIGIKEY_PART_NUMBER") "490-MA40H1S-RCT-ND")
        (field (name "MF") "Murata")
        (field (name "MOUSER_PART_NUMBER") "81-MA40H1S-R")
      )
      (libsource (lib "eagle-import") (part "MURATA_MA40H1S-RMURATA_MA40H1S-R_0_0"))
    )
    (comp (ref "U113")
      (value "MURATA_MA40H1S-RMURATA_MA40H1S-R_0_0")
      (footprint "eagle-import:MURATA_MA40H1S-R_0")
      (fields
        (field (name "DIGIKEY_PART_NUMBER") "490-MA40H1S-RCT-ND")
        (field (name "MF") "Murata")
        (field (name "MOUSER_PART_NUMBER") "81-MA40H1S-R")
      )
      (libsource (lib "eagle-import") (part "MURATA_MA40H1S-RMURATA_MA40H1S-R_0_0"))
    )
    (comp (ref "U114")
      (value "MURATA_MA40H1S-RMURATA_MA40H1S-R_0_0")
      (footprint "eagle-import:MURATA_MA40H1S-R_0")
      (fields
        (field (name "DIGIKEY_PART_NUMBER") "490-MA40H1S-RCT-ND")
        (field (name "MF") "Murata")
        (field (name "MOUSER_PART_NUMBER") "81-MA40H1S-R")
      )
      (libsource (lib "eagle-import") (part "MURATA_MA40H1S-RMURATA_MA40H1S-R_0_0"))
    )
    (comp (ref "U115")
      (value "MURATA_MA40H1S-RMURATA_MA40H1S-R_0_0")
      (footprint "eagle-import:MURATA_MA40H1S-R_0")
      (fields
        (field (name "DIGIKEY_PART_NUMBER") "490-MA40H1S-RCT-ND")
        (field (name "MF") "Murata")
        (field (name "MOUSER_PART_NUMBER") "81-MA40H1S-R")
      )
      (libsource (lib "eagle-import") (part "MURATA_MA40H1S-RMURATA_MA40H1S-R_0_0"))
    )
    (comp (ref "U116")
      (value "MURATA_MA40H1S-RMURATA_MA40H1S-R_0_0")
      (footprint "eagle-import:MURATA_MA40H1S-R_0")
      (fields
        (field (name "DIGIKEY_PART_NUMBER") "490-MA40H1S-RCT-ND")
        (field (name "MF") "Murata")
        (field (name "MOUSER_PART_NUMBER") "81-MA40H1S-R")
      )
      (libsource (lib "eagle-import") (part "MURATA_MA40H1S-RMURATA_MA40H1S-R_0_0"))
    )
    (comp (ref "U117")
      (value "MURATA_MA40H1S-RMURATA_MA40H1S-R_0_0")
      (footprint "eagle-import:MURATA_MA40H1S-R_0")
      (fields
        (field (name "DIGIKEY_PART_NUMBER") "490-MA40H1S-RCT-ND")
        (field (name "MF") "Murata")
        (field (name "MOUSER_PART_NUMBER") "81-MA40H1S-R")
      )
      (libsource (lib "eagle-import") (part "MURATA_MA40H1S-RMURATA_MA40H1S-R_0_0"))
    )
    (comp (ref "U118")
      (value "MURATA_MA40H1S-RMURATA_MA40H1S-R_0_0")
      (footprint "eagle-import:MURATA_MA40H1S-R_0")
      (fields
        (field (name "DIGIKEY_PART_NUMBER") "490-MA40H1S-RCT-ND")
        (field (name "MF") "Murata")
        (field (name "MOUSER_PART_NUMBER") "81-MA40H1S-R")
      )
      (libsource (lib "eagle-import") (part "MURATA_MA40H1S-RMURATA_MA40H1S-R_0_0"))
    )
    (comp (ref "U119")
      (value "MURATA_MA40H1S-RMURATA_MA40H1S-R_0_0")
      (footprint "eagle-import:MURATA_MA40H1S-R_0")
      (fields
        (field (name "DIGIKEY_PART_NUMBER") "490-MA40H1S-RCT-ND")
        (field (name "MF") "Murata")
        (field (name "MOUSER_PART_NUMBER") "81-MA40H1S-R")
      )
      (libsource (lib "eagle-import") (part "MURATA_MA40H1S-RMURATA_MA40H1S-R_0_0"))
    )
    (comp (ref "U120")
      (value "MURATA_MA40H1S-RMURATA_MA40H1S-R_0_0")
      (footprint "eagle-import:MURATA_MA40H1S-R_0")
      (fields
        (field (name "DIGIKEY_PART_NUMBER") "490-MA40H1S-RCT-ND")
        (field (name "MF") "Murata")
        (field (name "MOUSER_PART_NUMBER") "81-MA40H1S-R")
      )
      (libsource (lib "eagle-import") (part "MURATA_MA40H1S-RMURATA_MA40H1S-R_0_0"))
    )
    (comp (ref "U121")
      (value "MURATA_MA40H1S-RMURATA_MA40H1S-R_0_0")
      (footprint "eagle-import:MURATA_MA40H1S-R_0")
      (fields
        (field (name "DIGIKEY_PART_NUMBER") "490-MA40H1S-RCT-ND")
        (field (name "MF") "Murata")
        (field (name "MOUSER_PART_NUMBER") "81-MA40H1S-R")
      )
      (libsource (lib "eagle-import") (part "MURATA_MA40H1S-RMURATA_MA40H1S-R_0_0"))
    )
    (comp (ref "U122")
      (value "MURATA_MA40H1S-RMURATA_MA40H1S-R_0_0")
      (footprint "eagle-import:MURATA_MA40H1S-R_0")
      (fields
        (field (name "DIGIKEY_PART_NUMBER") "490-MA40H1S-RCT-ND")
        (field (name "MF") "Murata")
        (field (name "MOUSER_PART_NUMBER") "81-MA40H1S-R")
      )
      (libsource (lib "eagle-import") (part "MURATA_MA40H1S-RMURATA_MA40H1S-R_0_0"))
    )
    (comp (ref "U123")
      (value "MURATA_MA40H1S-RMURATA_MA40H1S-R_0_0")
      (footprint "eagle-import:MURATA_MA40H1S-R_0")
      (fields
        (field (name "DIGIKEY_PART_NUMBER") "490-MA40H1S-RCT-ND")
        (field (name "MF") "Murata")
        (field (name "MOUSER_PART_NUMBER") "81-MA40H1S-R")
      )
      (libsource (lib "eagle-import") (part "MURATA_MA40H1S-RMURATA_MA40H1S-R_0_0"))
    )
    (comp (ref "U124")
      (value "MURATA_MA40H1S-RMURATA_MA40H1S-R_0_0")
      (footprint "eagle-import:MURATA_MA40H1S-R_0")
      (fields
        (field (name "DIGIKEY_PART_NUMBER") "490-MA40H1S-RCT-ND")
        (field (name "MF") "Murata")
        (field (name "MOUSER_PART_NUMBER") "81-MA40H1S-R")
      )
      (libsource (lib "eagle-import") (part "MURATA_MA40H1S-RMURATA_MA40H1S-R_0_0"))
    )
    (comp (ref "U125")
      (value "MURATA_MA40H1S-RMURATA_MA40H1S-R_0_0")
      (footprint "eagle-import:MURATA_MA40H1S-R_0")
      (fields
        (field (name "DIGIKEY_PART_NUMBER") "490-MA40H1S-RCT-ND")
        (field (name "MF") "Murata")
        (field (name "MOUSER_PART_NUMBER") "81-MA40H1S-R")
      )
      (libsource (lib "eagle-import") (part "MURATA_MA40H1S-RMURATA_MA40H1S-R_0_0"))
    )
    (comp (ref "U126")
      (value "MURATA_MA40H1S-RMURATA_MA40H1S-R_0_0")
      (footprint "eagle-import:MURATA_MA40H1S-R_0")
      (fields
        (field (name "DIGIKEY_PART_NUMBER") "490-MA40H1S-RCT-ND")
        (field (name "MF") "Murata")
        (field (name "MOUSER_PART_NUMBER") "81-MA40H1S-R")
      )
      (libsource (lib "eagle-import") (part "MURATA_MA40H1S-RMURATA_MA40H1S-R_0_0"))
    )
    (comp (ref "U127")
      (value "MURATA_MA40H1S-RMURATA_MA40H1S-R_0_0")
      (footprint "eagle-import:MURATA_MA40H1S-R_0")
      (fields
        (field (name "DIGIKEY_PART_NUMBER") "490-MA40H1S-RCT-ND")
        (field (name "MF") "Murata")
        (field (name "MOUSER_PART_NUMBER") "81-MA40H1S-R")
      )
      (libsource (lib "eagle-import") (part "MURATA_MA40H1S-RMURATA_MA40H1S-R_0_0"))
    )
    (comp (ref "U128")
      (value "MURATA_MA40H1S-RMURATA_MA40H1S-R_0_0")
      (footprint "eagle-import:MURATA_MA40H1S-R_0")
      (fields
        (field (name "DIGIKEY_PART_NUMBER") "490-MA40H1S-RCT-ND")
        (field (name "MF") "Murata")
        (field (name "MOUSER_PART_NUMBER") "81-MA40H1S-R")
      )
      (libsource (lib "eagle-import") (part "MURATA_MA40H1S-RMURATA_MA40H1S-R_0_0"))
    )
    (comp (ref "U129")
      (value "MURATA_MA40H1S-RMURATA_MA40H1S-R_0_0")
      (footprint "eagle-import:MURATA_MA40H1S-R_0")
      (fields
        (field (name "DIGIKEY_PART_NUMBER") "490-MA40H1S-RCT-ND")
        (field (name "MF") "Murata")
        (field (name "MOUSER_PART_NUMBER") "81-MA40H1S-R")
      )
      (libsource (lib "eagle-import") (part "MURATA_MA40H1S-RMURATA_MA40H1S-R_0_0"))
    )
    (comp (ref "U130")
      (value "MURATA_MA40H1S-RMURATA_MA40H1S-R_0_0")
      (footprint "eagle-import:MURATA_MA40H1S-R_0")
      (fields
        (field (name "DIGIKEY_PART_NUMBER") "490-MA40H1S-RCT-ND")
        (field (name "MF") "Murata")
        (field (name "MOUSER_PART_NUMBER") "81-MA40H1S-R")
      )
      (libsource (lib "eagle-import") (part "MURATA_MA40H1S-RMURATA_MA40H1S-R_0_0"))
    )
    (comp (ref "U131")
      (value "MURATA_MA40H1S-RMURATA_MA40H1S-R_0_0")
      (footprint "eagle-import:MURATA_MA40H1S-R_0")
      (fields
        (field (name "DIGIKEY_PART_NUMBER") "490-MA40H1S-RCT-ND")
        (field (name "MF") "Murata")
        (field (name "MOUSER_PART_NUMBER") "81-MA40H1S-R")
      )
      (libsource (lib "eagle-import") (part "MURATA_MA40H1S-RMURATA_MA40H1S-R_0_0"))
    )
    (comp (ref "U132")
      (value "MURATA_MA40H1S-RMURATA_MA40H1S-R_0_0")
      (footprint "eagle-import:MURATA_MA40H1S-R_0")
      (fields
        (field (name "DIGIKEY_PART_NUMBER") "490-MA40H1S-RCT-ND")
        (field (name "MF") "Murata")
        (field (name "MOUSER_PART_NUMBER") "81-MA40H1S-R")
      )
      (libsource (lib "eagle-import") (part "MURATA_MA40H1S-RMURATA_MA40H1S-R_0_0"))
    )
    (comp (ref "U133")
      (value "MURATA_MA40H1S-RMURATA_MA40H1S-R_0_0")
      (footprint "eagle-import:MURATA_MA40H1S-R_0")
      (fields
        (field (name "DIGIKEY_PART_NUMBER") "490-MA40H1S-RCT-ND")
        (field (name "MF") "Murata")
        (field (name "MOUSER_PART_NUMBER") "81-MA40H1S-R")
      )
      (libsource (lib "eagle-import") (part "MURATA_MA40H1S-RMURATA_MA40H1S-R_0_0"))
    )
    (comp (ref "U134")
      (value "MURATA_MA40H1S-RMURATA_MA40H1S-R_0_0")
      (footprint "eagle-import:MURATA_MA40H1S-R_0")
      (fields
        (field (name "DIGIKEY_PART_NUMBER") "490-MA40H1S-RCT-ND")
        (field (name "MF") "Murata")
        (field (name "MOUSER_PART_NUMBER") "81-MA40H1S-R")
      )
      (libsource (lib "eagle-import") (part "MURATA_MA40H1S-RMURATA_MA40H1S-R_0_0"))
    )
    (comp (ref "U135")
      (value "MURATA_MA40H1S-RMURATA_MA40H1S-R_0_0")
      (footprint "eagle-import:MURATA_MA40H1S-R_0")
      (fields
        (field (name "DIGIKEY_PART_NUMBER") "490-MA40H1S-RCT-ND")
        (field (name "MF") "Murata")
        (field (name "MOUSER_PART_NUMBER") "81-MA40H1S-R")
      )
      (libsource (lib "eagle-import") (part "MURATA_MA40H1S-RMURATA_MA40H1S-R_0_0"))
    )
    (comp (ref "U136")
      (value "MURATA_MA40H1S-RMURATA_MA40H1S-R_0_0")
      (footprint "eagle-import:MURATA_MA40H1S-R_0")
      (fields
        (field (name "DIGIKEY_PART_NUMBER") "490-MA40H1S-RCT-ND")
        (field (name "MF") "Murata")
        (field (name "MOUSER_PART_NUMBER") "81-MA40H1S-R")
      )
      (libsource (lib "eagle-import") (part "MURATA_MA40H1S-RMURATA_MA40H1S-R_0_0"))
    )
    (comp (ref "U137")
      (value "MURATA_MA40H1S-RMURATA_MA40H1S-R_0_0")
      (footprint "eagle-import:MURATA_MA40H1S-R_0")
      (fields
        (field (name "DIGIKEY_PART_NUMBER") "490-MA40H1S-RCT-ND")
        (field (name "MF") "Murata")
        (field (name "MOUSER_PART_NUMBER") "81-MA40H1S-R")
      )
      (libsource (lib "eagle-import") (part "MURATA_MA40H1S-RMURATA_MA40H1S-R_0_0"))
    )
    (comp (ref "U138")
      (value "MURATA_MA40H1S-RMURATA_MA40H1S-R_0_0")
      (footprint "eagle-import:MURATA_MA40H1S-R_0")
      (fields
        (field (name "DIGIKEY_PART_NUMBER") "490-MA40H1S-RCT-ND")
        (field (name "MF") "Murata")
        (field (name "MOUSER_PART_NUMBER") "81-MA40H1S-R")
      )
      (libsource (lib "eagle-import") (part "MURATA_MA40H1S-RMURATA_MA40H1S-R_0_0"))
    )
    (comp (ref "U139")
      (value "MURATA_MA40H1S-RMURATA_MA40H1S-R_0_0")
      (footprint "eagle-import:MURATA_MA40H1S-R_0")
      (fields
        (field (name "DIGIKEY_PART_NUMBER") "490-MA40H1S-RCT-ND")
        (field (name "MF") "Murata")
        (field (name "MOUSER_PART_NUMBER") "81-MA40H1S-R")
      )
      (libsource (lib "eagle-import") (part "MURATA_MA40H1S-RMURATA_MA40H1S-R_0_0"))
    )
    (comp (ref "U140")
      (value "MURATA_MA40H1S-RMURATA_MA40H1S-R_0_0")
      (footprint "eagle-import:MURATA_MA40H1S-R_0")
      (fields
        (field (name "DIGIKEY_PART_NUMBER") "490-MA40H1S-RCT-ND")
        (field (name "MF") "Murata")
        (field (name "MOUSER_PART_NUMBER") "81-MA40H1S-R")
      )
      (libsource (lib "eagle-import") (part "MURATA_MA40H1S-RMURATA_MA40H1S-R_0_0"))
    )
    (comp (ref "U141")
      (value "MURATA_MA40H1S-RMURATA_MA40H1S-R_0_0")
      (footprint "eagle-import:MURATA_MA40H1S-R_0")
      (fields
        (field (name "DIGIKEY_PART_NUMBER") "490-MA40H1S-RCT-ND")
        (field (name "MF") "Murata")
        (field (name "MOUSER_PART_NUMBER") "81-MA40H1S-R")
      )
      (libsource (lib "eagle-import") (part "MURATA_MA40H1S-RMURATA_MA40H1S-R_0_0"))
    )
    (comp (ref "U142")
      (value "MURATA_MA40H1S-RMURATA_MA40H1S-R_0_0")
      (footprint "eagle-import:MURATA_MA40H1S-R_0")
      (fields
        (field (name "DIGIKEY_PART_NUMBER") "490-MA40H1S-RCT-ND")
        (field (name "MF") "Murata")
        (field (name "MOUSER_PART_NUMBER") "81-MA40H1S-R")
      )
      (libsource (lib "eagle-import") (part "MURATA_MA40H1S-RMURATA_MA40H1S-R_0_0"))
    )
    (comp (ref "U143")
      (value "MURATA_MA40H1S-RMURATA_MA40H1S-R_0_0")
      (footprint "eagle-import:MURATA_MA40H1S-R_0")
      (fields
        (field (name "DIGIKEY_PART_NUMBER") "490-MA40H1S-RCT-ND")
        (field (name "MF") "Murata")
        (field (name "MOUSER_PART_NUMBER") "81-MA40H1S-R")
      )
      (libsource (lib "eagle-import") (part "MURATA_MA40H1S-RMURATA_MA40H1S-R_0_0"))
    )
    (comp (ref "U144")
      (value "MURATA_MA40H1S-RMURATA_MA40H1S-R_0_0")
      (footprint "eagle-import:MURATA_MA40H1S-R_0")
      (fields
        (field (name "DIGIKEY_PART_NUMBER") "490-MA40H1S-RCT-ND")
        (field (name "MF") "Murata")
        (field (name "MOUSER_PART_NUMBER") "81-MA40H1S-R")
      )
      (libsource (lib "eagle-import") (part "MURATA_MA40H1S-RMURATA_MA40H1S-R_0_0"))
    )
    (comp (ref "U145")
      (value "MURATA_MA40H1S-RMURATA_MA40H1S-R_0_0")
      (footprint "eagle-import:MURATA_MA40H1S-R_0")
      (fields
        (field (name "DIGIKEY_PART_NUMBER") "490-MA40H1S-RCT-ND")
        (field (name "MF") "Murata")
        (field (name "MOUSER_PART_NUMBER") "81-MA40H1S-R")
      )
      (libsource (lib "eagle-import") (part "MURATA_MA40H1S-RMURATA_MA40H1S-R_0_0"))
    )
    (comp (ref "U146")
      (value "MURATA_MA40H1S-RMURATA_MA40H1S-R_0_0")
      (footprint "eagle-import:MURATA_MA40H1S-R_0")
      (fields
        (field (name "DIGIKEY_PART_NUMBER") "490-MA40H1S-RCT-ND")
        (field (name "MF") "Murata")
        (field (name "MOUSER_PART_NUMBER") "81-MA40H1S-R")
      )
      (libsource (lib "eagle-import") (part "MURATA_MA40H1S-RMURATA_MA40H1S-R_0_0"))
    )
    (comp (ref "U147")
      (value "MURATA_MA40H1S-RMURATA_MA40H1S-R_0_0")
      (footprint "eagle-import:MURATA_MA40H1S-R_0")
      (fields
        (field (name "DIGIKEY_PART_NUMBER") "490-MA40H1S-RCT-ND")
        (field (name "MF") "Murata")
        (field (name "MOUSER_PART_NUMBER") "81-MA40H1S-R")
      )
      (libsource (lib "eagle-import") (part "MURATA_MA40H1S-RMURATA_MA40H1S-R_0_0"))
    )
    (comp (ref "U148")
      (value "MURATA_MA40H1S-RMURATA_MA40H1S-R_0_0")
      (footprint "eagle-import:MURATA_MA40H1S-R_0")
      (fields
        (field (name "DIGIKEY_PART_NUMBER") "490-MA40H1S-RCT-ND")
        (field (name "MF") "Murata")
        (field (name "MOUSER_PART_NUMBER") "81-MA40H1S-R")
      )
      (libsource (lib "eagle-import") (part "MURATA_MA40H1S-RMURATA_MA40H1S-R_0_0"))
    )
    (comp (ref "U149")
      (value "MURATA_MA40H1S-RMURATA_MA40H1S-R_0_0")
      (footprint "eagle-import:MURATA_MA40H1S-R_0")
      (fields
        (field (name "DIGIKEY_PART_NUMBER") "490-MA40H1S-RCT-ND")
        (field (name "MF") "Murata")
        (field (name "MOUSER_PART_NUMBER") "81-MA40H1S-R")
      )
      (libsource (lib "eagle-import") (part "MURATA_MA40H1S-RMURATA_MA40H1S-R_0_0"))
    )
    (comp (ref "U150")
      (value "MURATA_MA40H1S-RMURATA_MA40H1S-R_0_0")
      (footprint "eagle-import:MURATA_MA40H1S-R_0")
      (fields
        (field (name "DIGIKEY_PART_NUMBER") "490-MA40H1S-RCT-ND")
        (field (name "MF") "Murata")
        (field (name "MOUSER_PART_NUMBER") "81-MA40H1S-R")
      )
      (libsource (lib "eagle-import") (part "MURATA_MA40H1S-RMURATA_MA40H1S-R_0_0"))
    )
    (comp (ref "U151")
      (value "MURATA_MA40H1S-RMURATA_MA40H1S-R_0_0")
      (footprint "eagle-import:MURATA_MA40H1S-R_0")
      (fields
        (field (name "DIGIKEY_PART_NUMBER") "490-MA40H1S-RCT-ND")
        (field (name "MF") "Murata")
        (field (name "MOUSER_PART_NUMBER") "81-MA40H1S-R")
      )
      (libsource (lib "eagle-import") (part "MURATA_MA40H1S-RMURATA_MA40H1S-R_0_0"))
    )
    (comp (ref "U152")
      (value "MURATA_MA40H1S-RMURATA_MA40H1S-R_0_0")
      (footprint "eagle-import:MURATA_MA40H1S-R_0")
      (fields
        (field (name "DIGIKEY_PART_NUMBER") "490-MA40H1S-RCT-ND")
        (field (name "MF") "Murata")
        (field (name "MOUSER_PART_NUMBER") "81-MA40H1S-R")
      )
      (libsource (lib "eagle-import") (part "MURATA_MA40H1S-RMURATA_MA40H1S-R_0_0"))
    )
    (comp (ref "U153")
      (value "MURATA_MA40H1S-RMURATA_MA40H1S-R_0_0")
      (footprint "eagle-import:MURATA_MA40H1S-R_0")
      (fields
        (field (name "DIGIKEY_PART_NUMBER") "490-MA40H1S-RCT-ND")
        (field (name "MF") "Murata")
        (field (name "MOUSER_PART_NUMBER") "81-MA40H1S-R")
      )
      (libsource (lib "eagle-import") (part "MURATA_MA40H1S-RMURATA_MA40H1S-R_0_0"))
    )
    (comp (ref "U154")
      (value "MURATA_MA40H1S-RMURATA_MA40H1S-R_0_0")
      (footprint "eagle-import:MURATA_MA40H1S-R_0")
      (fields
        (field (name "DIGIKEY_PART_NUMBER") "490-MA40H1S-RCT-ND")
        (field (name "MF") "Murata")
        (field (name "MOUSER_PART_NUMBER") "81-MA40H1S-R")
      )
      (libsource (lib "eagle-import") (part "MURATA_MA40H1S-RMURATA_MA40H1S-R_0_0"))
    )
    (comp (ref "U155")
      (value "MURATA_MA40H1S-RMURATA_MA40H1S-R_0_0")
      (footprint "eagle-import:MURATA_MA40H1S-R_0")
      (fields
        (field (name "DIGIKEY_PART_NUMBER") "490-MA40H1S-RCT-ND")
        (field (name "MF") "Murata")
        (field (name "MOUSER_PART_NUMBER") "81-MA40H1S-R")
      )
      (libsource (lib "eagle-import") (part "MURATA_MA40H1S-RMURATA_MA40H1S-R_0_0"))
    )
    (comp (ref "U156")
      (value "MURATA_MA40H1S-RMURATA_MA40H1S-R_0_0")
      (footprint "eagle-import:MURATA_MA40H1S-R_0")
      (fields
        (field (name "DIGIKEY_PART_NUMBER") "490-MA40H1S-RCT-ND")
        (field (name "MF") "Murata")
        (field (name "MOUSER_PART_NUMBER") "81-MA40H1S-R")
      )
      (libsource (lib "eagle-import") (part "MURATA_MA40H1S-RMURATA_MA40H1S-R_0_0"))
    )
    (comp (ref "U157")
      (value "MURATA_MA40H1S-RMURATA_MA40H1S-R_0_0")
      (footprint "eagle-import:MURATA_MA40H1S-R_0")
      (fields
        (field (name "DIGIKEY_PART_NUMBER") "490-MA40H1S-RCT-ND")
        (field (name "MF") "Murata")
        (field (name "MOUSER_PART_NUMBER") "81-MA40H1S-R")
      )
      (libsource (lib "eagle-import") (part "MURATA_MA40H1S-RMURATA_MA40H1S-R_0_0"))
    )
    (comp (ref "U158")
      (value "MURATA_MA40H1S-RMURATA_MA40H1S-R_0_0")
      (footprint "eagle-import:MURATA_MA40H1S-R_0")
      (fields
        (field (name "DIGIKEY_PART_NUMBER") "490-MA40H1S-RCT-ND")
        (field (name "MF") "Murata")
        (field (name "MOUSER_PART_NUMBER") "81-MA40H1S-R")
      )
      (libsource (lib "eagle-import") (part "MURATA_MA40H1S-RMURATA_MA40H1S-R_0_0"))
    )
    (comp (ref "U159")
      (value "MURATA_MA40H1S-RMURATA_MA40H1S-R_0_0")
      (footprint "eagle-import:MURATA_MA40H1S-R_0")
      (fields
        (field (name "DIGIKEY_PART_NUMBER") "490-MA40H1S-RCT-ND")
        (field (name "MF") "Murata")
        (field (name "MOUSER_PART_NUMBER") "81-MA40H1S-R")
      )
      (libsource (lib "eagle-import") (part "MURATA_MA40H1S-RMURATA_MA40H1S-R_0_0"))
    )
    (comp (ref "U160")
      (value "MURATA_MA40H1S-RMURATA_MA40H1S-R_0_0")
      (footprint "eagle-import:MURATA_MA40H1S-R_0")
      (fields
        (field (name "DIGIKEY_PART_NUMBER") "490-MA40H1S-RCT-ND")
        (field (name "MF") "Murata")
        (field (name "MOUSER_PART_NUMBER") "81-MA40H1S-R")
      )
      (libsource (lib "eagle-import") (part "MURATA_MA40H1S-RMURATA_MA40H1S-R_0_0"))
    )
    (comp (ref "U161")
      (value "MURATA_MA40H1S-RMURATA_MA40H1S-R_0_0")
      (footprint "eagle-import:MURATA_MA40H1S-R_0")
      (fields
        (field (name "DIGIKEY_PART_NUMBER") "490-MA40H1S-RCT-ND")
        (field (name "MF") "Murata")
        (field (name "MOUSER_PART_NUMBER") "81-MA40H1S-R")
      )
      (libsource (lib "eagle-import") (part "MURATA_MA40H1S-RMURATA_MA40H1S-R_0_0"))
    )
    (comp (ref "U162")
      (value "MURATA_MA40H1S-RMURATA_MA40H1S-R_0_0")
      (footprint "eagle-import:MURATA_MA40H1S-R_0")
      (fields
        (field (name "DIGIKEY_PART_NUMBER") "490-MA40H1S-RCT-ND")
        (field (name "MF") "Murata")
        (field (name "MOUSER_PART_NUMBER") "81-MA40H1S-R")
      )
      (libsource (lib "eagle-import") (part "MURATA_MA40H1S-RMURATA_MA40H1S-R_0_0"))
    )
    (comp (ref "U163")
      (value "MURATA_MA40H1S-RMURATA_MA40H1S-R_0_0")
      (footprint "eagle-import:MURATA_MA40H1S-R_0")
      (fields
        (field (name "DIGIKEY_PART_NUMBER") "490-MA40H1S-RCT-ND")
        (field (name "MF") "Murata")
        (field (name "MOUSER_PART_NUMBER") "81-MA40H1S-R")
      )
      (libsource (lib "eagle-import") (part "MURATA_MA40H1S-RMURATA_MA40H1S-R_0_0"))
    )
    (comp (ref "U164")
      (value "MURATA_MA40H1S-RMURATA_MA40H1S-R_0_0")
      (footprint "eagle-import:MURATA_MA40H1S-R_0")
      (fields
        (field (name "DIGIKEY_PART_NUMBER") "490-MA40H1S-RCT-ND")
        (field (name "MF") "Murata")
        (field (name "MOUSER_PART_NUMBER") "81-MA40H1S-R")
      )
      (libsource (lib "eagle-import") (part "MURATA_MA40H1S-RMURATA_MA40H1S-R_0_0"))
    )
    (comp (ref "U165")
      (value "MURATA_MA40H1S-RMURATA_MA40H1S-R_0_0")
      (footprint "eagle-import:MURATA_MA40H1S-R_0")
      (fields
        (field (name "DIGIKEY_PART_NUMBER") "490-MA40H1S-RCT-ND")
        (field (name "MF") "Murata")
        (field (name "MOUSER_PART_NUMBER") "81-MA40H1S-R")
      )
      (libsource (lib "eagle-import") (part "MURATA_MA40H1S-RMURATA_MA40H1S-R_0_0"))
    )
    (comp (ref "U166")
      (value "MURATA_MA40H1S-RMURATA_MA40H1S-R_0_0")
      (footprint "eagle-import:MURATA_MA40H1S-R_0")
      (fields
        (field (name "DIGIKEY_PART_NUMBER") "490-MA40H1S-RCT-ND")
        (field (name "MF") "Murata")
        (field (name "MOUSER_PART_NUMBER") "81-MA40H1S-R")
      )
      (libsource (lib "eagle-import") (part "MURATA_MA40H1S-RMURATA_MA40H1S-R_0_0"))
    )
    (comp (ref "U167")
      (value "MURATA_MA40H1S-RMURATA_MA40H1S-R_0_0")
      (footprint "eagle-import:MURATA_MA40H1S-R_0")
      (fields
        (field (name "DIGIKEY_PART_NUMBER") "490-MA40H1S-RCT-ND")
        (field (name "MF") "Murata")
        (field (name "MOUSER_PART_NUMBER") "81-MA40H1S-R")
      )
      (libsource (lib "eagle-import") (part "MURATA_MA40H1S-RMURATA_MA40H1S-R_0_0"))
    )
    (comp (ref "U168")
      (value "MURATA_MA40H1S-RMURATA_MA40H1S-R_0_0")
      (footprint "eagle-import:MURATA_MA40H1S-R_0")
      (fields
        (field (name "DIGIKEY_PART_NUMBER") "490-MA40H1S-RCT-ND")
        (field (name "MF") "Murata")
        (field (name "MOUSER_PART_NUMBER") "81-MA40H1S-R")
      )
      (libsource (lib "eagle-import") (part "MURATA_MA40H1S-RMURATA_MA40H1S-R_0_0"))
    )
    (comp (ref "U169")
      (value "MURATA_MA40H1S-RMURATA_MA40H1S-R_0_0")
      (footprint "eagle-import:MURATA_MA40H1S-R_0")
      (fields
        (field (name "DIGIKEY_PART_NUMBER") "490-MA40H1S-RCT-ND")
        (field (name "MF") "Murata")
        (field (name "MOUSER_PART_NUMBER") "81-MA40H1S-R")
      )
      (libsource (lib "eagle-import") (part "MURATA_MA40H1S-RMURATA_MA40H1S-R_0_0"))
    )
    (comp (ref "U170")
      (value "MURATA_MA40H1S-RMURATA_MA40H1S-R_0_0")
      (footprint "eagle-import:MURATA_MA40H1S-R_0")
      (fields
        (field (name "DIGIKEY_PART_NUMBER") "490-MA40H1S-RCT-ND")
        (field (name "MF") "Murata")
        (field (name "MOUSER_PART_NUMBER") "81-MA40H1S-R")
      )
      (libsource (lib "eagle-import") (part "MURATA_MA40H1S-RMURATA_MA40H1S-R_0_0"))
    )
    (comp (ref "U171")
      (value "MURATA_MA40H1S-RMURATA_MA40H1S-R_0_0")
      (footprint "eagle-import:MURATA_MA40H1S-R_0")
      (fields
        (field (name "DIGIKEY_PART_NUMBER") "490-MA40H1S-RCT-ND")
        (field (name "MF") "Murata")
        (field (name "MOUSER_PART_NUMBER") "81-MA40H1S-R")
      )
      (libsource (lib "eagle-import") (part "MURATA_MA40H1S-RMURATA_MA40H1S-R_0_0"))
    )
    (comp (ref "U172")
      (value "MURATA_MA40H1S-RMURATA_MA40H1S-R_0_0")
      (footprint "eagle-import:MURATA_MA40H1S-R_0")
      (fields
        (field (name "DIGIKEY_PART_NUMBER") "490-MA40H1S-RCT-ND")
        (field (name "MF") "Murata")
        (field (name "MOUSER_PART_NUMBER") "81-MA40H1S-R")
      )
      (libsource (lib "eagle-import") (part "MURATA_MA40H1S-RMURATA_MA40H1S-R_0_0"))
    )
    (comp (ref "U173")
      (value "MURATA_MA40H1S-RMURATA_MA40H1S-R_0_0")
      (footprint "eagle-import:MURATA_MA40H1S-R_0")
      (fields
        (field (name "DIGIKEY_PART_NUMBER") "490-MA40H1S-RCT-ND")
        (field (name "MF") "Murata")
        (field (name "MOUSER_PART_NUMBER") "81-MA40H1S-R")
      )
      (libsource (lib "eagle-import") (part "MURATA_MA40H1S-RMURATA_MA40H1S-R_0_0"))
    )
    (comp (ref "U174")
      (value "MURATA_MA40H1S-RMURATA_MA40H1S-R_0_0")
      (footprint "eagle-import:MURATA_MA40H1S-R_0")
      (fields
        (field (name "DIGIKEY_PART_NUMBER") "490-MA40H1S-RCT-ND")
        (field (name "MF") "Murata")
        (field (name "MOUSER_PART_NUMBER") "81-MA40H1S-R")
      )
      (libsource (lib "eagle-import") (part "MURATA_MA40H1S-RMURATA_MA40H1S-R_0_0"))
    )
    (comp (ref "U175")
      (value "MURATA_MA40H1S-RMURATA_MA40H1S-R_0_0")
      (footprint "eagle-import:MURATA_MA40H1S-R_0")
      (fields
        (field (name "DIGIKEY_PART_NUMBER") "490-MA40H1S-RCT-ND")
        (field (name "MF") "Murata")
        (field (name "MOUSER_PART_NUMBER") "81-MA40H1S-R")
      )
      (libsource (lib "eagle-import") (part "MURATA_MA40H1S-RMURATA_MA40H1S-R_0_0"))
    )
    (comp (ref "U176")
      (value "MURATA_MA40H1S-RMURATA_MA40H1S-R_0_0")
      (footprint "eagle-import:MURATA_MA40H1S-R_0")
      (fields
        (field (name "DIGIKEY_PART_NUMBER") "490-MA40H1S-RCT-ND")
        (field (name "MF") "Murata")
        (field (name "MOUSER_PART_NUMBER") "81-MA40H1S-R")
      )
      (libsource (lib "eagle-import") (part "MURATA_MA40H1S-RMURATA_MA40H1S-R_0_0"))
    )
    (comp (ref "U177")
      (value "MURATA_MA40H1S-RMURATA_MA40H1S-R_0_0")
      (footprint "eagle-import:MURATA_MA40H1S-R_0")
      (fields
        (field (name "DIGIKEY_PART_NUMBER") "490-MA40H1S-RCT-ND")
        (field (name "MF") "Murata")
        (field (name "MOUSER_PART_NUMBER") "81-MA40H1S-R")
      )
      (libsource (lib "eagle-import") (part "MURATA_MA40H1S-RMURATA_MA40H1S-R_0_0"))
    )
    (comp (ref "U178")
      (value "MURATA_MA40H1S-RMURATA_MA40H1S-R_0_0")
      (footprint "eagle-import:MURATA_MA40H1S-R_0")
      (fields
        (field (name "DIGIKEY_PART_NUMBER") "490-MA40H1S-RCT-ND")
        (field (name "MF") "Murata")
        (field (name "MOUSER_PART_NUMBER") "81-MA40H1S-R")
      )
      (libsource (lib "eagle-import") (part "MURATA_MA40H1S-RMURATA_MA40H1S-R_0_0"))
    )
    (comp (ref "U179")
      (value "MURATA_MA40H1S-RMURATA_MA40H1S-R_0_0")
      (footprint "eagle-import:MURATA_MA40H1S-R_0")
      (fields
        (field (name "DIGIKEY_PART_NUMBER") "490-MA40H1S-RCT-ND")
        (field (name "MF") "Murata")
        (field (name "MOUSER_PART_NUMBER") "81-MA40H1S-R")
      )
      (libsource (lib "eagle-import") (part "MURATA_MA40H1S-RMURATA_MA40H1S-R_0_0"))
    )
    (comp (ref "U180")
      (value "MURATA_MA40H1S-RMURATA_MA40H1S-R_0_0")
      (footprint "eagle-import:MURATA_MA40H1S-R_0")
      (fields
        (field (name "DIGIKEY_PART_NUMBER") "490-MA40H1S-RCT-ND")
        (field (name "MF") "Murata")
        (field (name "MOUSER_PART_NUMBER") "81-MA40H1S-R")
      )
      (libsource (lib "eagle-import") (part "MURATA_MA40H1S-RMURATA_MA40H1S-R_0_0"))
    )
    (comp (ref "U184")
      (value "MURATA_MA40H1S-RMURATA_MA40H1S-R_0_0")
      (footprint "eagle-import:MURATA_MA40H1S-R_0")
      (fields
        (field (name "DIGIKEY_PART_NUMBER") "490-MA40H1S-RCT-ND")
        (field (name "MF") "Murata")
        (field (name "MOUSER_PART_NUMBER") "81-MA40H1S-R")
      )
      (libsource (lib "eagle-import") (part "MURATA_MA40H1S-RMURATA_MA40H1S-R_0_0"))
    )
    (comp (ref "U185")
      (value "MURATA_MA40H1S-RMURATA_MA40H1S-R_0_0")
      (footprint "eagle-import:MURATA_MA40H1S-R_0")
      (fields
        (field (name "DIGIKEY_PART_NUMBER") "490-MA40H1S-RCT-ND")
        (field (name "MF") "Murata")
        (field (name "MOUSER_PART_NUMBER") "81-MA40H1S-R")
      )
      (libsource (lib "eagle-import") (part "MURATA_MA40H1S-RMURATA_MA40H1S-R_0_0"))
    )
    (comp (ref "U186")
      (value "MURATA_MA40H1S-RMURATA_MA40H1S-R_0_0")
      (footprint "eagle-import:MURATA_MA40H1S-R_0")
      (fields
        (field (name "DIGIKEY_PART_NUMBER") "490-MA40H1S-RCT-ND")
        (field (name "MF") "Murata")
        (field (name "MOUSER_PART_NUMBER") "81-MA40H1S-R")
      )
      (libsource (lib "eagle-import") (part "MURATA_MA40H1S-RMURATA_MA40H1S-R_0_0"))
    )
    (comp (ref "U192")
      (value "MURATA_MA40H1S-RMURATA_MA40H1S-R_0_0")
      (footprint "eagle-import:MURATA_MA40H1S-R_0")
      (fields
        (field (name "DIGIKEY_PART_NUMBER") "490-MA40H1S-RCT-ND")
        (field (name "MF") "Murata")
        (field (name "MOUSER_PART_NUMBER") "81-MA40H1S-R")
      )
      (libsource (lib "eagle-import") (part "MURATA_MA40H1S-RMURATA_MA40H1S-R_0_0"))
    )
    (comp (ref "U193")
      (value "MURATA_MA40H1S-RMURATA_MA40H1S-R_0_0")
      (footprint "eagle-import:MURATA_MA40H1S-R_0")
      (fields
        (field (name "DIGIKEY_PART_NUMBER") "490-MA40H1S-RCT-ND")
        (field (name "MF") "Murata")
        (field (name "MOUSER_PART_NUMBER") "81-MA40H1S-R")
      )
      (libsource (lib "eagle-import") (part "MURATA_MA40H1S-RMURATA_MA40H1S-R_0_0"))
    )
    (comp (ref "U194")
      (value "MURATA_MA40H1S-RMURATA_MA40H1S-R_0_0")
      (footprint "eagle-import:MURATA_MA40H1S-R_0")
      (fields
        (field (name "DIGIKEY_PART_NUMBER") "490-MA40H1S-RCT-ND")
        (field (name "MF") "Murata")
        (field (name "MOUSER_PART_NUMBER") "81-MA40H1S-R")
      )
      (libsource (lib "eagle-import") (part "MURATA_MA40H1S-RMURATA_MA40H1S-R_0_0"))
    )
    (comp (ref "U195")
      (value "MURATA_MA40H1S-RMURATA_MA40H1S-R_0_0")
      (footprint "eagle-import:MURATA_MA40H1S-R_0")
      (fields
        (field (name "DIGIKEY_PART_NUMBER") "490-MA40H1S-RCT-ND")
        (field (name "MF") "Murata")
        (field (name "MOUSER_PART_NUMBER") "81-MA40H1S-R")
      )
      (libsource (lib "eagle-import") (part "MURATA_MA40H1S-RMURATA_MA40H1S-R_0_0"))
    )
    (comp (ref "U196")
      (value "MURATA_MA40H1S-RMURATA_MA40H1S-R_0_0")
      (footprint "eagle-import:MURATA_MA40H1S-R_0")
      (fields
        (field (name "DIGIKEY_PART_NUMBER") "490-MA40H1S-RCT-ND")
        (field (name "MF") "Murata")
        (field (name "MOUSER_PART_NUMBER") "81-MA40H1S-R")
      )
      (libsource (lib "eagle-import") (part "MURATA_MA40H1S-RMURATA_MA40H1S-R_0_0"))
    )
    (comp (ref "U197")
      (value "MURATA_MA40H1S-RMURATA_MA40H1S-R_0_0")
      (footprint "eagle-import:MURATA_MA40H1S-R_0")
      (fields
        (field (name "DIGIKEY_PART_NUMBER") "490-MA40H1S-RCT-ND")
        (field (name "MF") "Murata")
        (field (name "MOUSER_PART_NUMBER") "81-MA40H1S-R")
      )
      (libsource (lib "eagle-import") (part "MURATA_MA40H1S-RMURATA_MA40H1S-R_0_0"))
    )
    (comp (ref "U198")
      (value "MURATA_MA40H1S-RMURATA_MA40H1S-R_0_0")
      (footprint "eagle-import:MURATA_MA40H1S-R_0")
      (fields
        (field (name "DIGIKEY_PART_NUMBER") "490-MA40H1S-RCT-ND")
        (field (name "MF") "Murata")
        (field (name "MOUSER_PART_NUMBER") "81-MA40H1S-R")
      )
      (libsource (lib "eagle-import") (part "MURATA_MA40H1S-RMURATA_MA40H1S-R_0_0"))
    )
    (comp (ref "U199")
      (value "MURATA_MA40H1S-RMURATA_MA40H1S-R_0_0")
      (footprint "eagle-import:MURATA_MA40H1S-R_0")
      (fields
        (field (name "DIGIKEY_PART_NUMBER") "490-MA40H1S-RCT-ND")
        (field (name "MF") "Murata")
        (field (name "MOUSER_PART_NUMBER") "81-MA40H1S-R")
      )
      (libsource (lib "eagle-import") (part "MURATA_MA40H1S-RMURATA_MA40H1S-R_0_0"))
    )
    (comp (ref "U200")
      (value "MURATA_MA40H1S-RMURATA_MA40H1S-R_0_0")
      (footprint "eagle-import:MURATA_MA40H1S-R_0")
      (fields
        (field (name "DIGIKEY_PART_NUMBER") "490-MA40H1S-RCT-ND")
        (field (name "MF") "Murata")
        (field (name "MOUSER_PART_NUMBER") "81-MA40H1S-R")
      )
      (libsource (lib "eagle-import") (part "MURATA_MA40H1S-RMURATA_MA40H1S-R_0_0"))
    )
    (comp (ref "U201")
      (value "MURATA_MA40H1S-RMURATA_MA40H1S-R_0_0")
      (footprint "eagle-import:MURATA_MA40H1S-R_0")
      (fields
        (field (name "DIGIKEY_PART_NUMBER") "490-MA40H1S-RCT-ND")
        (field (name "MF") "Murata")
        (field (name "MOUSER_PART_NUMBER") "81-MA40H1S-R")
      )
      (libsource (lib "eagle-import") (part "MURATA_MA40H1S-RMURATA_MA40H1S-R_0_0"))
    )
    (comp (ref "U202")
      (value "MURATA_MA40H1S-RMURATA_MA40H1S-R_0_0")
      (footprint "eagle-import:MURATA_MA40H1S-R_0")
      (fields
        (field (name "DIGIKEY_PART_NUMBER") "490-MA40H1S-RCT-ND")
        (field (name "MF") "Murata")
        (field (name "MOUSER_PART_NUMBER") "81-MA40H1S-R")
      )
      (libsource (lib "eagle-import") (part "MURATA_MA40H1S-RMURATA_MA40H1S-R_0_0"))
    )
    (comp (ref "U203")
      (value "MURATA_MA40H1S-RMURATA_MA40H1S-R_0_0")
      (footprint "eagle-import:MURATA_MA40H1S-R_0")
      (fields
        (field (name "DIGIKEY_PART_NUMBER") "490-MA40H1S-RCT-ND")
        (field (name "MF") "Murata")
        (field (name "MOUSER_PART_NUMBER") "81-MA40H1S-R")
      )
      (libsource (lib "eagle-import") (part "MURATA_MA40H1S-RMURATA_MA40H1S-R_0_0"))
    )
    (comp (ref "U204")
      (value "MURATA_MA40H1S-RMURATA_MA40H1S-R_0_0")
      (footprint "eagle-import:MURATA_MA40H1S-R_0")
      (fields
        (field (name "DIGIKEY_PART_NUMBER") "490-MA40H1S-RCT-ND")
        (field (name "MF") "Murata")
        (field (name "MOUSER_PART_NUMBER") "81-MA40H1S-R")
      )
      (libsource (lib "eagle-import") (part "MURATA_MA40H1S-RMURATA_MA40H1S-R_0_0"))
    )
    (comp (ref "U205")
      (value "MURATA_MA40H1S-RMURATA_MA40H1S-R_0_0")
      (footprint "eagle-import:MURATA_MA40H1S-R_0")
      (fields
        (field (name "DIGIKEY_PART_NUMBER") "490-MA40H1S-RCT-ND")
        (field (name "MF") "Murata")
        (field (name "MOUSER_PART_NUMBER") "81-MA40H1S-R")
      )
      (libsource (lib "eagle-import") (part "MURATA_MA40H1S-RMURATA_MA40H1S-R_0_0"))
    )
    (comp (ref "U206")
      (value "MURATA_MA40H1S-RMURATA_MA40H1S-R_0_0")
      (footprint "eagle-import:MURATA_MA40H1S-R_0")
      (fields
        (field (name "DIGIKEY_PART_NUMBER") "490-MA40H1S-RCT-ND")
        (field (name "MF") "Murata")
        (field (name "MOUSER_PART_NUMBER") "81-MA40H1S-R")
      )
      (libsource (lib "eagle-import") (part "MURATA_MA40H1S-RMURATA_MA40H1S-R_0_0"))
    )
    (comp (ref "U207")
      (value "MURATA_MA40H1S-RMURATA_MA40H1S-R_0_0")
      (footprint "eagle-import:MURATA_MA40H1S-R_0")
      (fields
        (field (name "DIGIKEY_PART_NUMBER") "490-MA40H1S-RCT-ND")
        (field (name "MF") "Murata")
        (field (name "MOUSER_PART_NUMBER") "81-MA40H1S-R")
      )
      (libsource (lib "eagle-import") (part "MURATA_MA40H1S-RMURATA_MA40H1S-R_0_0"))
    )
    (comp (ref "U208")
      (value "MURATA_MA40H1S-RMURATA_MA40H1S-R_0_0")
      (footprint "eagle-import:MURATA_MA40H1S-R_0")
      (fields
        (field (name "DIGIKEY_PART_NUMBER") "490-MA40H1S-RCT-ND")
        (field (name "MF") "Murata")
        (field (name "MOUSER_PART_NUMBER") "81-MA40H1S-R")
      )
      (libsource (lib "eagle-import") (part "MURATA_MA40H1S-RMURATA_MA40H1S-R_0_0"))
    )
    (comp (ref "U209")
      (value "MURATA_MA40H1S-RMURATA_MA40H1S-R_0_0")
      (footprint "eagle-import:MURATA_MA40H1S-R_0")
      (fields
        (field (name "DIGIKEY_PART_NUMBER") "490-MA40H1S-RCT-ND")
        (field (name "MF") "Murata")
        (field (name "MOUSER_PART_NUMBER") "81-MA40H1S-R")
      )
      (libsource (lib "eagle-import") (part "MURATA_MA40H1S-RMURATA_MA40H1S-R_0_0"))
    )
    (comp (ref "U210")
      (value "MURATA_MA40H1S-RMURATA_MA40H1S-R_0_0")
      (footprint "eagle-import:MURATA_MA40H1S-R_0")
      (fields
        (field (name "DIGIKEY_PART_NUMBER") "490-MA40H1S-RCT-ND")
        (field (name "MF") "Murata")
        (field (name "MOUSER_PART_NUMBER") "81-MA40H1S-R")
      )
      (libsource (lib "eagle-import") (part "MURATA_MA40H1S-RMURATA_MA40H1S-R_0_0"))
    )
    (comp (ref "U211")
      (value "MURATA_MA40H1S-RMURATA_MA40H1S-R_0_0")
      (footprint "eagle-import:MURATA_MA40H1S-R_0")
      (fields
        (field (name "DIGIKEY_PART_NUMBER") "490-MA40H1S-RCT-ND")
        (field (name "MF") "Murata")
        (field (name "MOUSER_PART_NUMBER") "81-MA40H1S-R")
      )
      (libsource (lib "eagle-import") (part "MURATA_MA40H1S-RMURATA_MA40H1S-R_0_0"))
    )
    (comp (ref "U212")
      (value "MURATA_MA40H1S-RMURATA_MA40H1S-R_0_0")
      (footprint "eagle-import:MURATA_MA40H1S-R_0")
      (fields
        (field (name "DIGIKEY_PART_NUMBER") "490-MA40H1S-RCT-ND")
        (field (name "MF") "Murata")
        (field (name "MOUSER_PART_NUMBER") "81-MA40H1S-R")
      )
      (libsource (lib "eagle-import") (part "MURATA_MA40H1S-RMURATA_MA40H1S-R_0_0"))
    )
    (comp (ref "U213")
      (value "MURATA_MA40H1S-RMURATA_MA40H1S-R_0_0")
      (footprint "eagle-import:MURATA_MA40H1S-R_0")
      (fields
        (field (name "DIGIKEY_PART_NUMBER") "490-MA40H1S-RCT-ND")
        (field (name "MF") "Murata")
        (field (name "MOUSER_PART_NUMBER") "81-MA40H1S-R")
      )
      (libsource (lib "eagle-import") (part "MURATA_MA40H1S-RMURATA_MA40H1S-R_0_0"))
    )
    (comp (ref "U214")
      (value "MURATA_MA40H1S-RMURATA_MA40H1S-R_0_0")
      (footprint "eagle-import:MURATA_MA40H1S-R_0")
      (fields
        (field (name "DIGIKEY_PART_NUMBER") "490-MA40H1S-RCT-ND")
        (field (name "MF") "Murata")
        (field (name "MOUSER_PART_NUMBER") "81-MA40H1S-R")
      )
      (libsource (lib "eagle-import") (part "MURATA_MA40H1S-RMURATA_MA40H1S-R_0_0"))
    )
    (comp (ref "U215")
      (value "MURATA_MA40H1S-RMURATA_MA40H1S-R_0_0")
      (footprint "eagle-import:MURATA_MA40H1S-R_0")
      (fields
        (field (name "DIGIKEY_PART_NUMBER") "490-MA40H1S-RCT-ND")
        (field (name "MF") "Murata")
        (field (name "MOUSER_PART_NUMBER") "81-MA40H1S-R")
      )
      (libsource (lib "eagle-import") (part "MURATA_MA40H1S-RMURATA_MA40H1S-R_0_0"))
    )
    (comp (ref "U216")
      (value "MURATA_MA40H1S-RMURATA_MA40H1S-R_0_0")
      (footprint "eagle-import:MURATA_MA40H1S-R_0")
      (fields
        (field (name "DIGIKEY_PART_NUMBER") "490-MA40H1S-RCT-ND")
        (field (name "MF") "Murata")
        (field (name "MOUSER_PART_NUMBER") "81-MA40H1S-R")
      )
      (libsource (lib "eagle-import") (part "MURATA_MA40H1S-RMURATA_MA40H1S-R_0_0"))
    )
    (comp (ref "U217")
      (value "MURATA_MA40H1S-RMURATA_MA40H1S-R_0_0")
      (footprint "eagle-import:MURATA_MA40H1S-R_0")
      (fields
        (field (name "DIGIKEY_PART_NUMBER") "490-MA40H1S-RCT-ND")
        (field (name "MF") "Murata")
        (field (name "MOUSER_PART_NUMBER") "81-MA40H1S-R")
      )
      (libsource (lib "eagle-import") (part "MURATA_MA40H1S-RMURATA_MA40H1S-R_0_0"))
    )
    (comp (ref "U218")
      (value "MURATA_MA40H1S-RMURATA_MA40H1S-R_0_0")
      (footprint "eagle-import:MURATA_MA40H1S-R_0")
      (fields
        (field (name "DIGIKEY_PART_NUMBER") "490-MA40H1S-RCT-ND")
        (field (name "MF") "Murata")
        (field (name "MOUSER_PART_NUMBER") "81-MA40H1S-R")
      )
      (libsource (lib "eagle-import") (part "MURATA_MA40H1S-RMURATA_MA40H1S-R_0_0"))
    )
    (comp (ref "U219")
      (value "MURATA_MA40H1S-RMURATA_MA40H1S-R_0_0")
      (footprint "eagle-import:MURATA_MA40H1S-R_0")
      (fields
        (field (name "DIGIKEY_PART_NUMBER") "490-MA40H1S-RCT-ND")
        (field (name "MF") "Murata")
        (field (name "MOUSER_PART_NUMBER") "81-MA40H1S-R")
      )
      (libsource (lib "eagle-import") (part "MURATA_MA40H1S-RMURATA_MA40H1S-R_0_0"))
    )
    (comp (ref "U220")
      (value "MURATA_MA40H1S-RMURATA_MA40H1S-R_0_0")
      (footprint "eagle-import:MURATA_MA40H1S-R_0")
      (fields
        (field (name "DIGIKEY_PART_NUMBER") "490-MA40H1S-RCT-ND")
        (field (name "MF") "Murata")
        (field (name "MOUSER_PART_NUMBER") "81-MA40H1S-R")
      )
      (libsource (lib "eagle-import") (part "MURATA_MA40H1S-RMURATA_MA40H1S-R_0_0"))
    )
    (comp (ref "U221")
      (value "MURATA_MA40H1S-RMURATA_MA40H1S-R_0_0")
      (footprint "eagle-import:MURATA_MA40H1S-R_0")
      (fields
        (field (name "DIGIKEY_PART_NUMBER") "490-MA40H1S-RCT-ND")
        (field (name "MF") "Murata")
        (field (name "MOUSER_PART_NUMBER") "81-MA40H1S-R")
      )
      (libsource (lib "eagle-import") (part "MURATA_MA40H1S-RMURATA_MA40H1S-R_0_0"))
    )
    (comp (ref "U222")
      (value "MURATA_MA40H1S-RMURATA_MA40H1S-R_0_0")
      (footprint "eagle-import:MURATA_MA40H1S-R_0")
      (fields
        (field (name "DIGIKEY_PART_NUMBER") "490-MA40H1S-RCT-ND")
        (field (name "MF") "Murata")
        (field (name "MOUSER_PART_NUMBER") "81-MA40H1S-R")
      )
      (libsource (lib "eagle-import") (part "MURATA_MA40H1S-RMURATA_MA40H1S-R_0_0"))
    )
    (comp (ref "U223")
      (value "MURATA_MA40H1S-RMURATA_MA40H1S-R_0_0")
      (footprint "eagle-import:MURATA_MA40H1S-R_0")
      (fields
        (field (name "DIGIKEY_PART_NUMBER") "490-MA40H1S-RCT-ND")
        (field (name "MF") "Murata")
        (field (name "MOUSER_PART_NUMBER") "81-MA40H1S-R")
      )
      (libsource (lib "eagle-import") (part "MURATA_MA40H1S-RMURATA_MA40H1S-R_0_0"))
    )
    (comp (ref "U224")
      (value "MURATA_MA40H1S-RMURATA_MA40H1S-R_0_0")
      (footprint "eagle-import:MURATA_MA40H1S-R_0")
      (fields
        (field (name "DIGIKEY_PART_NUMBER") "490-MA40H1S-RCT-ND")
        (field (name "MF") "Murata")
        (field (name "MOUSER_PART_NUMBER") "81-MA40H1S-R")
      )
      (libsource (lib "eagle-import") (part "MURATA_MA40H1S-RMURATA_MA40H1S-R_0_0"))
    )
    (comp (ref "U225")
      (value "MURATA_MA40H1S-RMURATA_MA40H1S-R_0_0")
      (footprint "eagle-import:MURATA_MA40H1S-R_0")
      (fields
        (field (name "DIGIKEY_PART_NUMBER") "490-MA40H1S-RCT-ND")
        (field (name "MF") "Murata")
        (field (name "MOUSER_PART_NUMBER") "81-MA40H1S-R")
      )
      (libsource (lib "eagle-import") (part "MURATA_MA40H1S-RMURATA_MA40H1S-R_0_0"))
    )
    (comp (ref "U226")
      (value "MURATA_MA40H1S-RMURATA_MA40H1S-R_0_0")
      (footprint "eagle-import:MURATA_MA40H1S-R_0")
      (fields
        (field (name "DIGIKEY_PART_NUMBER") "490-MA40H1S-RCT-ND")
        (field (name "MF") "Murata")
        (field (name "MOUSER_PART_NUMBER") "81-MA40H1S-R")
      )
      (libsource (lib "eagle-import") (part "MURATA_MA40H1S-RMURATA_MA40H1S-R_0_0"))
    )
    (comp (ref "U227")
      (value "MURATA_MA40H1S-RMURATA_MA40H1S-R_0_0")
      (footprint "eagle-import:MURATA_MA40H1S-R_0")
      (fields
        (field (name "DIGIKEY_PART_NUMBER") "490-MA40H1S-RCT-ND")
        (field (name "MF") "Murata")
        (field (name "MOUSER_PART_NUMBER") "81-MA40H1S-R")
      )
      (libsource (lib "eagle-import") (part "MURATA_MA40H1S-RMURATA_MA40H1S-R_0_0"))
    )
    (comp (ref "U228")
      (value "MURATA_MA40H1S-RMURATA_MA40H1S-R_0_0")
      (footprint "eagle-import:MURATA_MA40H1S-R_0")
      (fields
        (field (name "DIGIKEY_PART_NUMBER") "490-MA40H1S-RCT-ND")
        (field (name "MF") "Murata")
        (field (name "MOUSER_PART_NUMBER") "81-MA40H1S-R")
      )
      (libsource (lib "eagle-import") (part "MURATA_MA40H1S-RMURATA_MA40H1S-R_0_0"))
    )
    (comp (ref "U229")
      (value "MURATA_MA40H1S-RMURATA_MA40H1S-R_0_0")
      (footprint "eagle-import:MURATA_MA40H1S-R_0")
      (fields
        (field (name "DIGIKEY_PART_NUMBER") "490-MA40H1S-RCT-ND")
        (field (name "MF") "Murata")
        (field (name "MOUSER_PART_NUMBER") "81-MA40H1S-R")
      )
      (libsource (lib "eagle-import") (part "MURATA_MA40H1S-RMURATA_MA40H1S-R_0_0"))
    )
    (comp (ref "U230")
      (value "MURATA_MA40H1S-RMURATA_MA40H1S-R_0_0")
      (footprint "eagle-import:MURATA_MA40H1S-R_0")
      (fields
        (field (name "DIGIKEY_PART_NUMBER") "490-MA40H1S-RCT-ND")
        (field (name "MF") "Murata")
        (field (name "MOUSER_PART_NUMBER") "81-MA40H1S-R")
      )
      (libsource (lib "eagle-import") (part "MURATA_MA40H1S-RMURATA_MA40H1S-R_0_0"))
    )
    (comp (ref "U231")
      (value "MURATA_MA40H1S-RMURATA_MA40H1S-R_0_0")
      (footprint "eagle-import:MURATA_MA40H1S-R_0")
      (fields
        (field (name "DIGIKEY_PART_NUMBER") "490-MA40H1S-RCT-ND")
        (field (name "MF") "Murata")
        (field (name "MOUSER_PART_NUMBER") "81-MA40H1S-R")
      )
      (libsource (lib "eagle-import") (part "MURATA_MA40H1S-RMURATA_MA40H1S-R_0_0"))
    )
    (comp (ref "U232")
      (value "MURATA_MA40H1S-RMURATA_MA40H1S-R_0_0")
      (footprint "eagle-import:MURATA_MA40H1S-R_0")
      (fields
        (field (name "DIGIKEY_PART_NUMBER") "490-MA40H1S-RCT-ND")
        (field (name "MF") "Murata")
        (field (name "MOUSER_PART_NUMBER") "81-MA40H1S-R")
      )
      (libsource (lib "eagle-import") (part "MURATA_MA40H1S-RMURATA_MA40H1S-R_0_0"))
    )
    (comp (ref "U233")
      (value "MURATA_MA40H1S-RMURATA_MA40H1S-R_0_0")
      (footprint "eagle-import:MURATA_MA40H1S-R_0")
      (fields
        (field (name "DIGIKEY_PART_NUMBER") "490-MA40H1S-RCT-ND")
        (field (name "MF") "Murata")
        (field (name "MOUSER_PART_NUMBER") "81-MA40H1S-R")
      )
      (libsource (lib "eagle-import") (part "MURATA_MA40H1S-RMURATA_MA40H1S-R_0_0"))
    )
    (comp (ref "U234")
      (value "MURATA_MA40H1S-RMURATA_MA40H1S-R_0_0")
      (footprint "eagle-import:MURATA_MA40H1S-R_0")
      (fields
        (field (name "DIGIKEY_PART_NUMBER") "490-MA40H1S-RCT-ND")
        (field (name "MF") "Murata")
        (field (name "MOUSER_PART_NUMBER") "81-MA40H1S-R")
      )
      (libsource (lib "eagle-import") (part "MURATA_MA40H1S-RMURATA_MA40H1S-R_0_0"))
    )
    (comp (ref "U235")
      (value "MURATA_MA40H1S-RMURATA_MA40H1S-R_0_0")
      (footprint "eagle-import:MURATA_MA40H1S-R_0")
      (fields
        (field (name "DIGIKEY_PART_NUMBER") "490-MA40H1S-RCT-ND")
        (field (name "MF") "Murata")
        (field (name "MOUSER_PART_NUMBER") "81-MA40H1S-R")
      )
      (libsource (lib "eagle-import") (part "MURATA_MA40H1S-RMURATA_MA40H1S-R_0_0"))
    )
    (comp (ref "U236")
      (value "MURATA_MA40H1S-RMURATA_MA40H1S-R_0_0")
      (footprint "eagle-import:MURATA_MA40H1S-R_0")
      (fields
        (field (name "DIGIKEY_PART_NUMBER") "490-MA40H1S-RCT-ND")
        (field (name "MF") "Murata")
        (field (name "MOUSER_PART_NUMBER") "81-MA40H1S-R")
      )
      (libsource (lib "eagle-import") (part "MURATA_MA40H1S-RMURATA_MA40H1S-R_0_0"))
    )
    (comp (ref "U237")
      (value "MURATA_MA40H1S-RMURATA_MA40H1S-R_0_0")
      (footprint "eagle-import:MURATA_MA40H1S-R_0")
      (fields
        (field (name "DIGIKEY_PART_NUMBER") "490-MA40H1S-RCT-ND")
        (field (name "MF") "Murata")
        (field (name "MOUSER_PART_NUMBER") "81-MA40H1S-R")
      )
      (libsource (lib "eagle-import") (part "MURATA_MA40H1S-RMURATA_MA40H1S-R_0_0"))
    )
    (comp (ref "U238")
      (value "MURATA_MA40H1S-RMURATA_MA40H1S-R_0_0")
      (footprint "eagle-import:MURATA_MA40H1S-R_0")
      (fields
        (field (name "DIGIKEY_PART_NUMBER") "490-MA40H1S-RCT-ND")
        (field (name "MF") "Murata")
        (field (name "MOUSER_PART_NUMBER") "81-MA40H1S-R")
      )
      (libsource (lib "eagle-import") (part "MURATA_MA40H1S-RMURATA_MA40H1S-R_0_0"))
    )
    (comp (ref "U239")
      (value "MURATA_MA40H1S-RMURATA_MA40H1S-R_0_0")
      (footprint "eagle-import:MURATA_MA40H1S-R_0")
      (fields
        (field (name "DIGIKEY_PART_NUMBER") "490-MA40H1S-RCT-ND")
        (field (name "MF") "Murata")
        (field (name "MOUSER_PART_NUMBER") "81-MA40H1S-R")
      )
      (libsource (lib "eagle-import") (part "MURATA_MA40H1S-RMURATA_MA40H1S-R_0_0"))
    )
    (comp (ref "U240")
      (value "MURATA_MA40H1S-RMURATA_MA40H1S-R_0_0")
      (footprint "eagle-import:MURATA_MA40H1S-R_0")
      (fields
        (field (name "DIGIKEY_PART_NUMBER") "490-MA40H1S-RCT-ND")
        (field (name "MF") "Murata")
        (field (name "MOUSER_PART_NUMBER") "81-MA40H1S-R")
      )
      (libsource (lib "eagle-import") (part "MURATA_MA40H1S-RMURATA_MA40H1S-R_0_0"))
    )
    (comp (ref "U241")
      (value "MURATA_MA40H1S-RMURATA_MA40H1S-R_0_0")
      (footprint "eagle-import:MURATA_MA40H1S-R_0")
      (fields
        (field (name "DIGIKEY_PART_NUMBER") "490-MA40H1S-RCT-ND")
        (field (name "MF") "Murata")
        (field (name "MOUSER_PART_NUMBER") "81-MA40H1S-R")
      )
      (libsource (lib "eagle-import") (part "MURATA_MA40H1S-RMURATA_MA40H1S-R_0_0"))
    )
    (comp (ref "U242")
      (value "MURATA_MA40H1S-RMURATA_MA40H1S-R_0_0")
      (footprint "eagle-import:MURATA_MA40H1S-R_0")
      (fields
        (field (name "DIGIKEY_PART_NUMBER") "490-MA40H1S-RCT-ND")
        (field (name "MF") "Murata")
        (field (name "MOUSER_PART_NUMBER") "81-MA40H1S-R")
      )
      (libsource (lib "eagle-import") (part "MURATA_MA40H1S-RMURATA_MA40H1S-R_0_0"))
    )
    (comp (ref "U246")
      (value "MURATA_MA40H1S-RMURATA_MA40H1S-R_0_0")
      (footprint "eagle-import:MURATA_MA40H1S-R_0")
      (fields
        (field (name "DIGIKEY_PART_NUMBER") "490-MA40H1S-RCT-ND")
        (field (name "MF") "Murata")
        (field (name "MOUSER_PART_NUMBER") "81-MA40H1S-R")
      )
      (libsource (lib "eagle-import") (part "MURATA_MA40H1S-RMURATA_MA40H1S-R_0_0"))
    )
    (comp (ref "U247")
      (value "MURATA_MA40H1S-RMURATA_MA40H1S-R_0_0")
      (footprint "eagle-import:MURATA_MA40H1S-R_0")
      (fields
        (field (name "DIGIKEY_PART_NUMBER") "490-MA40H1S-RCT-ND")
        (field (name "MF") "Murata")
        (field (name "MOUSER_PART_NUMBER") "81-MA40H1S-R")
      )
      (libsource (lib "eagle-import") (part "MURATA_MA40H1S-RMURATA_MA40H1S-R_0_0"))
    )
    (comp (ref "U248")
      (value "MURATA_MA40H1S-RMURATA_MA40H1S-R_0_0")
      (footprint "eagle-import:MURATA_MA40H1S-R_0")
      (fields
        (field (name "DIGIKEY_PART_NUMBER") "490-MA40H1S-RCT-ND")
        (field (name "MF") "Murata")
        (field (name "MOUSER_PART_NUMBER") "81-MA40H1S-R")
      )
      (libsource (lib "eagle-import") (part "MURATA_MA40H1S-RMURATA_MA40H1S-R_0_0"))
    )
    (comp (ref "U249")
      (value "MURATA_MA40H1S-RMURATA_MA40H1S-R_0_0")
      (footprint "eagle-import:MURATA_MA40H1S-R_0")
      (fields
        (field (name "DIGIKEY_PART_NUMBER") "490-MA40H1S-RCT-ND")
        (field (name "MF") "Murata")
        (field (name "MOUSER_PART_NUMBER") "81-MA40H1S-R")
      )
      (libsource (lib "eagle-import") (part "MURATA_MA40H1S-RMURATA_MA40H1S-R_0_0"))
    )
    (comp (ref "U250")
      (value "MURATA_MA40H1S-RMURATA_MA40H1S-R_0_0")
      (footprint "eagle-import:MURATA_MA40H1S-R_0")
      (fields
        (field (name "DIGIKEY_PART_NUMBER") "490-MA40H1S-RCT-ND")
        (field (name "MF") "Murata")
        (field (name "MOUSER_PART_NUMBER") "81-MA40H1S-R")
      )
      (libsource (lib "eagle-import") (part "MURATA_MA40H1S-RMURATA_MA40H1S-R_0_0"))
    )
    (comp (ref "U251")
      (value "MURATA_MA40H1S-RMURATA_MA40H1S-R_0_0")
      (footprint "eagle-import:MURATA_MA40H1S-R_0")
      (fields
        (field (name "DIGIKEY_PART_NUMBER") "490-MA40H1S-RCT-ND")
        (field (name "MF") "Murata")
        (field (name "MOUSER_PART_NUMBER") "81-MA40H1S-R")
      )
      (libsource (lib "eagle-import") (part "MURATA_MA40H1S-RMURATA_MA40H1S-R_0_0"))
    )
    (comp (ref "U252")
      (value "MURATA_MA40H1S-RMURATA_MA40H1S-R_0_0")
      (footprint "eagle-import:MURATA_MA40H1S-R_0")
      (fields
        (field (name "DIGIKEY_PART_NUMBER") "490-MA40H1S-RCT-ND")
        (field (name "MF") "Murata")
        (field (name "MOUSER_PART_NUMBER") "81-MA40H1S-R")
      )
      (libsource (lib "eagle-import") (part "MURATA_MA40H1S-RMURATA_MA40H1S-R_0_0"))
    )
    (comp (ref "U253")
      (value "MURATA_MA40H1S-RMURATA_MA40H1S-R_0_0")
      (footprint "eagle-import:MURATA_MA40H1S-R_0")
      (fields
        (field (name "DIGIKEY_PART_NUMBER") "490-MA40H1S-RCT-ND")
        (field (name "MF") "Murata")
        (field (name "MOUSER_PART_NUMBER") "81-MA40H1S-R")
      )
      (libsource (lib "eagle-import") (part "MURATA_MA40H1S-RMURATA_MA40H1S-R_0_0"))
    )
    (comp (ref "U254")
      (value "MURATA_MA40H1S-RMURATA_MA40H1S-R_0_0")
      (footprint "eagle-import:MURATA_MA40H1S-R_0")
      (fields
        (field (name "DIGIKEY_PART_NUMBER") "490-MA40H1S-RCT-ND")
        (field (name "MF") "Murata")
        (field (name "MOUSER_PART_NUMBER") "81-MA40H1S-R")
      )
      (libsource (lib "eagle-import") (part "MURATA_MA40H1S-RMURATA_MA40H1S-R_0_0"))
    )
    (comp (ref "U255")
      (value "MURATA_MA40H1S-RMURATA_MA40H1S-R_0_0")
      (footprint "eagle-import:MURATA_MA40H1S-R_0")
      (fields
        (field (name "DIGIKEY_PART_NUMBER") "490-MA40H1S-RCT-ND")
        (field (name "MF") "Murata")
        (field (name "MOUSER_PART_NUMBER") "81-MA40H1S-R")
      )
      (libsource (lib "eagle-import") (part "MURATA_MA40H1S-RMURATA_MA40H1S-R_0_0"))
    )
    (comp (ref "U256")
      (value "MURATA_MA40H1S-RMURATA_MA40H1S-R_0_0")
      (footprint "eagle-import:MURATA_MA40H1S-R_0")
      (fields
        (field (name "DIGIKEY_PART_NUMBER") "490-MA40H1S-RCT-ND")
        (field (name "MF") "Murata")
        (field (name "MOUSER_PART_NUMBER") "81-MA40H1S-R")
      )
      (libsource (lib "eagle-import") (part "MURATA_MA40H1S-RMURATA_MA40H1S-R_0_0"))
    )
    (comp (ref "U257")
      (value "MURATA_MA40H1S-RMURATA_MA40H1S-R_0_0")
      (footprint "eagle-import:MURATA_MA40H1S-R_0")
      (fields
        (field (name "DIGIKEY_PART_NUMBER") "490-MA40H1S-RCT-ND")
        (field (name "MF") "Murata")
        (field (name "MOUSER_PART_NUMBER") "81-MA40H1S-R")
      )
      (libsource (lib "eagle-import") (part "MURATA_MA40H1S-RMURATA_MA40H1S-R_0_0"))
    )
    (comp (ref "U258")
      (value "MURATA_MA40H1S-RMURATA_MA40H1S-R_0_0")
      (footprint "eagle-import:MURATA_MA40H1S-R_0")
      (fields
        (field (name "DIGIKEY_PART_NUMBER") "490-MA40H1S-RCT-ND")
        (field (name "MF") "Murata")
        (field (name "MOUSER_PART_NUMBER") "81-MA40H1S-R")
      )
      (libsource (lib "eagle-import") (part "MURATA_MA40H1S-RMURATA_MA40H1S-R_0_0"))
    )
    (comp (ref "U259")
      (value "MURATA_MA40H1S-RMURATA_MA40H1S-R_0_0")
      (footprint "eagle-import:MURATA_MA40H1S-R_0")
      (fields
        (field (name "DIGIKEY_PART_NUMBER") "490-MA40H1S-RCT-ND")
        (field (name "MF") "Murata")
        (field (name "MOUSER_PART_NUMBER") "81-MA40H1S-R")
      )
      (libsource (lib "eagle-import") (part "MURATA_MA40H1S-RMURATA_MA40H1S-R_0_0"))
    )
    (comp (ref "U260")
      (value "MURATA_MA40H1S-RMURATA_MA40H1S-R_0_0")
      (footprint "eagle-import:MURATA_MA40H1S-R_0")
      (fields
        (field (name "DIGIKEY_PART_NUMBER") "490-MA40H1S-RCT-ND")
        (field (name "MF") "Murata")
        (field (name "MOUSER_PART_NUMBER") "81-MA40H1S-R")
      )
      (libsource (lib "eagle-import") (part "MURATA_MA40H1S-RMURATA_MA40H1S-R_0_0"))
    )
    (comp (ref "U261")
      (value "MURATA_MA40H1S-RMURATA_MA40H1S-R_0_0")
      (footprint "eagle-import:MURATA_MA40H1S-R_0")
      (fields
        (field (name "DIGIKEY_PART_NUMBER") "490-MA40H1S-RCT-ND")
        (field (name "MF") "Murata")
        (field (name "MOUSER_PART_NUMBER") "81-MA40H1S-R")
      )
      (libsource (lib "eagle-import") (part "MURATA_MA40H1S-RMURATA_MA40H1S-R_0_0"))
    )
    (comp (ref "U262")
      (value "MURATA_MA40H1S-RMURATA_MA40H1S-R_0_0")
      (footprint "eagle-import:MURATA_MA40H1S-R_0")
      (fields
        (field (name "DIGIKEY_PART_NUMBER") "490-MA40H1S-RCT-ND")
        (field (name "MF") "Murata")
        (field (name "MOUSER_PART_NUMBER") "81-MA40H1S-R")
      )
      (libsource (lib "eagle-import") (part "MURATA_MA40H1S-RMURATA_MA40H1S-R_0_0"))
    )
    (comp (ref "U263")
      (value "MURATA_MA40H1S-RMURATA_MA40H1S-R_0_0")
      (footprint "eagle-import:MURATA_MA40H1S-R_0")
      (fields
        (field (name "DIGIKEY_PART_NUMBER") "490-MA40H1S-RCT-ND")
        (field (name "MF") "Murata")
        (field (name "MOUSER_PART_NUMBER") "81-MA40H1S-R")
      )
      (libsource (lib "eagle-import") (part "MURATA_MA40H1S-RMURATA_MA40H1S-R_0_0"))
    )
    (comp (ref "U264")
      (value "MURATA_MA40H1S-RMURATA_MA40H1S-R_0_0")
      (footprint "eagle-import:MURATA_MA40H1S-R_0")
      (fields
        (field (name "DIGIKEY_PART_NUMBER") "490-MA40H1S-RCT-ND")
        (field (name "MF") "Murata")
        (field (name "MOUSER_PART_NUMBER") "81-MA40H1S-R")
      )
      (libsource (lib "eagle-import") (part "MURATA_MA40H1S-RMURATA_MA40H1S-R_0_0"))
    )
    (comp (ref "U265")
      (value "MURATA_MA40H1S-RMURATA_MA40H1S-R_0_0")
      (footprint "eagle-import:MURATA_MA40H1S-R_0")
      (fields
        (field (name "DIGIKEY_PART_NUMBER") "490-MA40H1S-RCT-ND")
        (field (name "MF") "Murata")
        (field (name "MOUSER_PART_NUMBER") "81-MA40H1S-R")
      )
      (libsource (lib "eagle-import") (part "MURATA_MA40H1S-RMURATA_MA40H1S-R_0_0"))
    )
    (comp (ref "U266")
      (value "MURATA_MA40H1S-RMURATA_MA40H1S-R_0_0")
      (footprint "eagle-import:MURATA_MA40H1S-R_0")
      (fields
        (field (name "DIGIKEY_PART_NUMBER") "490-MA40H1S-RCT-ND")
        (field (name "MF") "Murata")
        (field (name "MOUSER_PART_NUMBER") "81-MA40H1S-R")
      )
      (libsource (lib "eagle-import") (part "MURATA_MA40H1S-RMURATA_MA40H1S-R_0_0"))
    )
    (comp (ref "U267")
      (value "MURATA_MA40H1S-RMURATA_MA40H1S-R_0_0")
      (footprint "eagle-import:MURATA_MA40H1S-R_0")
      (fields
        (field (name "DIGIKEY_PART_NUMBER") "490-MA40H1S-RCT-ND")
        (field (name "MF") "Murata")
        (field (name "MOUSER_PART_NUMBER") "81-MA40H1S-R")
      )
      (libsource (lib "eagle-import") (part "MURATA_MA40H1S-RMURATA_MA40H1S-R_0_0"))
    )
    (comp (ref "U268")
      (value "MURATA_MA40H1S-RMURATA_MA40H1S-R_0_0")
      (footprint "eagle-import:MURATA_MA40H1S-R_0")
      (fields
        (field (name "DIGIKEY_PART_NUMBER") "490-MA40H1S-RCT-ND")
        (field (name "MF") "Murata")
        (field (name "MOUSER_PART_NUMBER") "81-MA40H1S-R")
      )
      (libsource (lib "eagle-import") (part "MURATA_MA40H1S-RMURATA_MA40H1S-R_0_0"))
    )
    (comp (ref "U269")
      (value "MURATA_MA40H1S-RMURATA_MA40H1S-R_0_0")
      (footprint "eagle-import:MURATA_MA40H1S-R_0")
      (fields
        (field (name "DIGIKEY_PART_NUMBER") "490-MA40H1S-RCT-ND")
        (field (name "MF") "Murata")
        (field (name "MOUSER_PART_NUMBER") "81-MA40H1S-R")
      )
      (libsource (lib "eagle-import") (part "MURATA_MA40H1S-RMURATA_MA40H1S-R_0_0"))
    )
    (comp (ref "U270")
      (value "MURATA_MA40H1S-RMURATA_MA40H1S-R_0_0")
      (footprint "eagle-import:MURATA_MA40H1S-R_0")
      (fields
        (field (name "DIGIKEY_PART_NUMBER") "490-MA40H1S-RCT-ND")
        (field (name "MF") "Murata")
        (field (name "MOUSER_PART_NUMBER") "81-MA40H1S-R")
      )
      (libsource (lib "eagle-import") (part "MURATA_MA40H1S-RMURATA_MA40H1S-R_0_0"))
    )
    (comp (ref "U271")
      (value "MURATA_MA40H1S-RMURATA_MA40H1S-R_0_0")
      (footprint "eagle-import:MURATA_MA40H1S-R_0")
      (fields
        (field (name "DIGIKEY_PART_NUMBER") "490-MA40H1S-RCT-ND")
        (field (name "MF") "Murata")
        (field (name "MOUSER_PART_NUMBER") "81-MA40H1S-R")
      )
      (libsource (lib "eagle-import") (part "MURATA_MA40H1S-RMURATA_MA40H1S-R_0_0"))
    )
    (comp (ref "U272")
      (value "MURATA_MA40H1S-RMURATA_MA40H1S-R_0_0")
      (footprint "eagle-import:MURATA_MA40H1S-R_0")
      (fields
        (field (name "DIGIKEY_PART_NUMBER") "490-MA40H1S-RCT-ND")
        (field (name "MF") "Murata")
        (field (name "MOUSER_PART_NUMBER") "81-MA40H1S-R")
      )
      (libsource (lib "eagle-import") (part "MURATA_MA40H1S-RMURATA_MA40H1S-R_0_0"))
    )
    (comp (ref "U273")
      (value "MURATA_MA40H1S-RMURATA_MA40H1S-R_0_0")
      (footprint "eagle-import:MURATA_MA40H1S-R_0")
      (fields
        (field (name "DIGIKEY_PART_NUMBER") "490-MA40H1S-RCT-ND")
        (field (name "MF") "Murata")
        (field (name "MOUSER_PART_NUMBER") "81-MA40H1S-R")
      )
      (libsource (lib "eagle-import") (part "MURATA_MA40H1S-RMURATA_MA40H1S-R_0_0"))
    )
    (comp (ref "U274")
      (value "MURATA_MA40H1S-RMURATA_MA40H1S-R_0_0")
      (footprint "eagle-import:MURATA_MA40H1S-R_0")
      (fields
        (field (name "DIGIKEY_PART_NUMBER") "490-MA40H1S-RCT-ND")
        (field (name "MF") "Murata")
        (field (name "MOUSER_PART_NUMBER") "81-MA40H1S-R")
      )
      (libsource (lib "eagle-import") (part "MURATA_MA40H1S-RMURATA_MA40H1S-R_0_0"))
    )
    (comp (ref "U275")
      (value "MURATA_MA40H1S-RMURATA_MA40H1S-R_0_0")
      (footprint "eagle-import:MURATA_MA40H1S-R_0")
      (fields
        (field (name "DIGIKEY_PART_NUMBER") "490-MA40H1S-RCT-ND")
        (field (name "MF") "Murata")
        (field (name "MOUSER_PART_NUMBER") "81-MA40H1S-R")
      )
      (libsource (lib "eagle-import") (part "MURATA_MA40H1S-RMURATA_MA40H1S-R_0_0"))
    )
  )
  (nets
    (net (code "1") (name "GND") (class "Default")
      (node (ref "U1") (pin "3") (pinfunction "2_SIGNAL_TERMINAL_3") (pintype "passive"))
      (node (ref "U10") (pin "3") (pinfunction "2_SIGNAL_TERMINAL_3") (pintype "passive"))
      (node (ref "U100") (pin "3") (pinfunction "2_SIGNAL_TERMINAL_3") (pintype "passive"))
      (node (ref "U101") (pin "3") (pinfunction "2_SIGNAL_TERMINAL_3") (pintype "passive"))
      (node (ref "U102") (pin "3") (pinfunction "2_SIGNAL_TERMINAL_3") (pintype "passive"))
      (node (ref "U103") (pin "3") (pinfunction "2_SIGNAL_TERMINAL_3") (pintype "passive"))
      (node (ref "U104") (pin "3") (pinfunction "2_SIGNAL_TERMINAL_3") (pintype "passive"))
      (node (ref "U105") (pin "3") (pinfunction "2_SIGNAL_TERMINAL_3") (pintype "passive"))
      (node (ref "U106") (pin "3") (pinfunction "2_SIGNAL_TERMINAL_3") (pintype "passive"))
      (node (ref "U107") (pin "3") (pinfunction "2_SIGNAL_TERMINAL_3") (pintype "passive"))
      (node (ref "U108") (pin "3") (pinfunction "2_SIGNAL_TERMINAL_3") (pintype "passive"))
      (node (ref "U109") (pin "3") (pinfunction "2_SIGNAL_TERMINAL_3") (pintype "passive"))
      (node (ref "U110") (pin "3") (pinfunction "2_SIGNAL_TERMINAL_3") (pintype "passive"))
      (node (ref "U111") (pin "3") (pinfunction "2_SIGNAL_TERMINAL_3") (pintype "passive"))
      (node (ref "U112") (pin "3") (pinfunction "2_SIGNAL_TERMINAL_3") (pintype "passive"))
      (node (ref "U113") (pin "3") (pinfunction "2_SIGNAL_TERMINAL_3") (pintype "passive"))
      (node (ref "U114") (pin "3") (pinfunction "2_SIGNAL_TERMINAL_3") (pintype "passive"))
      (node (ref "U115") (pin "3") (pinfunction "2_SIGNAL_TERMINAL_3") (pintype "passive"))
      (node (ref "U116") (pin "3") (pinfunction "2_SIGNAL_TERMINAL_3") (pintype "passive"))
      (node (ref "U117") (pin "3") (pinfunction "2_SIGNAL_TERMINAL_3") (pintype "passive"))
      (node (ref "U118") (pin "3") (pinfunction "2_SIGNAL_TERMINAL_3") (pintype "passive"))
      (node (ref "U119") (pin "3") (pinfunction "2_SIGNAL_TERMINAL_3") (pintype "passive"))
      (node (ref "U12") (pin "3") (pinfunction "2_SIGNAL_TERMINAL_3") (pintype "passive"))
      (node (ref "U120") (pin "3") (pinfunction "2_SIGNAL_TERMINAL_3") (pintype "passive"))
      (node (ref "U121") (pin "3") (pinfunction "2_SIGNAL_TERMINAL_3") (pintype "passive"))
      (node (ref "U122") (pin "3") (pinfunction "2_SIGNAL_TERMINAL_3") (pintype "passive"))
      (node (ref "U123") (pin "3") (pinfunction "2_SIGNAL_TERMINAL_3") (pintype "passive"))
      (node (ref "U124") (pin "3") (pinfunction "2_SIGNAL_TERMINAL_3") (pintype "passive"))
      (node (ref "U125") (pin "3") (pinfunction "2_SIGNAL_TERMINAL_3") (pintype "passive"))
      (node (ref "U126") (pin "3") (pinfunction "2_SIGNAL_TERMINAL_3") (pintype "passive"))
      (node (ref "U127") (pin "3") (pinfunction "2_SIGNAL_TERMINAL_3") (pintype "passive"))
      (node (ref "U128") (pin "3") (pinfunction "2_SIGNAL_TERMINAL_3") (pintype "passive"))
      (node (ref "U129") (pin "3") (pinfunction "2_SIGNAL_TERMINAL_3") (pintype "passive"))
      (node (ref "U13") (pin "3") (pinfunction "2_SIGNAL_TERMINAL_3") (pintype "passive"))
      (node (ref "U130") (pin "3") (pinfunction "2_SIGNAL_TERMINAL_3") (pintype "passive"))
      (node (ref "U131") (pin "3") (pinfunction "2_SIGNAL_TERMINAL_3") (pintype "passive"))
      (node (ref "U132") (pin "3") (pinfunction "2_SIGNAL_TERMINAL_3") (pintype "passive"))
      (node (ref "U133") (pin "3") (pinfunction "2_SIGNAL_TERMINAL_3") (pintype "passive"))
      (node (ref "U134") (pin "3") (pinfunction "2_SIGNAL_TERMINAL_3") (pintype "passive"))
      (node (ref "U135") (pin "3") (pinfunction "2_SIGNAL_TERMINAL_3") (pintype "passive"))
      (node (ref "U136") (pin "3") (pinfunction "2_SIGNAL_TERMINAL_3") (pintype "passive"))
      (node (ref "U137") (pin "3") (pinfunction "2_SIGNAL_TERMINAL_3") (pintype "passive"))
      (node (ref "U138") (pin "3") (pinfunction "2_SIGNAL_TERMINAL_3") (pintype "passive"))
      (node (ref "U139") (pin "3") (pinfunction "2_SIGNAL_TERMINAL_3") (pintype "passive"))
      (node (ref "U14") (pin "3") (pinfunction "2_SIGNAL_TERMINAL_3") (pintype "passive"))
      (node (ref "U140") (pin "3") (pinfunction "2_SIGNAL_TERMINAL_3") (pintype "passive"))
      (node (ref "U141") (pin "3") (pinfunction "2_SIGNAL_TERMINAL_3") (pintype "passive"))
      (node (ref "U142") (pin "3") (pinfunction "2_SIGNAL_TERMINAL_3") (pintype "passive"))
      (node (ref "U143") (pin "3") (pinfunction "2_SIGNAL_TERMINAL_3") (pintype "passive"))
      (node (ref "U144") (pin "3") (pinfunction "2_SIGNAL_TERMINAL_3") (pintype "passive"))
      (node (ref "U145") (pin "3") (pinfunction "2_SIGNAL_TERMINAL_3") (pintype "passive"))
      (node (ref "U146") (pin "3") (pinfunction "2_SIGNAL_TERMINAL_3") (pintype "passive"))
      (node (ref "U147") (pin "3") (pinfunction "2_SIGNAL_TERMINAL_3") (pintype "passive"))
      (node (ref "U148") (pin "3") (pinfunction "2_SIGNAL_TERMINAL_3") (pintype "passive"))
      (node (ref "U149") (pin "3") (pinfunction "2_SIGNAL_TERMINAL_3") (pintype "passive"))
      (node (ref "U15") (pin "3") (pinfunction "2_SIGNAL_TERMINAL_3") (pintype "passive"))
      (node (ref "U150") (pin "3") (pinfunction "2_SIGNAL_TERMINAL_3") (pintype "passive"))
      (node (ref "U151") (pin "3") (pinfunction "2_SIGNAL_TERMINAL_3") (pintype "passive"))
      (node (ref "U152") (pin "3") (pinfunction "2_SIGNAL_TERMINAL_3") (pintype "passive"))
      (node (ref "U153") (pin "3") (pinfunction "2_SIGNAL_TERMINAL_3") (pintype "passive"))
      (node (ref "U154") (pin "3") (pinfunction "2_SIGNAL_TERMINAL_3") (pintype "passive"))
      (node (ref "U155") (pin "3") (pinfunction "2_SIGNAL_TERMINAL_3") (pintype "passive"))
      (node (ref "U156") (pin "3") (pinfunction "2_SIGNAL_TERMINAL_3") (pintype "passive"))
      (node (ref "U157") (pin "3") (pinfunction "2_SIGNAL_TERMINAL_3") (pintype "passive"))
      (node (ref "U158") (pin "3") (pinfunction "2_SIGNAL_TERMINAL_3") (pintype "passive"))
      (node (ref "U159") (pin "3") (pinfunction "2_SIGNAL_TERMINAL_3") (pintype "passive"))
      (node (ref "U16") (pin "3") (pinfunction "2_SIGNAL_TERMINAL_3") (pintype "passive"))
      (node (ref "U160") (pin "3") (pinfunction "2_SIGNAL_TERMINAL_3") (pintype "passive"))
      (node (ref "U161") (pin "3") (pinfunction "2_SIGNAL_TERMINAL_3") (pintype "passive"))
      (node (ref "U162") (pin "3") (pinfunction "2_SIGNAL_TERMINAL_3") (pintype "passive"))
      (node (ref "U163") (pin "3") (pinfunction "2_SIGNAL_TERMINAL_3") (pintype "passive"))
      (node (ref "U164") (pin "3") (pinfunction "2_SIGNAL_TERMINAL_3") (pintype "passive"))
      (node (ref "U165") (pin "3") (pinfunction "2_SIGNAL_TERMINAL_3") (pintype "passive"))
      (node (ref "U166") (pin "3") (pinfunction "2_SIGNAL_TERMINAL_3") (pintype "passive"))
      (node (ref "U167") (pin "3") (pinfunction "2_SIGNAL_TERMINAL_3") (pintype "passive"))
      (node (ref "U168") (pin "3") (pinfunction "2_SIGNAL_TERMINAL_3") (pintype "passive"))
      (node (ref "U169") (pin "3") (pinfunction "2_SIGNAL_TERMINAL_3") (pintype "passive"))
      (node (ref "U170") (pin "3") (pinfunction "2_SIGNAL_TERMINAL_3") (pintype "passive"))
      (node (ref "U171") (pin "3") (pinfunction "2_SIGNAL_TERMINAL_3") (pintype "passive"))
      (node (ref "U172") (pin "3") (pinfunction "2_SIGNAL_TERMINAL_3") (pintype "passive"))
      (node (ref "U173") (pin "3") (pinfunction "2_SIGNAL_TERMINAL_3") (pintype "passive"))
      (node (ref "U174") (pin "3") (pinfunction "2_SIGNAL_TERMINAL_3") (pintype "passive"))
      (node (ref "U175") (pin "3") (pinfunction "2_SIGNAL_TERMINAL_3") (pintype "passive"))
      (node (ref "U176") (pin "3") (pinfunction "2_SIGNAL_TERMINAL_3") (pintype "passive"))
      (node (ref "U177") (pin "3") (pinfunction "2_SIGNAL_TERMINAL_3") (pintype "passive"))
      (node (ref "U178") (pin "3") (pinfunction "2_SIGNAL_TERMINAL_3") (pintype "passive"))
      (node (ref "U179") (pin "3") (pinfunction "2_SIGNAL_TERMINAL_3") (pintype "passive"))
      (node (ref "U180") (pin "3") (pinfunction "2_SIGNAL_TERMINAL_3") (pintype "passive"))
      (node (ref "U184") (pin "3") (pinfunction "2_SIGNAL_TERMINAL_3") (pintype "passive"))
      (node (ref "U185") (pin "3") (pinfunction "2_SIGNAL_TERMINAL_3") (pintype "passive"))
      (node (ref "U186") (pin "3") (pinfunction "2_SIGNAL_TERMINAL_3") (pintype "passive"))
      (node (ref "U192") (pin "3") (pinfunction "2_SIGNAL_TERMINAL_3") (pintype "passive"))
      (node (ref "U193") (pin "3") (pinfunction "2_SIGNAL_TERMINAL_3") (pintype "passive"))
      (node (ref "U194") (pin "3") (pinfunction "2_SIGNAL_TERMINAL_3") (pintype "passive"))
      (node (ref "U195") (pin "3") (pinfunction "2_SIGNAL_TERMINAL_3") (pintype "passive"))
      (node (ref "U196") (pin "3") (pinfunction "2_SIGNAL_TERMINAL_3") (pintype "passive"))
      (node (ref "U197") (pin "3") (pinfunction "2_SIGNAL_TERMINAL_3") (pintype "passive"))
      (node (ref "U198") (pin "3") (pinfunction "2_SIGNAL_TERMINAL_3") (pintype "passive"))
      (node (ref "U199") (pin "3") (pinfunction "2_SIGNAL_TERMINAL_3") (pintype "passive"))
      (node (ref "U2") (pin "3") (pinfunction "2_SIGNAL_TERMINAL_3") (pintype "passive"))
      (node (ref "U200") (pin "3") (pinfunction "2_SIGNAL_TERMINAL_3") (pintype "passive"))
      (node (ref "U201") (pin "3") (pinfunction "2_SIGNAL_TERMINAL_3") (pintype "passive"))
      (node (ref "U202") (pin "3") (pinfunction "2_SIGNAL_TERMINAL_3") (pintype "passive"))
      (node (ref "U203") (pin "3") (pinfunction "2_SIGNAL_TERMINAL_3") (pintype "passive"))
      (node (ref "U204") (pin "3") (pinfunction "2_SIGNAL_TERMINAL_3") (pintype "passive"))
      (node (ref "U205") (pin "3") (pinfunction "2_SIGNAL_TERMINAL_3") (pintype "passive"))
      (node (ref "U206") (pin "3") (pinfunction "2_SIGNAL_TERMINAL_3") (pintype "passive"))
      (node (ref "U207") (pin "3") (pinfunction "2_SIGNAL_TERMINAL_3") (pintype "passive"))
      (node (ref "U208") (pin "3") (pinfunction "2_SIGNAL_TERMINAL_3") (pintype "passive"))
      (node (ref "U209") (pin "3") (pinfunction "2_SIGNAL_TERMINAL_3") (pintype "passive"))
      (node (ref "U21") (pin "3") (pinfunction "2_SIGNAL_TERMINAL_3") (pintype "passive"))
      (node (ref "U210") (pin "3") (pinfunction "2_SIGNAL_TERMINAL_3") (pintype "passive"))
      (node (ref "U211") (pin "3") (pinfunction "2_SIGNAL_TERMINAL_3") (pintype "passive"))
      (node (ref "U212") (pin "3") (pinfunction "2_SIGNAL_TERMINAL_3") (pintype "passive"))
      (node (ref "U213") (pin "3") (pinfunction "2_SIGNAL_TERMINAL_3") (pintype "passive"))
      (node (ref "U214") (pin "3") (pinfunction "2_SIGNAL_TERMINAL_3") (pintype "passive"))
      (node (ref "U215") (pin "3") (pinfunction "2_SIGNAL_TERMINAL_3") (pintype "passive"))
      (node (ref "U216") (pin "3") (pinfunction "2_SIGNAL_TERMINAL_3") (pintype "passive"))
      (node (ref "U217") (pin "3") (pinfunction "2_SIGNAL_TERMINAL_3") (pintype "passive"))
      (node (ref "U218") (pin "3") (pinfunction "2_SIGNAL_TERMINAL_3") (pintype "passive"))
      (node (ref "U219") (pin "3") (pinfunction "2_SIGNAL_TERMINAL_3") (pintype "passive"))
      (node (ref "U22") (pin "3") (pinfunction "2_SIGNAL_TERMINAL_3") (pintype "passive"))
      (node (ref "U220") (pin "3") (pinfunction "2_SIGNAL_TERMINAL_3") (pintype "passive"))
      (node (ref "U221") (pin "3") (pinfunction "2_SIGNAL_TERMINAL_3") (pintype "passive"))
      (node (ref "U222") (pin "3") (pinfunction "2_SIGNAL_TERMINAL_3") (pintype "passive"))
      (node (ref "U223") (pin "3") (pinfunction "2_SIGNAL_TERMINAL_3") (pintype "passive"))
      (node (ref "U224") (pin "3") (pinfunction "2_SIGNAL_TERMINAL_3") (pintype "passive"))
      (node (ref "U225") (pin "3") (pinfunction "2_SIGNAL_TERMINAL_3") (pintype "passive"))
      (node (ref "U226") (pin "3") (pinfunction "2_SIGNAL_TERMINAL_3") (pintype "passive"))
      (node (ref "U227") (pin "3") (pinfunction "2_SIGNAL_TERMINAL_3") (pintype "passive"))
      (node (ref "U228") (pin "3") (pinfunction "2_SIGNAL_TERMINAL_3") (pintype "passive"))
      (node (ref "U229") (pin "3") (pinfunction "2_SIGNAL_TERMINAL_3") (pintype "passive"))
      (node (ref "U23") (pin "3") (pinfunction "2_SIGNAL_TERMINAL_3") (pintype "passive"))
      (node (ref "U230") (pin "3") (pinfunction "2_SIGNAL_TERMINAL_3") (pintype "passive"))
      (node (ref "U231") (pin "3") (pinfunction "2_SIGNAL_TERMINAL_3") (pintype "passive"))
      (node (ref "U232") (pin "3") (pinfunction "2_SIGNAL_TERMINAL_3") (pintype "passive"))
      (node (ref "U233") (pin "3") (pinfunction "2_SIGNAL_TERMINAL_3") (pintype "passive"))
      (node (ref "U234") (pin "3") (pinfunction "2_SIGNAL_TERMINAL_3") (pintype "passive"))
      (node (ref "U235") (pin "3") (pinfunction "2_SIGNAL_TERMINAL_3") (pintype "passive"))
      (node (ref "U236") (pin "3") (pinfunction "2_SIGNAL_TERMINAL_3") (pintype "passive"))
      (node (ref "U237") (pin "3") (pinfunction "2_SIGNAL_TERMINAL_3") (pintype "passive"))
      (node (ref "U238") (pin "3") (pinfunction "2_SIGNAL_TERMINAL_3") (pintype "passive"))
      (node (ref "U239") (pin "3") (pinfunction "2_SIGNAL_TERMINAL_3") (pintype "passive"))
      (node (ref "U24") (pin "3") (pinfunction "2_SIGNAL_TERMINAL_3") (pintype "passive"))
      (node (ref "U240") (pin "3") (pinfunction "2_SIGNAL_TERMINAL_3") (pintype "passive"))
      (node (ref "U241") (pin "3") (pinfunction "2_SIGNAL_TERMINAL_3") (pintype "passive"))
      (node (ref "U242") (pin "3") (pinfunction "2_SIGNAL_TERMINAL_3") (pintype "passive"))
      (node (ref "U246") (pin "3") (pinfunction "2_SIGNAL_TERMINAL_3") (pintype "passive"))
      (node (ref "U247") (pin "3") (pinfunction "2_SIGNAL_TERMINAL_3") (pintype "passive"))
      (node (ref "U248") (pin "3") (pinfunction "2_SIGNAL_TERMINAL_3") (pintype "passive"))
      (node (ref "U249") (pin "3") (pinfunction "2_SIGNAL_TERMINAL_3") (pintype "passive"))
      (node (ref "U25") (pin "3") (pinfunction "2_SIGNAL_TERMINAL_3") (pintype "passive"))
      (node (ref "U250") (pin "3") (pinfunction "2_SIGNAL_TERMINAL_3") (pintype "passive"))
      (node (ref "U251") (pin "3") (pinfunction "2_SIGNAL_TERMINAL_3") (pintype "passive"))
      (node (ref "U252") (pin "3") (pinfunction "2_SIGNAL_TERMINAL_3") (pintype "passive"))
      (node (ref "U253") (pin "3") (pinfunction "2_SIGNAL_TERMINAL_3") (pintype "passive"))
      (node (ref "U254") (pin "3") (pinfunction "2_SIGNAL_TERMINAL_3") (pintype "passive"))
      (node (ref "U255") (pin "3") (pinfunction "2_SIGNAL_TERMINAL_3") (pintype "passive"))
      (node (ref "U256") (pin "3") (pinfunction "2_SIGNAL_TERMINAL_3") (pintype "passive"))
      (node (ref "U257") (pin "3") (pinfunction "2_SIGNAL_TERMINAL_3") (pintype "passive"))
      (node (ref "U258") (pin "3") (pinfunction "2_SIGNAL_TERMINAL_3") (pintype "passive"))
      (node (ref "U259") (pin "3") (pinfunction "2_SIGNAL_TERMINAL_3") (pintype "passive"))
      (node (ref "U26") (pin "3") (pinfunction "2_SIGNAL_TERMINAL_3") (pintype "passive"))
      (node (ref "U260") (pin "3") (pinfunction "2_SIGNAL_TERMINAL_3") (pintype "passive"))
      (node (ref "U261") (pin "3") (pinfunction "2_SIGNAL_TERMINAL_3") (pintype "passive"))
      (node (ref "U262") (pin "3") (pinfunction "2_SIGNAL_TERMINAL_3") (pintype "passive"))
      (node (ref "U263") (pin "3") (pinfunction "2_SIGNAL_TERMINAL_3") (pintype "passive"))
      (node (ref "U264") (pin "3") (pinfunction "2_SIGNAL_TERMINAL_3") (pintype "passive"))
      (node (ref "U265") (pin "3") (pinfunction "2_SIGNAL_TERMINAL_3") (pintype "passive"))
      (node (ref "U266") (pin "3") (pinfunction "2_SIGNAL_TERMINAL_3") (pintype "passive"))
      (node (ref "U267") (pin "3") (pinfunction "2_SIGNAL_TERMINAL_3") (pintype "passive"))
      (node (ref "U268") (pin "3") (pinfunction "2_SIGNAL_TERMINAL_3") (pintype "passive"))
      (node (ref "U269") (pin "3") (pinfunction "2_SIGNAL_TERMINAL_3") (pintype "passive"))
      (node (ref "U27") (pin "3") (pinfunction "2_SIGNAL_TERMINAL_3") (pintype "passive"))
      (node (ref "U270") (pin "3") (pinfunction "2_SIGNAL_TERMINAL_3") (pintype "passive"))
      (node (ref "U271") (pin "3") (pinfunction "2_SIGNAL_TERMINAL_3") (pintype "passive"))
      (node (ref "U272") (pin "3") (pinfunction "2_SIGNAL_TERMINAL_3") (pintype "passive"))
      (node (ref "U273") (pin "3") (pinfunction "2_SIGNAL_TERMINAL_3") (pintype "passive"))
      (node (ref "U274") (pin "3") (pinfunction "2_SIGNAL_TERMINAL_3") (pintype "passive"))
      (node (ref "U275") (pin "3") (pinfunction "2_SIGNAL_TERMINAL_3") (pintype "passive"))
      (node (ref "U28") (pin "3") (pinfunction "2_SIGNAL_TERMINAL_3") (pintype "passive"))
      (node (ref "U29") (pin "3") (pinfunction "2_SIGNAL_TERMINAL_3") (pintype "passive"))
      (node (ref "U3") (pin "3") (pinfunction "2_SIGNAL_TERMINAL_3") (pintype "passive"))
      (node (ref "U30") (pin "3") (pinfunction "2_SIGNAL_TERMINAL_3") (pintype "passive"))
      (node (ref "U31") (pin "3") (pinfunction "2_SIGNAL_TERMINAL_3") (pintype "passive"))
      (node (ref "U32") (pin "3") (pinfunction "2_SIGNAL_TERMINAL_3") (pintype "passive"))
      (node (ref "U33") (pin "3") (pinfunction "2_SIGNAL_TERMINAL_3") (pintype "passive"))
      (node (ref "U34") (pin "3") (pinfunction "2_SIGNAL_TERMINAL_3") (pintype "passive"))
      (node (ref "U35") (pin "3") (pinfunction "2_SIGNAL_TERMINAL_3") (pintype "passive"))
      (node (ref "U36") (pin "3") (pinfunction "2_SIGNAL_TERMINAL_3") (pintype "passive"))
      (node (ref "U37") (pin "3") (pinfunction "2_SIGNAL_TERMINAL_3") (pintype "passive"))
      (node (ref "U38") (pin "3") (pinfunction "2_SIGNAL_TERMINAL_3") (pintype "passive"))
      (node (ref "U39") (pin "3") (pinfunction "2_SIGNAL_TERMINAL_3") (pintype "passive"))
      (node (ref "U4") (pin "3") (pinfunction "2_SIGNAL_TERMINAL_3") (pintype "passive"))
      (node (ref "U40") (pin "3") (pinfunction "2_SIGNAL_TERMINAL_3") (pintype "passive"))
      (node (ref "U41") (pin "3") (pinfunction "2_SIGNAL_TERMINAL_3") (pintype "passive"))
      (node (ref "U42") (pin "3") (pinfunction "2_SIGNAL_TERMINAL_3") (pintype "passive"))
      (node (ref "U43") (pin "3") (pinfunction "2_SIGNAL_TERMINAL_3") (pintype "passive"))
      (node (ref "U44") (pin "3") (pinfunction "2_SIGNAL_TERMINAL_3") (pintype "passive"))
      (node (ref "U45") (pin "3") (pinfunction "2_SIGNAL_TERMINAL_3") (pintype "passive"))
      (node (ref "U46") (pin "3") (pinfunction "2_SIGNAL_TERMINAL_3") (pintype "passive"))
      (node (ref "U47") (pin "3") (pinfunction "2_SIGNAL_TERMINAL_3") (pintype "passive"))
      (node (ref "U48") (pin "3") (pinfunction "2_SIGNAL_TERMINAL_3") (pintype "passive"))
      (node (ref "U49") (pin "3") (pinfunction "2_SIGNAL_TERMINAL_3") (pintype "passive"))
      (node (ref "U50") (pin "3") (pinfunction "2_SIGNAL_TERMINAL_3") (pintype "passive"))
      (node (ref "U51") (pin "3") (pinfunction "2_SIGNAL_TERMINAL_3") (pintype "passive"))
      (node (ref "U52") (pin "3") (pinfunction "2_SIGNAL_TERMINAL_3") (pintype "passive"))
      (node (ref "U53") (pin "3") (pinfunction "2_SIGNAL_TERMINAL_3") (pintype "passive"))
      (node (ref "U54") (pin "3") (pinfunction "2_SIGNAL_TERMINAL_3") (pintype "passive"))
      (node (ref "U55") (pin "3") (pinfunction "2_SIGNAL_TERMINAL_3") (pintype "passive"))
      (node (ref "U56") (pin "3") (pinfunction "2_SIGNAL_TERMINAL_3") (pintype "passive"))
      (node (ref "U57") (pin "3") (pinfunction "2_SIGNAL_TERMINAL_3") (pintype "passive"))
      (node (ref "U58") (pin "3") (pinfunction "2_SIGNAL_TERMINAL_3") (pintype "passive"))
      (node (ref "U59") (pin "3") (pinfunction "2_SIGNAL_TERMINAL_3") (pintype "passive"))
      (node (ref "U6") (pin "3") (pinfunction "2_SIGNAL_TERMINAL_3") (pintype "passive"))
      (node (ref "U60") (pin "3") (pinfunction "2_SIGNAL_TERMINAL_3") (pintype "passive"))
      (node (ref "U61") (pin "3") (pinfunction "2_SIGNAL_TERMINAL_3") (pintype "passive"))
      (node (ref "U62") (pin "3") (pinfunction "2_SIGNAL_TERMINAL_3") (pintype "passive"))
      (node (ref "U63") (pin "3") (pinfunction "2_SIGNAL_TERMINAL_3") (pintype "passive"))
      (node (ref "U64") (pin "3") (pinfunction "2_SIGNAL_TERMINAL_3") (pintype "passive"))
      (node (ref "U65") (pin "3") (pinfunction "2_SIGNAL_TERMINAL_3") (pintype "passive"))
      (node (ref "U66") (pin "3") (pinfunction "2_SIGNAL_TERMINAL_3") (pintype "passive"))
      (node (ref "U67") (pin "3") (pinfunction "2_SIGNAL_TERMINAL_3") (pintype "passive"))
      (node (ref "U68") (pin "3") (pinfunction "2_SIGNAL_TERMINAL_3") (pintype "passive"))
      (node (ref "U69") (pin "3") (pinfunction "2_SIGNAL_TERMINAL_3") (pintype "passive"))
      (node (ref "U70") (pin "3") (pinfunction "2_SIGNAL_TERMINAL_3") (pintype "passive"))
      (node (ref "U71") (pin "3") (pinfunction "2_SIGNAL_TERMINAL_3") (pintype "passive"))
      (node (ref "U72") (pin "3") (pinfunction "2_SIGNAL_TERMINAL_3") (pintype "passive"))
      (node (ref "U73") (pin "3") (pinfunction "2_SIGNAL_TERMINAL_3") (pintype "passive"))
      (node (ref "U74") (pin "3") (pinfunction "2_SIGNAL_TERMINAL_3") (pintype "passive"))
      (node (ref "U75") (pin "3") (pinfunction "2_SIGNAL_TERMINAL_3") (pintype "passive"))
      (node (ref "U76") (pin "3") (pinfunction "2_SIGNAL_TERMINAL_3") (pintype "passive"))
      (node (ref "U77") (pin "3") (pinfunction "2_SIGNAL_TERMINAL_3") (pintype "passive"))
      (node (ref "U78") (pin "3") (pinfunction "2_SIGNAL_TERMINAL_3") (pintype "passive"))
      (node (ref "U79") (pin "3") (pinfunction "2_SIGNAL_TERMINAL_3") (pintype "passive"))
      (node (ref "U80") (pin "3") (pinfunction "2_SIGNAL_TERMINAL_3") (pintype "passive"))
      (node (ref "U9") (pin "3") (pinfunction "2_SIGNAL_TERMINAL_3") (pintype "passive"))
      (node (ref "U90") (pin "3") (pinfunction "2_SIGNAL_TERMINAL_3") (pintype "passive"))
      (node (ref "U91") (pin "3") (pinfunction "2_SIGNAL_TERMINAL_3") (pintype "passive"))
      (node (ref "U92") (pin "3") (pinfunction "2_SIGNAL_TERMINAL_3") (pintype "passive"))
      (node (ref "U93") (pin "3") (pinfunction "2_SIGNAL_TERMINAL_3") (pintype "passive"))
      (node (ref "U94") (pin "3") (pinfunction "2_SIGNAL_TERMINAL_3") (pintype "passive"))
      (node (ref "U95") (pin "3") (pinfunction "2_SIGNAL_TERMINAL_3") (pintype "passive"))
      (node (ref "U96") (pin "3") (pinfunction "2_SIGNAL_TERMINAL_3") (pintype "passive"))
      (node (ref "U97") (pin "3") (pinfunction "2_SIGNAL_TERMINAL_3") (pintype "passive"))
      (node (ref "U98") (pin "3") (pinfunction "2_SIGNAL_TERMINAL_3") (pintype "passive"))
      (node (ref "U99") (pin "3") (pinfunction "2_SIGNAL_TERMINAL_3") (pintype "passive"))
    )
    (net (code "2") (name "Net-(U1-1_SIGNAL_TERMINAL)") (class "Default")
      (node (ref "J7") (pin "2") (pinfunction "2_2") (pintype "passive"))
      (node (ref "U1") (pin "1") (pinfunction "1_SIGNAL_TERMINAL_1") (pintype "passive"))
      (node (ref "U2") (pin "1") (pinfunction "1_SIGNAL_TERMINAL_1") (pintype "passive"))
      (node (ref "U3") (pin "1") (pinfunction "1_SIGNAL_TERMINAL_1") (pintype "passive"))
      (node (ref "U4") (pin "1") (pinfunction "1_SIGNAL_TERMINAL_1") (pintype "passive"))
    )
    (net (code "3") (name "Net-(U10-1_SIGNAL_TERMINAL)") (class "Default")
      (node (ref "J5") (pin "14") (pinfunction "14_14") (pintype "passive"))
      (node (ref "U10") (pin "1") (pinfunction "1_SIGNAL_TERMINAL_1") (pintype "passive"))
      (node (ref "U6") (pin "1") (pinfunction "1_SIGNAL_TERMINAL_1") (pintype "passive"))
      (node (ref "U9") (pin "1") (pinfunction "1_SIGNAL_TERMINAL_1") (pintype "passive"))
    )
    (net (code "4") (name "Net-(U11-1_SIGNAL_TERMINAL)") (class "Default")
      (node (ref "J6") (pin "10") (pinfunction "10_10") (pintype "passive"))
      (node (ref "U11") (pin "1") (pinfunction "1_SIGNAL_TERMINAL_1") (pintype "passive"))
      (node (ref "U12") (pin "1") (pinfunction "1_SIGNAL_TERMINAL_1") (pintype "passive"))
      (node (ref "U13") (pin "1") (pinfunction "1_SIGNAL_TERMINAL_1") (pintype "passive"))
    )
    (net (code "5") (name "Net-(U14-1_SIGNAL_TERMINAL)") (class "Default")
      (node (ref "J6") (pin "2") (pinfunction "2_2") (pintype "passive"))
      (node (ref "U14") (pin "1") (pinfunction "1_SIGNAL_TERMINAL_1") (pintype "passive"))
      (node (ref "U15") (pin "1") (pinfunction "1_SIGNAL_TERMINAL_1") (pintype "passive"))
      (node (ref "U16") (pin "1") (pinfunction "1_SIGNAL_TERMINAL_1") (pintype "passive"))
    )
    (net (code "6") (name "Net-(U21-1_SIGNAL_TERMINAL)") (class "Default")
      (node (ref "J7") (pin "4") (pinfunction "4_4") (pintype "passive"))
      (node (ref "U21") (pin "1") (pinfunction "1_SIGNAL_TERMINAL_1") (pintype "passive"))
      (node (ref "U22") (pin "1") (pinfunction "1_SIGNAL_TERMINAL_1") (pintype "passive"))
      (node (ref "U23") (pin "1") (pinfunction "1_SIGNAL_TERMINAL_1") (pintype "passive"))
      (node (ref "U24") (pin "1") (pinfunction "1_SIGNAL_TERMINAL_1") (pintype "passive"))
    )
    (net (code "7") (name "Net-(U25-1_SIGNAL_TERMINAL)") (class "Default")
      (node (ref "J4") (pin "12") (pinfunction "12_12") (pintype "passive"))
      (node (ref "U25") (pin "1") (pinfunction "1_SIGNAL_TERMINAL_1") (pintype "passive"))
      (node (ref "U26") (pin "1") (pinfunction "1_SIGNAL_TERMINAL_1") (pintype "passive"))
      (node (ref "U27") (pin "1") (pinfunction "1_SIGNAL_TERMINAL_1") (pintype "passive"))
      (node (ref "U28") (pin "1") (pinfunction "1_SIGNAL_TERMINAL_1") (pintype "passive"))
    )
    (net (code "8") (name "Net-(U29-1_SIGNAL_TERMINAL)") (class "Default")
      (node (ref "J4") (pin "16") (pinfunction "16_16") (pintype "passive"))
      (node (ref "U29") (pin "1") (pinfunction "1_SIGNAL_TERMINAL_1") (pintype "passive"))
      (node (ref "U30") (pin "1") (pinfunction "1_SIGNAL_TERMINAL_1") (pintype "passive"))
      (node (ref "U31") (pin "1") (pinfunction "1_SIGNAL_TERMINAL_1") (pintype "passive"))
      (node (ref "U32") (pin "1") (pinfunction "1_SIGNAL_TERMINAL_1") (pintype "passive"))
    )
    (net (code "9") (name "Net-(U33-1_SIGNAL_TERMINAL)") (class "Default")
      (node (ref "J4") (pin "2") (pinfunction "2_2") (pintype "passive"))
      (node (ref "U33") (pin "1") (pinfunction "1_SIGNAL_TERMINAL_1") (pintype "passive"))
      (node (ref "U34") (pin "1") (pinfunction "1_SIGNAL_TERMINAL_1") (pintype "passive"))
      (node (ref "U35") (pin "1") (pinfunction "1_SIGNAL_TERMINAL_1") (pintype "passive"))
      (node (ref "U36") (pin "1") (pinfunction "1_SIGNAL_TERMINAL_1") (pintype "passive"))
    )
    (net (code "10") (name "Net-(U37-1_SIGNAL_TERMINAL)") (class "Default")
      (node (ref "J4") (pin "4") (pinfunction "4_4") (pintype "passive"))
      (node (ref "U37") (pin "1") (pinfunction "1_SIGNAL_TERMINAL_1") (pintype "passive"))
      (node (ref "U38") (pin "1") (pinfunction "1_SIGNAL_TERMINAL_1") (pintype "passive"))
      (node (ref "U39") (pin "1") (pinfunction "1_SIGNAL_TERMINAL_1") (pintype "passive"))
      (node (ref "U40") (pin "1") (pinfunction "1_SIGNAL_TERMINAL_1") (pintype "passive"))
    )
    (net (code "11") (name "Net-(U41-1_SIGNAL_TERMINAL)") (class "Default")
      (node (ref "J4") (pin "10") (pinfunction "10_10") (pintype "passive"))
      (node (ref "U41") (pin "1") (pinfunction "1_SIGNAL_TERMINAL_1") (pintype "passive"))
      (node (ref "U42") (pin "1") (pinfunction "1_SIGNAL_TERMINAL_1") (pintype "passive"))
      (node (ref "U43") (pin "1") (pinfunction "1_SIGNAL_TERMINAL_1") (pintype "passive"))
      (node (ref "U44") (pin "1") (pinfunction "1_SIGNAL_TERMINAL_1") (pintype "passive"))
    )
    (net (code "12") (name "Net-(U45-1_SIGNAL_TERMINAL)") (class "Default")
      (node (ref "J4") (pin "14") (pinfunction "14_14") (pintype "passive"))
      (node (ref "U45") (pin "1") (pinfunction "1_SIGNAL_TERMINAL_1") (pintype "passive"))
      (node (ref "U46") (pin "1") (pinfunction "1_SIGNAL_TERMINAL_1") (pintype "passive"))
      (node (ref "U47") (pin "1") (pinfunction "1_SIGNAL_TERMINAL_1") (pintype "passive"))
      (node (ref "U48") (pin "1") (pinfunction "1_SIGNAL_TERMINAL_1") (pintype "passive"))
    )
    (net (code "13") (name "Net-(U49-1_SIGNAL_TERMINAL)") (class "Default")
      (node (ref "J5") (pin "16") (pinfunction "16_16") (pintype "passive"))
      (node (ref "U49") (pin "1") (pinfunction "1_SIGNAL_TERMINAL_1") (pintype "passive"))
      (node (ref "U50") (pin "1") (pinfunction "1_SIGNAL_TERMINAL_1") (pintype "passive"))
      (node (ref "U51") (pin "1") (pinfunction "1_SIGNAL_TERMINAL_1") (pintype "passive"))
      (node (ref "U52") (pin "1") (pinfunction "1_SIGNAL_TERMINAL_1") (pintype "passive"))
    )
    (net (code "14") (name "Net-(U53-1_SIGNAL_TERMINAL)") (class "Default")
      (node (ref "J8") (pin "2") (pinfunction "2_2") (pintype "passive"))
      (node (ref "U53") (pin "1") (pinfunction "1_SIGNAL_TERMINAL_1") (pintype "passive"))
      (node (ref "U54") (pin "1") (pinfunction "1_SIGNAL_TERMINAL_1") (pintype "passive"))
      (node (ref "U55") (pin "1") (pinfunction "1_SIGNAL_TERMINAL_1") (pintype "passive"))
      (node (ref "U56") (pin "1") (pinfunction "1_SIGNAL_TERMINAL_1") (pintype "passive"))
    )
    (net (code "15") (name "Net-(U57-1_SIGNAL_TERMINAL)") (class "Default")
      (node (ref "J7") (pin "16") (pinfunction "16_16") (pintype "passive"))
      (node (ref "U57") (pin "1") (pinfunction "1_SIGNAL_TERMINAL_1") (pintype "passive"))
      (node (ref "U58") (pin "1") (pinfunction "1_SIGNAL_TERMINAL_1") (pintype "passive"))
      (node (ref "U59") (pin "1") (pinfunction "1_SIGNAL_TERMINAL_1") (pintype "passive"))
      (node (ref "U60") (pin "1") (pinfunction "1_SIGNAL_TERMINAL_1") (pintype "passive"))
    )
    (net (code "16") (name "Net-(U61-1_SIGNAL_TERMINAL)") (class "Default")
      (node (ref "J7") (pin "14") (pinfunction "14_14") (pintype "passive"))
      (node (ref "U61") (pin "1") (pinfunction "1_SIGNAL_TERMINAL_1") (pintype "passive"))
      (node (ref "U62") (pin "1") (pinfunction "1_SIGNAL_TERMINAL_1") (pintype "passive"))
      (node (ref "U63") (pin "1") (pinfunction "1_SIGNAL_TERMINAL_1") (pintype "passive"))
      (node (ref "U64") (pin "1") (pinfunction "1_SIGNAL_TERMINAL_1") (pintype "passive"))
    )
    (net (code "17") (name "Net-(U65-1_SIGNAL_TERMINAL)") (class "Default")
      (node (ref "J7") (pin "12") (pinfunction "12_12") (pintype "passive"))
      (node (ref "U65") (pin "1") (pinfunction "1_SIGNAL_TERMINAL_1") (pintype "passive"))
      (node (ref "U66") (pin "1") (pinfunction "1_SIGNAL_TERMINAL_1") (pintype "passive"))
      (node (ref "U67") (pin "1") (pinfunction "1_SIGNAL_TERMINAL_1") (pintype "passive"))
      (node (ref "U68") (pin "1") (pinfunction "1_SIGNAL_TERMINAL_1") (pintype "passive"))
    )
    (net (code "18") (name "Net-(U69-1_SIGNAL_TERMINAL)") (class "Default")
      (node (ref "J7") (pin "10") (pinfunction "10_10") (pintype "passive"))
      (node (ref "U69") (pin "1") (pinfunction "1_SIGNAL_TERMINAL_1") (pintype "passive"))
      (node (ref "U70") (pin "1") (pinfunction "1_SIGNAL_TERMINAL_1") (pintype "passive"))
      (node (ref "U71") (pin "1") (pinfunction "1_SIGNAL_TERMINAL_1") (pintype "passive"))
      (node (ref "U72") (pin "1") (pinfunction "1_SIGNAL_TERMINAL_1") (pintype "passive"))
    )
    (net (code "19") (name "Net-(U73-1_SIGNAL_TERMINAL)") (class "Default")
      (node (ref "J7") (pin "8") (pinfunction "8_8") (pintype "passive"))
      (node (ref "U73") (pin "1") (pinfunction "1_SIGNAL_TERMINAL_1") (pintype "passive"))
      (node (ref "U74") (pin "1") (pinfunction "1_SIGNAL_TERMINAL_1") (pintype "passive"))
      (node (ref "U75") (pin "1") (pinfunction "1_SIGNAL_TERMINAL_1") (pintype "passive"))
      (node (ref "U76") (pin "1") (pinfunction "1_SIGNAL_TERMINAL_1") (pintype "passive"))
    )
    (net (code "20") (name "Net-(U77-1_SIGNAL_TERMINAL)") (class "Default")
      (node (ref "J7") (pin "6") (pinfunction "6_6") (pintype "passive"))
      (node (ref "U77") (pin "1") (pinfunction "1_SIGNAL_TERMINAL_1") (pintype "passive"))
      (node (ref "U78") (pin "1") (pinfunction "1_SIGNAL_TERMINAL_1") (pintype "passive"))
      (node (ref "U79") (pin "1") (pinfunction "1_SIGNAL_TERMINAL_1") (pintype "passive"))
      (node (ref "U80") (pin "1") (pinfunction "1_SIGNAL_TERMINAL_1") (pintype "passive"))
    )
    (net (code "21") (name "Net-(U92-1_SIGNAL_TERMINAL)") (class "Default")
      (node (ref "J5") (pin "12") (pinfunction "12_12") (pintype "passive"))
      (node (ref "U92") (pin "1") (pinfunction "1_SIGNAL_TERMINAL_1") (pintype "passive"))
      (node (ref "U93") (pin "1") (pinfunction "1_SIGNAL_TERMINAL_1") (pintype "passive"))
      (node (ref "U94") (pin "1") (pinfunction "1_SIGNAL_TERMINAL_1") (pintype "passive"))
      (node (ref "U95") (pin "1") (pinfunction "1_SIGNAL_TERMINAL_1") (pintype "passive"))
    )
    (net (code "22") (name "Net-(U96-1_SIGNAL_TERMINAL)") (class "Default")
      (node (ref "J8") (pin "4") (pinfunction "4_4") (pintype "passive"))
      (node (ref "U96") (pin "1") (pinfunction "1_SIGNAL_TERMINAL_1") (pintype "passive"))
      (node (ref "U97") (pin "1") (pinfunction "1_SIGNAL_TERMINAL_1") (pintype "passive"))
      (node (ref "U98") (pin "1") (pinfunction "1_SIGNAL_TERMINAL_1") (pintype "passive"))
      (node (ref "U99") (pin "1") (pinfunction "1_SIGNAL_TERMINAL_1") (pintype "passive"))
    )
    (net (code "23") (name "Net-(U100-1_SIGNAL_TERMINAL)") (class "Default")
      (node (ref "J8") (pin "14") (pinfunction "14_14") (pintype "passive"))
      (node (ref "U100") (pin "1") (pinfunction "1_SIGNAL_TERMINAL_1") (pintype "passive"))
      (node (ref "U101") (pin "1") (pinfunction "1_SIGNAL_TERMINAL_1") (pintype "passive"))
      (node (ref "U102") (pin "1") (pinfunction "1_SIGNAL_TERMINAL_1") (pintype "passive"))
      (node (ref "U103") (pin "1") (pinfunction "1_SIGNAL_TERMINAL_1") (pintype "passive"))
    )
    (net (code "24") (name "Net-(U104-1_SIGNAL_TERMINAL)") (class "Default")
      (node (ref "J8") (pin "16") (pinfunction "16_16") (pintype "passive"))
      (node (ref "U104") (pin "1") (pinfunction "1_SIGNAL_TERMINAL_1") (pintype "passive"))
      (node (ref "U105") (pin "1") (pinfunction "1_SIGNAL_TERMINAL_1") (pintype "passive"))
      (node (ref "U106") (pin "1") (pinfunction "1_SIGNAL_TERMINAL_1") (pintype "passive"))
      (node (ref "U107") (pin "1") (pinfunction "1_SIGNAL_TERMINAL_1") (pintype "passive"))
    )
    (net (code "25") (name "Net-(U108-1_SIGNAL_TERMINAL)") (class "Default")
      (node (ref "J5") (pin "6") (pinfunction "6_6") (pintype "passive"))
      (node (ref "U108") (pin "1") (pinfunction "1_SIGNAL_TERMINAL_1") (pintype "passive"))
      (node (ref "U109") (pin "1") (pinfunction "1_SIGNAL_TERMINAL_1") (pintype "passive"))
      (node (ref "U110") (pin "1") (pinfunction "1_SIGNAL_TERMINAL_1") (pintype "passive"))
      (node (ref "U111") (pin "1") (pinfunction "1_SIGNAL_TERMINAL_1") (pintype "passive"))
    )
    (net (code "26") (name "Net-(U112-1_SIGNAL_TERMINAL)") (class "Default")
      (node (ref "J6") (pin "14") (pinfunction "14_14") (pintype "passive"))
      (node (ref "U112") (pin "1") (pinfunction "1_SIGNAL_TERMINAL_1") (pintype "passive"))
      (node (ref "U113") (pin "1") (pinfunction "1_SIGNAL_TERMINAL_1") (pintype "passive"))
      (node (ref "U114") (pin "1") (pinfunction "1_SIGNAL_TERMINAL_1") (pintype "passive"))
      (node (ref "U115") (pin "1") (pinfunction "1_SIGNAL_TERMINAL_1") (pintype "passive"))
    )
    (net (code "27") (name "Net-(U116-1_SIGNAL_TERMINAL)") (class "Default")
      (node (ref "J4") (pin "8") (pinfunction "8_8") (pintype "passive"))
      (node (ref "U116") (pin "1") (pinfunction "1_SIGNAL_TERMINAL_1") (pintype "passive"))
      (node (ref "U117") (pin "1") (pinfunction "1_SIGNAL_TERMINAL_1") (pintype "passive"))
      (node (ref "U90") (pin "1") (pinfunction "1_SIGNAL_TERMINAL_1") (pintype "passive"))
      (node (ref "U91") (pin "1") (pinfunction "1_SIGNAL_TERMINAL_1") (pintype "passive"))
    )
    (net (code "28") (name "Net-(U118-1_SIGNAL_TERMINAL)") (class "Default")
      (node (ref "J3") (pin "4") (pinfunction "4_4") (pintype "passive"))
      (node (ref "U118") (pin "1") (pinfunction "1_SIGNAL_TERMINAL_1") (pintype "passive"))
      (node (ref "U170") (pin "1") (pinfunction "1_SIGNAL_TERMINAL_1") (pintype "passive"))
      (node (ref "U171") (pin "1") (pinfunction "1_SIGNAL_TERMINAL_1") (pintype "passive"))
      (node (ref "U172") (pin "1") (pinfunction "1_SIGNAL_TERMINAL_1") (pintype "passive"))
    )
    (net (code "29") (name "Net-(U119-1_SIGNAL_TERMINAL)") (class "Default")
      (node (ref "J5") (pin "4") (pinfunction "4_4") (pintype "passive"))
      (node (ref "U119") (pin "1") (pinfunction "1_SIGNAL_TERMINAL_1") (pintype "passive"))
      (node (ref "U120") (pin "1") (pinfunction "1_SIGNAL_TERMINAL_1") (pintype "passive"))
      (node (ref "U121") (pin "1") (pinfunction "1_SIGNAL_TERMINAL_1") (pintype "passive"))
      (node (ref "U122") (pin "1") (pinfunction "1_SIGNAL_TERMINAL_1") (pintype "passive"))
    )
    (net (code "30") (name "Net-(U123-1_SIGNAL_TERMINAL)") (class "Default")
      (node (ref "J5") (pin "10") (pinfunction "10_10") (pintype "passive"))
      (node (ref "U123") (pin "1") (pinfunction "1_SIGNAL_TERMINAL_1") (pintype "passive"))
      (node (ref "U124") (pin "1") (pinfunction "1_SIGNAL_TERMINAL_1") (pintype "passive"))
      (node (ref "U125") (pin "1") (pinfunction "1_SIGNAL_TERMINAL_1") (pintype "passive"))
      (node (ref "U126") (pin "1") (pinfunction "1_SIGNAL_TERMINAL_1") (pintype "passive"))
    )
    (net (code "31") (name "Net-(U127-1_SIGNAL_TERMINAL)") (class "Default")
      (node (ref "J8") (pin "6") (pinfunction "6_6") (pintype "passive"))
      (node (ref "U127") (pin "1") (pinfunction "1_SIGNAL_TERMINAL_1") (pintype "passive"))
      (node (ref "U128") (pin "1") (pinfunction "1_SIGNAL_TERMINAL_1") (pintype "passive"))
      (node (ref "U129") (pin "1") (pinfunction "1_SIGNAL_TERMINAL_1") (pintype "passive"))
      (node (ref "U130") (pin "1") (pinfunction "1_SIGNAL_TERMINAL_1") (pintype "passive"))
    )
    (net (code "32") (name "Net-(U131-1_SIGNAL_TERMINAL)") (class "Default")
      (node (ref "J8") (pin "12") (pinfunction "12_12") (pintype "passive"))
      (node (ref "U131") (pin "1") (pinfunction "1_SIGNAL_TERMINAL_1") (pintype "passive"))
      (node (ref "U132") (pin "1") (pinfunction "1_SIGNAL_TERMINAL_1") (pintype "passive"))
      (node (ref "U133") (pin "1") (pinfunction "1_SIGNAL_TERMINAL_1") (pintype "passive"))
      (node (ref "U134") (pin "1") (pinfunction "1_SIGNAL_TERMINAL_1") (pintype "passive"))
    )
    (net (code "33") (name "Net-(U135-1_SIGNAL_TERMINAL)") (class "Default")
      (node (ref "J6") (pin "16") (pinfunction "16_16") (pintype "passive"))
      (node (ref "U135") (pin "1") (pinfunction "1_SIGNAL_TERMINAL_1") (pintype "passive"))
      (node (ref "U136") (pin "1") (pinfunction "1_SIGNAL_TERMINAL_1") (pintype "passive"))
      (node (ref "U137") (pin "1") (pinfunction "1_SIGNAL_TERMINAL_1") (pintype "passive"))
      (node (ref "U138") (pin "1") (pinfunction "1_SIGNAL_TERMINAL_1") (pintype "passive"))
    )
    (net (code "34") (name "Net-(U139-1_SIGNAL_TERMINAL)") (class "Default")
      (node (ref "J6") (pin "8") (pinfunction "8_8") (pintype "passive"))
      (node (ref "U139") (pin "1") (pinfunction "1_SIGNAL_TERMINAL_1") (pintype "passive"))
      (node (ref "U140") (pin "1") (pinfunction "1_SIGNAL_TERMINAL_1") (pintype "passive"))
      (node (ref "U141") (pin "1") (pinfunction "1_SIGNAL_TERMINAL_1") (pintype "passive"))
      (node (ref "U142") (pin "1") (pinfunction "1_SIGNAL_TERMINAL_1") (pintype "passive"))
    )
    (net (code "35") (name "Net-(U143-1_SIGNAL_TERMINAL)") (class "Default")
      (node (ref "J5") (pin "2") (pinfunction "2_2") (pintype "passive"))
      (node (ref "U143") (pin "1") (pinfunction "1_SIGNAL_TERMINAL_1") (pintype "passive"))
      (node (ref "U144") (pin "1") (pinfunction "1_SIGNAL_TERMINAL_1") (pintype "passive"))
      (node (ref "U145") (pin "1") (pinfunction "1_SIGNAL_TERMINAL_1") (pintype "passive"))
      (node (ref "U149") (pin "1") (pinfunction "1_SIGNAL_TERMINAL_1") (pintype "passive"))
    )
    (net (code "36") (name "Net-(U146-1_SIGNAL_TERMINAL)") (class "Default")
      (node (ref "J6") (pin "4") (pinfunction "4_4") (pintype "passive"))
      (node (ref "U146") (pin "1") (pinfunction "1_SIGNAL_TERMINAL_1") (pintype "passive"))
      (node (ref "U147") (pin "1") (pinfunction "1_SIGNAL_TERMINAL_1") (pintype "passive"))
      (node (ref "U148") (pin "1") (pinfunction "1_SIGNAL_TERMINAL_1") (pintype "passive"))
    )
    (net (code "37") (name "Net-(U150-1_SIGNAL_TERMINAL)") (class "Default")
      (node (ref "J5") (pin "8") (pinfunction "8_8") (pintype "passive"))
      (node (ref "U150") (pin "1") (pinfunction "1_SIGNAL_TERMINAL_1") (pintype "passive"))
      (node (ref "U151") (pin "1") (pinfunction "1_SIGNAL_TERMINAL_1") (pintype "passive"))
      (node (ref "U152") (pin "1") (pinfunction "1_SIGNAL_TERMINAL_1") (pintype "passive"))
      (node (ref "U153") (pin "1") (pinfunction "1_SIGNAL_TERMINAL_1") (pintype "passive"))
    )
    (net (code "38") (name "Net-(U154-1_SIGNAL_TERMINAL)") (class "Default")
      (node (ref "J8") (pin "8") (pinfunction "8_8") (pintype "passive"))
      (node (ref "U154") (pin "1") (pinfunction "1_SIGNAL_TERMINAL_1") (pintype "passive"))
      (node (ref "U155") (pin "1") (pinfunction "1_SIGNAL_TERMINAL_1") (pintype "passive"))
      (node (ref "U156") (pin "1") (pinfunction "1_SIGNAL_TERMINAL_1") (pintype "passive"))
      (node (ref "U157") (pin "1") (pinfunction "1_SIGNAL_TERMINAL_1") (pintype "passive"))
    )
    (net (code "39") (name "Net-(U158-1_SIGNAL_TERMINAL)") (class "Default")
      (node (ref "J8") (pin "10") (pinfunction "10_10") (pintype "passive"))
      (node (ref "U158") (pin "1") (pinfunction "1_SIGNAL_TERMINAL_1") (pintype "passive"))
      (node (ref "U159") (pin "1") (pinfunction "1_SIGNAL_TERMINAL_1") (pintype "passive"))
      (node (ref "U160") (pin "1") (pinfunction "1_SIGNAL_TERMINAL_1") (pintype "passive"))
      (node (ref "U161") (pin "1") (pinfunction "1_SIGNAL_TERMINAL_1") (pintype "passive"))
    )
    (net (code "40") (name "Net-(U162-1_SIGNAL_TERMINAL)") (class "Default")
      (node (ref "J6") (pin "12") (pinfunction "12_12") (pintype "passive"))
      (node (ref "U162") (pin "1") (pinfunction "1_SIGNAL_TERMINAL_1") (pintype "passive"))
      (node (ref "U163") (pin "1") (pinfunction "1_SIGNAL_TERMINAL_1") (pintype "passive"))
      (node (ref "U164") (pin "1") (pinfunction "1_SIGNAL_TERMINAL_1") (pintype "passive"))
      (node (ref "U165") (pin "1") (pinfunction "1_SIGNAL_TERMINAL_1") (pintype "passive"))
    )
    (net (code "41") (name "Net-(U166-1_SIGNAL_TERMINAL)") (class "Default")
      (node (ref "J6") (pin "6") (pinfunction "6_6") (pintype "passive"))
      (node (ref "U166") (pin "1") (pinfunction "1_SIGNAL_TERMINAL_1") (pintype "passive"))
      (node (ref "U167") (pin "1") (pinfunction "1_SIGNAL_TERMINAL_1") (pintype "passive"))
      (node (ref "U168") (pin "1") (pinfunction "1_SIGNAL_TERMINAL_1") (pintype "passive"))
      (node (ref "U169") (pin "1") (pinfunction "1_SIGNAL_TERMINAL_1") (pintype "passive"))
    )
    (net (code "42") (name "Net-(U173-1_SIGNAL_TERMINAL)") (class "Default")
      (node (ref "J3") (pin "6") (pinfunction "6_6") (pintype "passive"))
      (node (ref "U173") (pin "1") (pinfunction "1_SIGNAL_TERMINAL_1") (pintype "passive"))
      (node (ref "U174") (pin "1") (pinfunction "1_SIGNAL_TERMINAL_1") (pintype "passive"))
      (node (ref "U175") (pin "1") (pinfunction "1_SIGNAL_TERMINAL_1") (pintype "passive"))
      (node (ref "U176") (pin "1") (pinfunction "1_SIGNAL_TERMINAL_1") (pintype "passive"))
    )
    (net (code "43") (name "Net-(U177-1_SIGNAL_TERMINAL)") (class "Default")
      (node (ref "J3") (pin "10") (pinfunction "10_10") (pintype "passive"))
      (node (ref "U177") (pin "1") (pinfunction "1_SIGNAL_TERMINAL_1") (pintype "passive"))
      (node (ref "U178") (pin "1") (pinfunction "1_SIGNAL_TERMINAL_1") (pintype "passive"))
      (node (ref "U179") (pin "1") (pinfunction "1_SIGNAL_TERMINAL_1") (pintype "passive"))
      (node (ref "U180") (pin "1") (pinfunction "1_SIGNAL_TERMINAL_1") (pintype "passive"))
    )
    (net (code "44") (name "Net-(U184-1_SIGNAL_TERMINAL)") (class "Default")
      (node (ref "J4") (pin "6") (pinfunction "6_6") (pintype "passive"))
      (node (ref "U184") (pin "1") (pinfunction "1_SIGNAL_TERMINAL_1") (pintype "passive"))
      (node (ref "U185") (pin "1") (pinfunction "1_SIGNAL_TERMINAL_1") (pintype "passive"))
      (node (ref "U186") (pin "1") (pinfunction "1_SIGNAL_TERMINAL_1") (pintype "passive"))
    )
    (net (code "45") (name "Net-(U192-1_SIGNAL_TERMINAL)") (class "Default")
      (node (ref "J2") (pin "8") (pinfunction "8_8") (pintype "passive"))
      (node (ref "U192") (pin "1") (pinfunction "1_SIGNAL_TERMINAL_1") (pintype "passive"))
      (node (ref "U193") (pin "1") (pinfunction "1_SIGNAL_TERMINAL_1") (pintype "passive"))
      (node (ref "U194") (pin "1") (pinfunction "1_SIGNAL_TERMINAL_1") (pintype "passive"))
      (node (ref "U195") (pin "1") (pinfunction "1_SIGNAL_TERMINAL_1") (pintype "passive"))
    )
    (net (code "46") (name "Net-(U196-1_SIGNAL_TERMINAL)") (class "Default")
      (node (ref "J2") (pin "14") (pinfunction "14_14") (pintype "passive"))
      (node (ref "U196") (pin "1") (pinfunction "1_SIGNAL_TERMINAL_1") (pintype "passive"))
      (node (ref "U197") (pin "1") (pinfunction "1_SIGNAL_TERMINAL_1") (pintype "passive"))
      (node (ref "U198") (pin "1") (pinfunction "1_SIGNAL_TERMINAL_1") (pintype "passive"))
      (node (ref "U199") (pin "1") (pinfunction "1_SIGNAL_TERMINAL_1") (pintype "passive"))
    )
    (net (code "47") (name "Net-(U200-1_SIGNAL_TERMINAL)") (class "Default")
      (node (ref "J3") (pin "8") (pinfunction "8_8") (pintype "passive"))
      (node (ref "U200") (pin "1") (pinfunction "1_SIGNAL_TERMINAL_1") (pintype "passive"))
      (node (ref "U201") (pin "1") (pinfunction "1_SIGNAL_TERMINAL_1") (pintype "passive"))
      (node (ref "U202") (pin "1") (pinfunction "1_SIGNAL_TERMINAL_1") (pintype "passive"))
      (node (ref "U203") (pin "1") (pinfunction "1_SIGNAL_TERMINAL_1") (pintype "passive"))
    )
    (net (code "48") (name "Net-(U204-1_SIGNAL_TERMINAL)") (class "Default")
      (node (ref "J3") (pin "12") (pinfunction "12_12") (pintype "passive"))
      (node (ref "U204") (pin "1") (pinfunction "1_SIGNAL_TERMINAL_1") (pintype "passive"))
      (node (ref "U205") (pin "1") (pinfunction "1_SIGNAL_TERMINAL_1") (pintype "passive"))
      (node (ref "U206") (pin "1") (pinfunction "1_SIGNAL_TERMINAL_1") (pintype "passive"))
      (node (ref "U207") (pin "1") (pinfunction "1_SIGNAL_TERMINAL_1") (pintype "passive"))
    )
    (net (code "49") (name "Net-(U208-1_SIGNAL_TERMINAL)") (class "Default")
      (node (ref "J1") (pin "14") (pinfunction "14_14") (pintype "passive"))
      (node (ref "U208") (pin "1") (pinfunction "1_SIGNAL_TERMINAL_1") (pintype "passive"))
      (node (ref "U209") (pin "1") (pinfunction "1_SIGNAL_TERMINAL_1") (pintype "passive"))
      (node (ref "U210") (pin "1") (pinfunction "1_SIGNAL_TERMINAL_1") (pintype "passive"))
      (node (ref "U211") (pin "1") (pinfunction "1_SIGNAL_TERMINAL_1") (pintype "passive"))
    )
    (net (code "50") (name "Net-(U212-1_SIGNAL_TERMINAL)") (class "Default")
      (node (ref "J1") (pin "8") (pinfunction "8_8") (pintype "passive"))
      (node (ref "U212") (pin "1") (pinfunction "1_SIGNAL_TERMINAL_1") (pintype "passive"))
      (node (ref "U213") (pin "1") (pinfunction "1_SIGNAL_TERMINAL_1") (pintype "passive"))
      (node (ref "U214") (pin "1") (pinfunction "1_SIGNAL_TERMINAL_1") (pintype "passive"))
      (node (ref "U215") (pin "1") (pinfunction "1_SIGNAL_TERMINAL_1") (pintype "passive"))
    )
    (net (code "51") (name "Net-(U216-1_SIGNAL_TERMINAL)") (class "Default")
      (node (ref "J2") (pin "4") (pinfunction "4_4") (pintype "passive"))
      (node (ref "U216") (pin "1") (pinfunction "1_SIGNAL_TERMINAL_1") (pintype "passive"))
      (node (ref "U217") (pin "1") (pinfunction "1_SIGNAL_TERMINAL_1") (pintype "passive"))
      (node (ref "U218") (pin "1") (pinfunction "1_SIGNAL_TERMINAL_1") (pintype "passive"))
      (node (ref "U222") (pin "1") (pinfunction "1_SIGNAL_TERMINAL_1") (pintype "passive"))
    )
    (net (code "52") (name "Net-(U219-1_SIGNAL_TERMINAL)") (class "Default")
      (node (ref "J1") (pin "6") (pinfunction "6_6") (pintype "passive"))
      (node (ref "U219") (pin "1") (pinfunction "1_SIGNAL_TERMINAL_1") (pintype "passive"))
      (node (ref "U220") (pin "1") (pinfunction "1_SIGNAL_TERMINAL_1") (pintype "passive"))
      (node (ref "U221") (pin "1") (pinfunction "1_SIGNAL_TERMINAL_1") (pintype "passive"))
    )
    (net (code "53") (name "Net-(U223-1_SIGNAL_TERMINAL)") (class "Default")
      (node (ref "J2") (pin "12") (pinfunction "12_12") (pintype "passive"))
      (node (ref "U223") (pin "1") (pinfunction "1_SIGNAL_TERMINAL_1") (pintype "passive"))
      (node (ref "U224") (pin "1") (pinfunction "1_SIGNAL_TERMINAL_1") (pintype "passive"))
      (node (ref "U225") (pin "1") (pinfunction "1_SIGNAL_TERMINAL_1") (pintype "passive"))
      (node (ref "U226") (pin "1") (pinfunction "1_SIGNAL_TERMINAL_1") (pintype "passive"))
    )
    (net (code "54") (name "Net-(U227-1_SIGNAL_TERMINAL)") (class "Default")
      (node (ref "J3") (pin "2") (pinfunction "2_2") (pintype "passive"))
      (node (ref "U227") (pin "1") (pinfunction "1_SIGNAL_TERMINAL_1") (pintype "passive"))
      (node (ref "U228") (pin "1") (pinfunction "1_SIGNAL_TERMINAL_1") (pintype "passive"))
      (node (ref "U229") (pin "1") (pinfunction "1_SIGNAL_TERMINAL_1") (pintype "passive"))
      (node (ref "U230") (pin "1") (pinfunction "1_SIGNAL_TERMINAL_1") (pintype "passive"))
    )
    (net (code "55") (name "Net-(U231-1_SIGNAL_TERMINAL)") (class "Default")
      (node (ref "J3") (pin "16") (pinfunction "16_16") (pintype "passive"))
      (node (ref "U231") (pin "1") (pinfunction "1_SIGNAL_TERMINAL_1") (pintype "passive"))
      (node (ref "U232") (pin "1") (pinfunction "1_SIGNAL_TERMINAL_1") (pintype "passive"))
      (node (ref "U233") (pin "1") (pinfunction "1_SIGNAL_TERMINAL_1") (pintype "passive"))
      (node (ref "U234") (pin "1") (pinfunction "1_SIGNAL_TERMINAL_1") (pintype "passive"))
    )
    (net (code "56") (name "Net-(U235-1_SIGNAL_TERMINAL)") (class "Default")
      (node (ref "J2") (pin "2") (pinfunction "2_2") (pintype "passive"))
      (node (ref "U235") (pin "1") (pinfunction "1_SIGNAL_TERMINAL_1") (pintype "passive"))
      (node (ref "U236") (pin "1") (pinfunction "1_SIGNAL_TERMINAL_1") (pintype "passive"))
      (node (ref "U237") (pin "1") (pinfunction "1_SIGNAL_TERMINAL_1") (pintype "passive"))
      (node (ref "U238") (pin "1") (pinfunction "1_SIGNAL_TERMINAL_1") (pintype "passive"))
    )
    (net (code "57") (name "Net-(U239-1_SIGNAL_TERMINAL)") (class "Default")
      (node (ref "J1") (pin "12") (pinfunction "12_12") (pintype "passive"))
      (node (ref "U239") (pin "1") (pinfunction "1_SIGNAL_TERMINAL_1") (pintype "passive"))
      (node (ref "U240") (pin "1") (pinfunction "1_SIGNAL_TERMINAL_1") (pintype "passive"))
      (node (ref "U241") (pin "1") (pinfunction "1_SIGNAL_TERMINAL_1") (pintype "passive"))
      (node (ref "U242") (pin "1") (pinfunction "1_SIGNAL_TERMINAL_1") (pintype "passive"))
    )
    (net (code "58") (name "Net-(U246-1_SIGNAL_TERMINAL)") (class "Default")
      (node (ref "J2") (pin "6") (pinfunction "6_6") (pintype "passive"))
      (node (ref "U246") (pin "1") (pinfunction "1_SIGNAL_TERMINAL_1") (pintype "passive"))
      (node (ref "U247") (pin "1") (pinfunction "1_SIGNAL_TERMINAL_1") (pintype "passive"))
      (node (ref "U248") (pin "1") (pinfunction "1_SIGNAL_TERMINAL_1") (pintype "passive"))
      (node (ref "U249") (pin "1") (pinfunction "1_SIGNAL_TERMINAL_1") (pintype "passive"))
    )
    (net (code "59") (name "Net-(U250-1_SIGNAL_TERMINAL)") (class "Default")
      (node (ref "J2") (pin "10") (pinfunction "10_10") (pintype "passive"))
      (node (ref "U250") (pin "1") (pinfunction "1_SIGNAL_TERMINAL_1") (pintype "passive"))
      (node (ref "U251") (pin "1") (pinfunction "1_SIGNAL_TERMINAL_1") (pintype "passive"))
      (node (ref "U252") (pin "1") (pinfunction "1_SIGNAL_TERMINAL_1") (pintype "passive"))
      (node (ref "U253") (pin "1") (pinfunction "1_SIGNAL_TERMINAL_1") (pintype "passive"))
    )
    (net (code "60") (name "Net-(U254-1_SIGNAL_TERMINAL)") (class "Default")
      (node (ref "J2") (pin "16") (pinfunction "16_16") (pintype "passive"))
      (node (ref "U254") (pin "1") (pinfunction "1_SIGNAL_TERMINAL_1") (pintype "passive"))
      (node (ref "U255") (pin "1") (pinfunction "1_SIGNAL_TERMINAL_1") (pintype "passive"))
      (node (ref "U256") (pin "1") (pinfunction "1_SIGNAL_TERMINAL_1") (pintype "passive"))
      (node (ref "U257") (pin "1") (pinfunction "1_SIGNAL_TERMINAL_1") (pintype "passive"))
    )
    (net (code "61") (name "Net-(U258-1_SIGNAL_TERMINAL)") (class "Default")
      (node (ref "J3") (pin "14") (pinfunction "14_14") (pintype "passive"))
      (node (ref "U258") (pin "1") (pinfunction "1_SIGNAL_TERMINAL_1") (pintype "passive"))
      (node (ref "U259") (pin "1") (pinfunction "1_SIGNAL_TERMINAL_1") (pintype "passive"))
      (node (ref "U260") (pin "1") (pinfunction "1_SIGNAL_TERMINAL_1") (pintype "passive"))
      (node (ref "U261") (pin "1") (pinfunction "1_SIGNAL_TERMINAL_1") (pintype "passive"))
    )
    (net (code "62") (name "Net-(U262-1_SIGNAL_TERMINAL)") (class "Default")
      (node (ref "J1") (pin "16") (pinfunction "16_16") (pintype "passive"))
      (node (ref "U262") (pin "1") (pinfunction "1_SIGNAL_TERMINAL_1") (pintype "passive"))
      (node (ref "U263") (pin "1") (pinfunction "1_SIGNAL_TERMINAL_1") (pintype "passive"))
      (node (ref "U264") (pin "1") (pinfunction "1_SIGNAL_TERMINAL_1") (pintype "passive"))
      (node (ref "U265") (pin "1") (pinfunction "1_SIGNAL_TERMINAL_1") (pintype "passive"))
    )
    (net (code "63") (name "Net-(U266-1_SIGNAL_TERMINAL)") (class "Default")
      (node (ref "J1") (pin "10") (pinfunction "10_10") (pintype "passive"))
      (node (ref "U266") (pin "1") (pinfunction "1_SIGNAL_TERMINAL_1") (pintype "passive"))
      (node (ref "U267") (pin "1") (pinfunction "1_SIGNAL_TERMINAL_1") (pintype "passive"))
      (node (ref "U268") (pin "1") (pinfunction "1_SIGNAL_TERMINAL_1") (pintype "passive"))
      (node (ref "U269") (pin "1") (pinfunction "1_SIGNAL_TERMINAL_1") (pintype "passive"))
    )
    (net (code "64") (name "Net-(U270-1_SIGNAL_TERMINAL)") (class "Default")
      (node (ref "J1") (pin "2") (pinfunction "2_2") (pintype "passive"))
      (node (ref "U270") (pin "1") (pinfunction "1_SIGNAL_TERMINAL_1") (pintype "passive"))
      (node (ref "U271") (pin "1") (pinfunction "1_SIGNAL_TERMINAL_1") (pintype "passive"))
      (node (ref "U272") (pin "1") (pinfunction "1_SIGNAL_TERMINAL_1") (pintype "passive"))
    )
    (net (code "65") (name "Net-(U273-1_SIGNAL_TERMINAL)") (class "Default")
      (node (ref "J1") (pin "4") (pinfunction "4_4") (pintype "passive"))
      (node (ref "U273") (pin "1") (pinfunction "1_SIGNAL_TERMINAL_1") (pintype "passive"))
      (node (ref "U274") (pin "1") (pinfunction "1_SIGNAL_TERMINAL_1") (pintype "passive"))
      (node (ref "U275") (pin "1") (pinfunction "1_SIGNAL_TERMINAL_1") (pintype "passive"))
    )
    (net (code "66") (name "unconnected-(J1-Pad1)") (class "Default")
      (node (ref "J1") (pin "1") (pinfunction "1_1") (pintype "passive"))
    )
    (net (code "67") (name "unconnected-(J1-Pad3)") (class "Default")
      (node (ref "J1") (pin "3") (pinfunction "3_3") (pintype "passive"))
    )
    (net (code "68") (name "unconnected-(J1-Pad5)") (class "Default")
      (node (ref "J1") (pin "5") (pinfunction "5_5") (pintype "passive"))
    )
    (net (code "69") (name "unconnected-(J1-Pad7)") (class "Default")
      (node (ref "J1") (pin "7") (pinfunction "7_7") (pintype "passive"))
    )
    (net (code "70") (name "unconnected-(J1-Pad9)") (class "Default")
      (node (ref "J1") (pin "9") (pinfunction "9_9") (pintype "passive"))
    )
    (net (code "71") (name "unconnected-(J1-Pad11)") (class "Default")
      (node (ref "J1") (pin "11") (pinfunction "11_11") (pintype "passive"))
    )
    (net (code "72") (name "unconnected-(J1-Pad13)") (class "Default")
      (node (ref "J1") (pin "13") (pinfunction "13_13") (pintype "passive"))
    )
    (net (code "73") (name "unconnected-(J1-Pad15)") (class "Default")
      (node (ref "J1") (pin "15") (pinfunction "15_15") (pintype "passive"))
    )
    (net (code "74") (name "unconnected-(J2-Pad1)") (class "Default")
      (node (ref "J2") (pin "1") (pinfunction "1_1") (pintype "passive"))
    )
    (net (code "75") (name "unconnected-(J2-Pad3)") (class "Default")
      (node (ref "J2") (pin "3") (pinfunction "3_3") (pintype "passive"))
    )
    (net (code "76") (name "unconnected-(J2-Pad5)") (class "Default")
      (node (ref "J2") (pin "5") (pinfunction "5_5") (pintype "passive"))
    )
    (net (code "77") (name "unconnected-(J2-Pad7)") (class "Default")
      (node (ref "J2") (pin "7") (pinfunction "7_7") (pintype "passive"))
    )
    (net (code "78") (name "unconnected-(J2-Pad9)") (class "Default")
      (node (ref "J2") (pin "9") (pinfunction "9_9") (pintype "passive"))
    )
    (net (code "79") (name "unconnected-(J2-Pad11)") (class "Default")
      (node (ref "J2") (pin "11") (pinfunction "11_11") (pintype "passive"))
    )
    (net (code "80") (name "unconnected-(J2-Pad13)") (class "Default")
      (node (ref "J2") (pin "13") (pinfunction "13_13") (pintype "passive"))
    )
    (net (code "81") (name "unconnected-(J2-Pad15)") (class "Default")
      (node (ref "J2") (pin "15") (pinfunction "15_15") (pintype "passive"))
    )
    (net (code "82") (name "unconnected-(J3-Pad1)") (class "Default")
      (node (ref "J3") (pin "1") (pinfunction "1_1") (pintype "passive"))
    )
    (net (code "83") (name "unconnected-(J3-Pad3)") (class "Default")
      (node (ref "J3") (pin "3") (pinfunction "3_3") (pintype "passive"))
    )
    (net (code "84") (name "unconnected-(J3-Pad5)") (class "Default")
      (node (ref "J3") (pin "5") (pinfunction "5_5") (pintype "passive"))
    )
    (net (code "85") (name "unconnected-(J3-Pad7)") (class "Default")
      (node (ref "J3") (pin "7") (pinfunction "7_7") (pintype "passive"))
    )
    (net (code "86") (name "unconnected-(J3-Pad9)") (class "Default")
      (node (ref "J3") (pin "9") (pinfunction "9_9") (pintype "passive"))
    )
    (net (code "87") (name "unconnected-(J3-Pad11)") (class "Default")
      (node (ref "J3") (pin "11") (pinfunction "11_11") (pintype "passive"))
    )
    (net (code "88") (name "unconnected-(J3-Pad13)") (class "Default")
      (node (ref "J3") (pin "13") (pinfunction "13_13") (pintype "passive"))
    )
    (net (code "89") (name "unconnected-(J3-Pad15)") (class "Default")
      (node (ref "J3") (pin "15") (pinfunction "15_15") (pintype "passive"))
    )
    (net (code "90") (name "unconnected-(J4-Pad1)") (class "Default")
      (node (ref "J4") (pin "1") (pinfunction "1_1") (pintype "passive"))
    )
    (net (code "91") (name "unconnected-(J4-Pad3)") (class "Default")
      (node (ref "J4") (pin "3") (pinfunction "3_3") (pintype "passive"))
    )
    (net (code "92") (name "unconnected-(J4-Pad5)") (class "Default")
      (node (ref "J4") (pin "5") (pinfunction "5_5") (pintype "passive"))
    )
    (net (code "93") (name "unconnected-(J4-Pad7)") (class "Default")
      (node (ref "J4") (pin "7") (pinfunction "7_7") (pintype "passive"))
    )
    (net (code "94") (name "unconnected-(J4-Pad9)") (class "Default")
      (node (ref "J4") (pin "9") (pinfunction "9_9") (pintype "passive"))
    )
    (net (code "95") (name "unconnected-(J4-Pad11)") (class "Default")
      (node (ref "J4") (pin "11") (pinfunction "11_11") (pintype "passive"))
    )
    (net (code "96") (name "unconnected-(J4-Pad13)") (class "Default")
      (node (ref "J4") (pin "13") (pinfunction "13_13") (pintype "passive"))
    )
    (net (code "97") (name "unconnected-(J4-Pad15)") (class "Default")
      (node (ref "J4") (pin "15") (pinfunction "15_15") (pintype "passive"))
    )
    (net (code "98") (name "unconnected-(J5-Pad1)") (class "Default")
      (node (ref "J5") (pin "1") (pinfunction "1_1") (pintype "passive"))
    )
    (net (code "99") (name "unconnected-(J5-Pad3)") (class "Default")
      (node (ref "J5") (pin "3") (pinfunction "3_3") (pintype "passive"))
    )
    (net (code "100") (name "unconnected-(J5-Pad5)") (class "Default")
      (node (ref "J5") (pin "5") (pinfunction "5_5") (pintype "passive"))
    )
    (net (code "101") (name "unconnected-(J5-Pad7)") (class "Default")
      (node (ref "J5") (pin "7") (pinfunction "7_7") (pintype "passive"))
    )
    (net (code "102") (name "unconnected-(J5-Pad9)") (class "Default")
      (node (ref "J5") (pin "9") (pinfunction "9_9") (pintype "passive"))
    )
    (net (code "103") (name "unconnected-(J5-Pad11)") (class "Default")
      (node (ref "J5") (pin "11") (pinfunction "11_11") (pintype "passive"))
    )
    (net (code "104") (name "unconnected-(J5-Pad13)") (class "Default")
      (node (ref "J5") (pin "13") (pinfunction "13_13") (pintype "passive"))
    )
    (net (code "105") (name "unconnected-(J5-Pad15)") (class "Default")
      (node (ref "J5") (pin "15") (pinfunction "15_15") (pintype "passive"))
    )
    (net (code "106") (name "unconnected-(J6-Pad1)") (class "Default")
      (node (ref "J6") (pin "1") (pinfunction "1_1") (pintype "passive"))
    )
    (net (code "107") (name "unconnected-(J6-Pad3)") (class "Default")
      (node (ref "J6") (pin "3") (pinfunction "3_3") (pintype "passive"))
    )
    (net (code "108") (name "unconnected-(J6-Pad5)") (class "Default")
      (node (ref "J6") (pin "5") (pinfunction "5_5") (pintype "passive"))
    )
    (net (code "109") (name "unconnected-(J6-Pad7)") (class "Default")
      (node (ref "J6") (pin "7") (pinfunction "7_7") (pintype "passive"))
    )
    (net (code "110") (name "unconnected-(J6-Pad9)") (class "Default")
      (node (ref "J6") (pin "9") (pinfunction "9_9") (pintype "passive"))
    )
    (net (code "111") (name "unconnected-(J6-Pad11)") (class "Default")
      (node (ref "J6") (pin "11") (pinfunction "11_11") (pintype "passive"))
    )
    (net (code "112") (name "unconnected-(J6-Pad13)") (class "Default")
      (node (ref "J6") (pin "13") (pinfunction "13_13") (pintype "passive"))
    )
    (net (code "113") (name "unconnected-(J6-Pad15)") (class "Default")
      (node (ref "J6") (pin "15") (pinfunction "15_15") (pintype "passive"))
    )
    (net (code "114") (name "unconnected-(J7-Pad1)") (class "Default")
      (node (ref "J7") (pin "1") (pinfunction "1_1") (pintype "passive"))
    )
    (net (code "115") (name "unconnected-(J7-Pad3)") (class "Default")
      (node (ref "J7") (pin "3") (pinfunction "3_3") (pintype "passive"))
    )
    (net (code "116") (name "unconnected-(J7-Pad5)") (class "Default")
      (node (ref "J7") (pin "5") (pinfunction "5_5") (pintype "passive"))
    )
    (net (code "117") (name "unconnected-(J7-Pad7)") (class "Default")
      (node (ref "J7") (pin "7") (pinfunction "7_7") (pintype "passive"))
    )
    (net (code "118") (name "unconnected-(J7-Pad9)") (class "Default")
      (node (ref "J7") (pin "9") (pinfunction "9_9") (pintype "passive"))
    )
    (net (code "119") (name "unconnected-(J7-Pad11)") (class "Default")
      (node (ref "J7") (pin "11") (pinfunction "11_11") (pintype "passive"))
    )
    (net (code "120") (name "unconnected-(J7-Pad13)") (class "Default")
      (node (ref "J7") (pin "13") (pinfunction "13_13") (pintype "passive"))
    )
    (net (code "121") (name "unconnected-(J7-Pad15)") (class "Default")
      (node (ref "J7") (pin "15") (pinfunction "15_15") (pintype "passive"))
    )
    (net (code "122") (name "unconnected-(J8-Pad1)") (class "Default")
      (node (ref "J8") (pin "1") (pinfunction "1_1") (pintype "passive"))
    )
    (net (code "123") (name "unconnected-(J8-Pad3)") (class "Default")
      (node (ref "J8") (pin "3") (pinfunction "3_3") (pintype "passive"))
    )
    (net (code "124") (name "unconnected-(J8-Pad5)") (class "Default")
      (node (ref "J8") (pin "5") (pinfunction "5_5") (pintype "passive"))
    )
    (net (code "125") (name "unconnected-(J8-Pad7)") (class "Default")
      (node (ref "J8") (pin "7") (pinfunction "7_7") (pintype "passive"))
    )
    (net (code "126") (name "unconnected-(J8-Pad9)") (class "Default")
      (node (ref "J8") (pin "9") (pinfunction "9_9") (pintype "passive"))
    )
    (net (code "127") (name "unconnected-(J8-Pad11)") (class "Default")
      (node (ref "J8") (pin "11") (pinfunction "11_11") (pintype "passive"))
    )
    (net (code "128") (name "unconnected-(J8-Pad13)") (class "Default")
      (node (ref "J8") (pin "13") (pinfunction "13_13") (pintype "passive"))
    )
    (net (code "129") (name "unconnected-(J8-Pad15)") (class "Default")
      (node (ref "J8") (pin "15") (pinfunction "15_15") (pintype "passive"))
    )
    (net (code "130") (name "unconnected-(U1-1_NC-Pad2)") (class "Default")
      (node (ref "U1") (pin "2") (pinfunction "1_NC_2") (pintype "passive"))
    )
    (net (code "131") (name "unconnected-(U1-2_NC-Pad4)") (class "Default")
      (node (ref "U1") (pin "4") (pinfunction "2_NC_4") (pintype "passive"))
    )
    (net (code "132") (name "unconnected-(U2-1_NC-Pad2)") (class "Default")
      (node (ref "U2") (pin "2") (pinfunction "1_NC_2") (pintype "passive"))
    )
    (net (code "133") (name "unconnected-(U2-2_NC-Pad4)") (class "Default")
      (node (ref "U2") (pin "4") (pinfunction "2_NC_4") (pintype "passive"))
    )
    (net (code "134") (name "unconnected-(U3-1_NC-Pad2)") (class "Default")
      (node (ref "U3") (pin "2") (pinfunction "1_NC_2") (pintype "passive"))
    )
    (net (code "135") (name "unconnected-(U3-2_NC-Pad4)") (class "Default")
      (node (ref "U3") (pin "4") (pinfunction "2_NC_4") (pintype "passive"))
    )
    (net (code "136") (name "unconnected-(U4-1_NC-Pad2)") (class "Default")
      (node (ref "U4") (pin "2") (pinfunction "1_NC_2") (pintype "passive"))
    )
    (net (code "137") (name "unconnected-(U4-2_NC-Pad4)") (class "Default")
      (node (ref "U4") (pin "4") (pinfunction "2_NC_4") (pintype "passive"))
    )
    (net (code "138") (name "unconnected-(U6-1_NC-Pad2)") (class "Default")
      (node (ref "U6") (pin "2") (pinfunction "1_NC_2") (pintype "passive"))
    )
    (net (code "139") (name "unconnected-(U6-2_NC-Pad4)") (class "Default")
      (node (ref "U6") (pin "4") (pinfunction "2_NC_4") (pintype "passive"))
    )
    (net (code "140") (name "unconnected-(U9-1_NC-Pad2)") (class "Default")
      (node (ref "U9") (pin "2") (pinfunction "1_NC_2") (pintype "passive"))
    )
    (net (code "141") (name "unconnected-(U9-2_NC-Pad4)") (class "Default")
      (node (ref "U9") (pin "4") (pinfunction "2_NC_4") (pintype "passive"))
    )
    (net (code "142") (name "unconnected-(U10-1_NC-Pad2)") (class "Default")
      (node (ref "U10") (pin "2") (pinfunction "1_NC_2") (pintype "passive"))
    )
    (net (code "143") (name "unconnected-(U10-2_NC-Pad4)") (class "Default")
      (node (ref "U10") (pin "4") (pinfunction "2_NC_4") (pintype "passive"))
    )
    (net (code "144") (name "unconnected-(U11-1_NC-Pad2)") (class "Default")
      (node (ref "U11") (pin "2") (pinfunction "1_NC_2") (pintype "passive"))
    )
    (net (code "145") (name "unconnected-(U11-2_NC-Pad4)") (class "Default")
      (node (ref "U11") (pin "4") (pinfunction "2_NC_4") (pintype "passive"))
    )
    (net (code "146") (name "unconnected-(U11-2_SIGNAL_TERMINAL-Pad3)") (class "Default")
      (node (ref "U11") (pin "3") (pinfunction "2_SIGNAL_TERMINAL_3") (pintype "passive"))
    )
    (net (code "147") (name "unconnected-(U12-1_NC-Pad2)") (class "Default")
      (node (ref "U12") (pin "2") (pinfunction "1_NC_2") (pintype "passive"))
    )
    (net (code "148") (name "unconnected-(U12-2_NC-Pad4)") (class "Default")
      (node (ref "U12") (pin "4") (pinfunction "2_NC_4") (pintype "passive"))
    )
    (net (code "149") (name "unconnected-(U13-1_NC-Pad2)") (class "Default")
      (node (ref "U13") (pin "2") (pinfunction "1_NC_2") (pintype "passive"))
    )
    (net (code "150") (name "unconnected-(U13-2_NC-Pad4)") (class "Default")
      (node (ref "U13") (pin "4") (pinfunction "2_NC_4") (pintype "passive"))
    )
    (net (code "151") (name "unconnected-(U14-1_NC-Pad2)") (class "Default")
      (node (ref "U14") (pin "2") (pinfunction "1_NC_2") (pintype "passive"))
    )
    (net (code "152") (name "unconnected-(U14-2_NC-Pad4)") (class "Default")
      (node (ref "U14") (pin "4") (pinfunction "2_NC_4") (pintype "passive"))
    )
    (net (code "153") (name "unconnected-(U15-1_NC-Pad2)") (class "Default")
      (node (ref "U15") (pin "2") (pinfunction "1_NC_2") (pintype "passive"))
    )
    (net (code "154") (name "unconnected-(U15-2_NC-Pad4)") (class "Default")
      (node (ref "U15") (pin "4") (pinfunction "2_NC_4") (pintype "passive"))
    )
    (net (code "155") (name "unconnected-(U16-1_NC-Pad2)") (class "Default")
      (node (ref "U16") (pin "2") (pinfunction "1_NC_2") (pintype "passive"))
    )
    (net (code "156") (name "unconnected-(U16-2_NC-Pad4)") (class "Default")
      (node (ref "U16") (pin "4") (pinfunction "2_NC_4") (pintype "passive"))
    )
    (net (code "157") (name "unconnected-(U21-1_NC-Pad2)") (class "Default")
      (node (ref "U21") (pin "2") (pinfunction "1_NC_2") (pintype "passive"))
    )
    (net (code "158") (name "unconnected-(U21-2_NC-Pad4)") (class "Default")
      (node (ref "U21") (pin "4") (pinfunction "2_NC_4") (pintype "passive"))
    )
    (net (code "159") (name "unconnected-(U22-1_NC-Pad2)") (class "Default")
      (node (ref "U22") (pin "2") (pinfunction "1_NC_2") (pintype "passive"))
    )
    (net (code "160") (name "unconnected-(U22-2_NC-Pad4)") (class "Default")
      (node (ref "U22") (pin "4") (pinfunction "2_NC_4") (pintype "passive"))
    )
    (net (code "161") (name "unconnected-(U23-1_NC-Pad2)") (class "Default")
      (node (ref "U23") (pin "2") (pinfunction "1_NC_2") (pintype "passive"))
    )
    (net (code "162") (name "unconnected-(U23-2_NC-Pad4)") (class "Default")
      (node (ref "U23") (pin "4") (pinfunction "2_NC_4") (pintype "passive"))
    )
    (net (code "163") (name "unconnected-(U24-1_NC-Pad2)") (class "Default")
      (node (ref "U24") (pin "2") (pinfunction "1_NC_2") (pintype "passive"))
    )
    (net (code "164") (name "unconnected-(U24-2_NC-Pad4)") (class "Default")
      (node (ref "U24") (pin "4") (pinfunction "2_NC_4") (pintype "passive"))
    )
    (net (code "165") (name "unconnected-(U25-1_NC-Pad2)") (class "Default")
      (node (ref "U25") (pin "2") (pinfunction "1_NC_2") (pintype "passive"))
    )
    (net (code "166") (name "unconnected-(U25-2_NC-Pad4)") (class "Default")
      (node (ref "U25") (pin "4") (pinfunction "2_NC_4") (pintype "passive"))
    )
    (net (code "167") (name "unconnected-(U26-1_NC-Pad2)") (class "Default")
      (node (ref "U26") (pin "2") (pinfunction "1_NC_2") (pintype "passive"))
    )
    (net (code "168") (name "unconnected-(U26-2_NC-Pad4)") (class "Default")
      (node (ref "U26") (pin "4") (pinfunction "2_NC_4") (pintype "passive"))
    )
    (net (code "169") (name "unconnected-(U27-1_NC-Pad2)") (class "Default")
      (node (ref "U27") (pin "2") (pinfunction "1_NC_2") (pintype "passive"))
    )
    (net (code "170") (name "unconnected-(U27-2_NC-Pad4)") (class "Default")
      (node (ref "U27") (pin "4") (pinfunction "2_NC_4") (pintype "passive"))
    )
    (net (code "171") (name "unconnected-(U28-1_NC-Pad2)") (class "Default")
      (node (ref "U28") (pin "2") (pinfunction "1_NC_2") (pintype "passive"))
    )
    (net (code "172") (name "unconnected-(U28-2_NC-Pad4)") (class "Default")
      (node (ref "U28") (pin "4") (pinfunction "2_NC_4") (pintype "passive"))
    )
    (net (code "173") (name "unconnected-(U29-1_NC-Pad2)") (class "Default")
      (node (ref "U29") (pin "2") (pinfunction "1_NC_2") (pintype "passive"))
    )
    (net (code "174") (name "unconnected-(U29-2_NC-Pad4)") (class "Default")
      (node (ref "U29") (pin "4") (pinfunction "2_NC_4") (pintype "passive"))
    )
    (net (code "175") (name "unconnected-(U30-1_NC-Pad2)") (class "Default")
      (node (ref "U30") (pin "2") (pinfunction "1_NC_2") (pintype "passive"))
    )
    (net (code "176") (name "unconnected-(U30-2_NC-Pad4)") (class "Default")
      (node (ref "U30") (pin "4") (pinfunction "2_NC_4") (pintype "passive"))
    )
    (net (code "177") (name "unconnected-(U31-1_NC-Pad2)") (class "Default")
      (node (ref "U31") (pin "2") (pinfunction "1_NC_2") (pintype "passive"))
    )
    (net (code "178") (name "unconnected-(U31-2_NC-Pad4)") (class "Default")
      (node (ref "U31") (pin "4") (pinfunction "2_NC_4") (pintype "passive"))
    )
    (net (code "179") (name "unconnected-(U32-1_NC-Pad2)") (class "Default")
      (node (ref "U32") (pin "2") (pinfunction "1_NC_2") (pintype "passive"))
    )
    (net (code "180") (name "unconnected-(U32-2_NC-Pad4)") (class "Default")
      (node (ref "U32") (pin "4") (pinfunction "2_NC_4") (pintype "passive"))
    )
    (net (code "181") (name "unconnected-(U33-1_NC-Pad2)") (class "Default")
      (node (ref "U33") (pin "2") (pinfunction "1_NC_2") (pintype "passive"))
    )
    (net (code "182") (name "unconnected-(U33-2_NC-Pad4)") (class "Default")
      (node (ref "U33") (pin "4") (pinfunction "2_NC_4") (pintype "passive"))
    )
    (net (code "183") (name "unconnected-(U34-1_NC-Pad2)") (class "Default")
      (node (ref "U34") (pin "2") (pinfunction "1_NC_2") (pintype "passive"))
    )
    (net (code "184") (name "unconnected-(U34-2_NC-Pad4)") (class "Default")
      (node (ref "U34") (pin "4") (pinfunction "2_NC_4") (pintype "passive"))
    )
    (net (code "185") (name "unconnected-(U35-1_NC-Pad2)") (class "Default")
      (node (ref "U35") (pin "2") (pinfunction "1_NC_2") (pintype "passive"))
    )
    (net (code "186") (name "unconnected-(U35-2_NC-Pad4)") (class "Default")
      (node (ref "U35") (pin "4") (pinfunction "2_NC_4") (pintype "passive"))
    )
    (net (code "187") (name "unconnected-(U36-1_NC-Pad2)") (class "Default")
      (node (ref "U36") (pin "2") (pinfunction "1_NC_2") (pintype "passive"))
    )
    (net (code "188") (name "unconnected-(U36-2_NC-Pad4)") (class "Default")
      (node (ref "U36") (pin "4") (pinfunction "2_NC_4") (pintype "passive"))
    )
    (net (code "189") (name "unconnected-(U37-1_NC-Pad2)") (class "Default")
      (node (ref "U37") (pin "2") (pinfunction "1_NC_2") (pintype "passive"))
    )
    (net (code "190") (name "unconnected-(U37-2_NC-Pad4)") (class "Default")
      (node (ref "U37") (pin "4") (pinfunction "2_NC_4") (pintype "passive"))
    )
    (net (code "191") (name "unconnected-(U38-1_NC-Pad2)") (class "Default")
      (node (ref "U38") (pin "2") (pinfunction "1_NC_2") (pintype "passive"))
    )
    (net (code "192") (name "unconnected-(U38-2_NC-Pad4)") (class "Default")
      (node (ref "U38") (pin "4") (pinfunction "2_NC_4") (pintype "passive"))
    )
    (net (code "193") (name "unconnected-(U39-1_NC-Pad2)") (class "Default")
      (node (ref "U39") (pin "2") (pinfunction "1_NC_2") (pintype "passive"))
    )
    (net (code "194") (name "unconnected-(U39-2_NC-Pad4)") (class "Default")
      (node (ref "U39") (pin "4") (pinfunction "2_NC_4") (pintype "passive"))
    )
    (net (code "195") (name "unconnected-(U40-1_NC-Pad2)") (class "Default")
      (node (ref "U40") (pin "2") (pinfunction "1_NC_2") (pintype "passive"))
    )
    (net (code "196") (name "unconnected-(U40-2_NC-Pad4)") (class "Default")
      (node (ref "U40") (pin "4") (pinfunction "2_NC_4") (pintype "passive"))
    )
    (net (code "197") (name "unconnected-(U41-1_NC-Pad2)") (class "Default")
      (node (ref "U41") (pin "2") (pinfunction "1_NC_2") (pintype "passive"))
    )
    (net (code "198") (name "unconnected-(U41-2_NC-Pad4)") (class "Default")
      (node (ref "U41") (pin "4") (pinfunction "2_NC_4") (pintype "passive"))
    )
    (net (code "199") (name "unconnected-(U42-1_NC-Pad2)") (class "Default")
      (node (ref "U42") (pin "2") (pinfunction "1_NC_2") (pintype "passive"))
    )
    (net (code "200") (name "unconnected-(U42-2_NC-Pad4)") (class "Default")
      (node (ref "U42") (pin "4") (pinfunction "2_NC_4") (pintype "passive"))
    )
    (net (code "201") (name "unconnected-(U43-1_NC-Pad2)") (class "Default")
      (node (ref "U43") (pin "2") (pinfunction "1_NC_2") (pintype "passive"))
    )
    (net (code "202") (name "unconnected-(U43-2_NC-Pad4)") (class "Default")
      (node (ref "U43") (pin "4") (pinfunction "2_NC_4") (pintype "passive"))
    )
    (net (code "203") (name "unconnected-(U44-1_NC-Pad2)") (class "Default")
      (node (ref "U44") (pin "2") (pinfunction "1_NC_2") (pintype "passive"))
    )
    (net (code "204") (name "unconnected-(U44-2_NC-Pad4)") (class "Default")
      (node (ref "U44") (pin "4") (pinfunction "2_NC_4") (pintype "passive"))
    )
    (net (code "205") (name "unconnected-(U45-1_NC-Pad2)") (class "Default")
      (node (ref "U45") (pin "2") (pinfunction "1_NC_2") (pintype "passive"))
    )
    (net (code "206") (name "unconnected-(U45-2_NC-Pad4)") (class "Default")
      (node (ref "U45") (pin "4") (pinfunction "2_NC_4") (pintype "passive"))
    )
    (net (code "207") (name "unconnected-(U46-1_NC-Pad2)") (class "Default")
      (node (ref "U46") (pin "2") (pinfunction "1_NC_2") (pintype "passive"))
    )
    (net (code "208") (name "unconnected-(U46-2_NC-Pad4)") (class "Default")
      (node (ref "U46") (pin "4") (pinfunction "2_NC_4") (pintype "passive"))
    )
    (net (code "209") (name "unconnected-(U47-1_NC-Pad2)") (class "Default")
      (node (ref "U47") (pin "2") (pinfunction "1_NC_2") (pintype "passive"))
    )
    (net (code "210") (name "unconnected-(U47-2_NC-Pad4)") (class "Default")
      (node (ref "U47") (pin "4") (pinfunction "2_NC_4") (pintype "passive"))
    )
    (net (code "211") (name "unconnected-(U48-1_NC-Pad2)") (class "Default")
      (node (ref "U48") (pin "2") (pinfunction "1_NC_2") (pintype "passive"))
    )
    (net (code "212") (name "unconnected-(U48-2_NC-Pad4)") (class "Default")
      (node (ref "U48") (pin "4") (pinfunction "2_NC_4") (pintype "passive"))
    )
    (net (code "213") (name "unconnected-(U49-1_NC-Pad2)") (class "Default")
      (node (ref "U49") (pin "2") (pinfunction "1_NC_2") (pintype "passive"))
    )
    (net (code "214") (name "unconnected-(U49-2_NC-Pad4)") (class "Default")
      (node (ref "U49") (pin "4") (pinfunction "2_NC_4") (pintype "passive"))
    )
    (net (code "215") (name "unconnected-(U50-1_NC-Pad2)") (class "Default")
      (node (ref "U50") (pin "2") (pinfunction "1_NC_2") (pintype "passive"))
    )
    (net (code "216") (name "unconnected-(U50-2_NC-Pad4)") (class "Default")
      (node (ref "U50") (pin "4") (pinfunction "2_NC_4") (pintype "passive"))
    )
    (net (code "217") (name "unconnected-(U51-1_NC-Pad2)") (class "Default")
      (node (ref "U51") (pin "2") (pinfunction "1_NC_2") (pintype "passive"))
    )
    (net (code "218") (name "unconnected-(U51-2_NC-Pad4)") (class "Default")
      (node (ref "U51") (pin "4") (pinfunction "2_NC_4") (pintype "passive"))
    )
    (net (code "219") (name "unconnected-(U52-1_NC-Pad2)") (class "Default")
      (node (ref "U52") (pin "2") (pinfunction "1_NC_2") (pintype "passive"))
    )
    (net (code "220") (name "unconnected-(U52-2_NC-Pad4)") (class "Default")
      (node (ref "U52") (pin "4") (pinfunction "2_NC_4") (pintype "passive"))
    )
    (net (code "221") (name "unconnected-(U53-1_NC-Pad2)") (class "Default")
      (node (ref "U53") (pin "2") (pinfunction "1_NC_2") (pintype "passive"))
    )
    (net (code "222") (name "unconnected-(U53-2_NC-Pad4)") (class "Default")
      (node (ref "U53") (pin "4") (pinfunction "2_NC_4") (pintype "passive"))
    )
    (net (code "223") (name "unconnected-(U54-1_NC-Pad2)") (class "Default")
      (node (ref "U54") (pin "2") (pinfunction "1_NC_2") (pintype "passive"))
    )
    (net (code "224") (name "unconnected-(U54-2_NC-Pad4)") (class "Default")
      (node (ref "U54") (pin "4") (pinfunction "2_NC_4") (pintype "passive"))
    )
    (net (code "225") (name "unconnected-(U55-1_NC-Pad2)") (class "Default")
      (node (ref "U55") (pin "2") (pinfunction "1_NC_2") (pintype "passive"))
    )
    (net (code "226") (name "unconnected-(U55-2_NC-Pad4)") (class "Default")
      (node (ref "U55") (pin "4") (pinfunction "2_NC_4") (pintype "passive"))
    )
    (net (code "227") (name "unconnected-(U56-1_NC-Pad2)") (class "Default")
      (node (ref "U56") (pin "2") (pinfunction "1_NC_2") (pintype "passive"))
    )
    (net (code "228") (name "unconnected-(U56-2_NC-Pad4)") (class "Default")
      (node (ref "U56") (pin "4") (pinfunction "2_NC_4") (pintype "passive"))
    )
    (net (code "229") (name "unconnected-(U57-1_NC-Pad2)") (class "Default")
      (node (ref "U57") (pin "2") (pinfunction "1_NC_2") (pintype "passive"))
    )
    (net (code "230") (name "unconnected-(U57-2_NC-Pad4)") (class "Default")
      (node (ref "U57") (pin "4") (pinfunction "2_NC_4") (pintype "passive"))
    )
    (net (code "231") (name "unconnected-(U58-1_NC-Pad2)") (class "Default")
      (node (ref "U58") (pin "2") (pinfunction "1_NC_2") (pintype "passive"))
    )
    (net (code "232") (name "unconnected-(U58-2_NC-Pad4)") (class "Default")
      (node (ref "U58") (pin "4") (pinfunction "2_NC_4") (pintype "passive"))
    )
    (net (code "233") (name "unconnected-(U59-1_NC-Pad2)") (class "Default")
      (node (ref "U59") (pin "2") (pinfunction "1_NC_2") (pintype "passive"))
    )
    (net (code "234") (name "unconnected-(U59-2_NC-Pad4)") (class "Default")
      (node (ref "U59") (pin "4") (pinfunction "2_NC_4") (pintype "passive"))
    )
    (net (code "235") (name "unconnected-(U60-1_NC-Pad2)") (class "Default")
      (node (ref "U60") (pin "2") (pinfunction "1_NC_2") (pintype "passive"))
    )
    (net (code "236") (name "unconnected-(U60-2_NC-Pad4)") (class "Default")
      (node (ref "U60") (pin "4") (pinfunction "2_NC_4") (pintype "passive"))
    )
    (net (code "237") (name "unconnected-(U61-1_NC-Pad2)") (class "Default")
      (node (ref "U61") (pin "2") (pinfunction "1_NC_2") (pintype "passive"))
    )
    (net (code "238") (name "unconnected-(U61-2_NC-Pad4)") (class "Default")
      (node (ref "U61") (pin "4") (pinfunction "2_NC_4") (pintype "passive"))
    )
    (net (code "239") (name "unconnected-(U62-1_NC-Pad2)") (class "Default")
      (node (ref "U62") (pin "2") (pinfunction "1_NC_2") (pintype "passive"))
    )
    (net (code "240") (name "unconnected-(U62-2_NC-Pad4)") (class "Default")
      (node (ref "U62") (pin "4") (pinfunction "2_NC_4") (pintype "passive"))
    )
    (net (code "241") (name "unconnected-(U63-1_NC-Pad2)") (class "Default")
      (node (ref "U63") (pin "2") (pinfunction "1_NC_2") (pintype "passive"))
    )
    (net (code "242") (name "unconnected-(U63-2_NC-Pad4)") (class "Default")
      (node (ref "U63") (pin "4") (pinfunction "2_NC_4") (pintype "passive"))
    )
    (net (code "243") (name "unconnected-(U64-1_NC-Pad2)") (class "Default")
      (node (ref "U64") (pin "2") (pinfunction "1_NC_2") (pintype "passive"))
    )
    (net (code "244") (name "unconnected-(U64-2_NC-Pad4)") (class "Default")
      (node (ref "U64") (pin "4") (pinfunction "2_NC_4") (pintype "passive"))
    )
    (net (code "245") (name "unconnected-(U65-1_NC-Pad2)") (class "Default")
      (node (ref "U65") (pin "2") (pinfunction "1_NC_2") (pintype "passive"))
    )
    (net (code "246") (name "unconnected-(U65-2_NC-Pad4)") (class "Default")
      (node (ref "U65") (pin "4") (pinfunction "2_NC_4") (pintype "passive"))
    )
    (net (code "247") (name "unconnected-(U66-1_NC-Pad2)") (class "Default")
      (node (ref "U66") (pin "2") (pinfunction "1_NC_2") (pintype "passive"))
    )
    (net (code "248") (name "unconnected-(U66-2_NC-Pad4)") (class "Default")
      (node (ref "U66") (pin "4") (pinfunction "2_NC_4") (pintype "passive"))
    )
    (net (code "249") (name "unconnected-(U67-1_NC-Pad2)") (class "Default")
      (node (ref "U67") (pin "2") (pinfunction "1_NC_2") (pintype "passive"))
    )
    (net (code "250") (name "unconnected-(U67-2_NC-Pad4)") (class "Default")
      (node (ref "U67") (pin "4") (pinfunction "2_NC_4") (pintype "passive"))
    )
    (net (code "251") (name "unconnected-(U68-1_NC-Pad2)") (class "Default")
      (node (ref "U68") (pin "2") (pinfunction "1_NC_2") (pintype "passive"))
    )
    (net (code "252") (name "unconnected-(U68-2_NC-Pad4)") (class "Default")
      (node (ref "U68") (pin "4") (pinfunction "2_NC_4") (pintype "passive"))
    )
    (net (code "253") (name "unconnected-(U69-1_NC-Pad2)") (class "Default")
      (node (ref "U69") (pin "2") (pinfunction "1_NC_2") (pintype "passive"))
    )
    (net (code "254") (name "unconnected-(U69-2_NC-Pad4)") (class "Default")
      (node (ref "U69") (pin "4") (pinfunction "2_NC_4") (pintype "passive"))
    )
    (net (code "255") (name "unconnected-(U70-1_NC-Pad2)") (class "Default")
      (node (ref "U70") (pin "2") (pinfunction "1_NC_2") (pintype "passive"))
    )
    (net (code "256") (name "unconnected-(U70-2_NC-Pad4)") (class "Default")
      (node (ref "U70") (pin "4") (pinfunction "2_NC_4") (pintype "passive"))
    )
    (net (code "257") (name "unconnected-(U71-1_NC-Pad2)") (class "Default")
      (node (ref "U71") (pin "2") (pinfunction "1_NC_2") (pintype "passive"))
    )
    (net (code "258") (name "unconnected-(U71-2_NC-Pad4)") (class "Default")
      (node (ref "U71") (pin "4") (pinfunction "2_NC_4") (pintype "passive"))
    )
    (net (code "259") (name "unconnected-(U72-1_NC-Pad2)") (class "Default")
      (node (ref "U72") (pin "2") (pinfunction "1_NC_2") (pintype "passive"))
    )
    (net (code "260") (name "unconnected-(U72-2_NC-Pad4)") (class "Default")
      (node (ref "U72") (pin "4") (pinfunction "2_NC_4") (pintype "passive"))
    )
    (net (code "261") (name "unconnected-(U73-1_NC-Pad2)") (class "Default")
      (node (ref "U73") (pin "2") (pinfunction "1_NC_2") (pintype "passive"))
    )
    (net (code "262") (name "unconnected-(U73-2_NC-Pad4)") (class "Default")
      (node (ref "U73") (pin "4") (pinfunction "2_NC_4") (pintype "passive"))
    )
    (net (code "263") (name "unconnected-(U74-1_NC-Pad2)") (class "Default")
      (node (ref "U74") (pin "2") (pinfunction "1_NC_2") (pintype "passive"))
    )
    (net (code "264") (name "unconnected-(U74-2_NC-Pad4)") (class "Default")
      (node (ref "U74") (pin "4") (pinfunction "2_NC_4") (pintype "passive"))
    )
    (net (code "265") (name "unconnected-(U75-1_NC-Pad2)") (class "Default")
      (node (ref "U75") (pin "2") (pinfunction "1_NC_2") (pintype "passive"))
    )
    (net (code "266") (name "unconnected-(U75-2_NC-Pad4)") (class "Default")
      (node (ref "U75") (pin "4") (pinfunction "2_NC_4") (pintype "passive"))
    )
    (net (code "267") (name "unconnected-(U76-1_NC-Pad2)") (class "Default")
      (node (ref "U76") (pin "2") (pinfunction "1_NC_2") (pintype "passive"))
    )
    (net (code "268") (name "unconnected-(U76-2_NC-Pad4)") (class "Default")
      (node (ref "U76") (pin "4") (pinfunction "2_NC_4") (pintype "passive"))
    )
    (net (code "269") (name "unconnected-(U77-1_NC-Pad2)") (class "Default")
      (node (ref "U77") (pin "2") (pinfunction "1_NC_2") (pintype "passive"))
    )
    (net (code "270") (name "unconnected-(U77-2_NC-Pad4)") (class "Default")
      (node (ref "U77") (pin "4") (pinfunction "2_NC_4") (pintype "passive"))
    )
    (net (code "271") (name "unconnected-(U78-1_NC-Pad2)") (class "Default")
      (node (ref "U78") (pin "2") (pinfunction "1_NC_2") (pintype "passive"))
    )
    (net (code "272") (name "unconnected-(U78-2_NC-Pad4)") (class "Default")
      (node (ref "U78") (pin "4") (pinfunction "2_NC_4") (pintype "passive"))
    )
    (net (code "273") (name "unconnected-(U79-1_NC-Pad2)") (class "Default")
      (node (ref "U79") (pin "2") (pinfunction "1_NC_2") (pintype "passive"))
    )
    (net (code "274") (name "unconnected-(U79-2_NC-Pad4)") (class "Default")
      (node (ref "U79") (pin "4") (pinfunction "2_NC_4") (pintype "passive"))
    )
    (net (code "275") (name "unconnected-(U80-1_NC-Pad2)") (class "Default")
      (node (ref "U80") (pin "2") (pinfunction "1_NC_2") (pintype "passive"))
    )
    (net (code "276") (name "unconnected-(U80-2_NC-Pad4)") (class "Default")
      (node (ref "U80") (pin "4") (pinfunction "2_NC_4") (pintype "passive"))
    )
    (net (code "277") (name "unconnected-(U90-1_NC-Pad2)") (class "Default")
      (node (ref "U90") (pin "2") (pinfunction "1_NC_2") (pintype "passive"))
    )
    (net (code "278") (name "unconnected-(U90-2_NC-Pad4)") (class "Default")
      (node (ref "U90") (pin "4") (pinfunction "2_NC_4") (pintype "passive"))
    )
    (net (code "279") (name "unconnected-(U91-1_NC-Pad2)") (class "Default")
      (node (ref "U91") (pin "2") (pinfunction "1_NC_2") (pintype "passive"))
    )
    (net (code "280") (name "unconnected-(U91-2_NC-Pad4)") (class "Default")
      (node (ref "U91") (pin "4") (pinfunction "2_NC_4") (pintype "passive"))
    )
    (net (code "281") (name "unconnected-(U92-1_NC-Pad2)") (class "Default")
      (node (ref "U92") (pin "2") (pinfunction "1_NC_2") (pintype "passive"))
    )
    (net (code "282") (name "unconnected-(U92-2_NC-Pad4)") (class "Default")
      (node (ref "U92") (pin "4") (pinfunction "2_NC_4") (pintype "passive"))
    )
    (net (code "283") (name "unconnected-(U93-1_NC-Pad2)") (class "Default")
      (node (ref "U93") (pin "2") (pinfunction "1_NC_2") (pintype "passive"))
    )
    (net (code "284") (name "unconnected-(U93-2_NC-Pad4)") (class "Default")
      (node (ref "U93") (pin "4") (pinfunction "2_NC_4") (pintype "passive"))
    )
    (net (code "285") (name "unconnected-(U94-1_NC-Pad2)") (class "Default")
      (node (ref "U94") (pin "2") (pinfunction "1_NC_2") (pintype "passive"))
    )
    (net (code "286") (name "unconnected-(U94-2_NC-Pad4)") (class "Default")
      (node (ref "U94") (pin "4") (pinfunction "2_NC_4") (pintype "passive"))
    )
    (net (code "287") (name "unconnected-(U95-1_NC-Pad2)") (class "Default")
      (node (ref "U95") (pin "2") (pinfunction "1_NC_2") (pintype "passive"))
    )
    (net (code "288") (name "unconnected-(U95-2_NC-Pad4)") (class "Default")
      (node (ref "U95") (pin "4") (pinfunction "2_NC_4") (pintype "passive"))
    )
    (net (code "289") (name "unconnected-(U96-1_NC-Pad2)") (class "Default")
      (node (ref "U96") (pin "2") (pinfunction "1_NC_2") (pintype "passive"))
    )
    (net (code "290") (name "unconnected-(U96-2_NC-Pad4)") (class "Default")
      (node (ref "U96") (pin "4") (pinfunction "2_NC_4") (pintype "passive"))
    )
    (net (code "291") (name "unconnected-(U97-1_NC-Pad2)") (class "Default")
      (node (ref "U97") (pin "2") (pinfunction "1_NC_2") (pintype "passive"))
    )
    (net (code "292") (name "unconnected-(U97-2_NC-Pad4)") (class "Default")
      (node (ref "U97") (pin "4") (pinfunction "2_NC_4") (pintype "passive"))
    )
    (net (code "293") (name "unconnected-(U98-1_NC-Pad2)") (class "Default")
      (node (ref "U98") (pin "2") (pinfunction "1_NC_2") (pintype "passive"))
    )
    (net (code "294") (name "unconnected-(U98-2_NC-Pad4)") (class "Default")
      (node (ref "U98") (pin "4") (pinfunction "2_NC_4") (pintype "passive"))
    )
    (net (code "295") (name "unconnected-(U99-1_NC-Pad2)") (class "Default")
      (node (ref "U99") (pin "2") (pinfunction "1_NC_2") (pintype "passive"))
    )
    (net (code "296") (name "unconnected-(U99-2_NC-Pad4)") (class "Default")
      (node (ref "U99") (pin "4") (pinfunction "2_NC_4") (pintype "passive"))
    )
    (net (code "297") (name "unconnected-(U100-1_NC-Pad2)") (class "Default")
      (node (ref "U100") (pin "2") (pinfunction "1_NC_2") (pintype "passive"))
    )
    (net (code "298") (name "unconnected-(U100-2_NC-Pad4)") (class "Default")
      (node (ref "U100") (pin "4") (pinfunction "2_NC_4") (pintype "passive"))
    )
    (net (code "299") (name "unconnected-(U101-1_NC-Pad2)") (class "Default")
      (node (ref "U101") (pin "2") (pinfunction "1_NC_2") (pintype "passive"))
    )
    (net (code "300") (name "unconnected-(U101-2_NC-Pad4)") (class "Default")
      (node (ref "U101") (pin "4") (pinfunction "2_NC_4") (pintype "passive"))
    )
    (net (code "301") (name "unconnected-(U102-1_NC-Pad2)") (class "Default")
      (node (ref "U102") (pin "2") (pinfunction "1_NC_2") (pintype "passive"))
    )
    (net (code "302") (name "unconnected-(U102-2_NC-Pad4)") (class "Default")
      (node (ref "U102") (pin "4") (pinfunction "2_NC_4") (pintype "passive"))
    )
    (net (code "303") (name "unconnected-(U103-1_NC-Pad2)") (class "Default")
      (node (ref "U103") (pin "2") (pinfunction "1_NC_2") (pintype "passive"))
    )
    (net (code "304") (name "unconnected-(U103-2_NC-Pad4)") (class "Default")
      (node (ref "U103") (pin "4") (pinfunction "2_NC_4") (pintype "passive"))
    )
    (net (code "305") (name "unconnected-(U104-1_NC-Pad2)") (class "Default")
      (node (ref "U104") (pin "2") (pinfunction "1_NC_2") (pintype "passive"))
    )
    (net (code "306") (name "unconnected-(U104-2_NC-Pad4)") (class "Default")
      (node (ref "U104") (pin "4") (pinfunction "2_NC_4") (pintype "passive"))
    )
    (net (code "307") (name "unconnected-(U105-1_NC-Pad2)") (class "Default")
      (node (ref "U105") (pin "2") (pinfunction "1_NC_2") (pintype "passive"))
    )
    (net (code "308") (name "unconnected-(U105-2_NC-Pad4)") (class "Default")
      (node (ref "U105") (pin "4") (pinfunction "2_NC_4") (pintype "passive"))
    )
    (net (code "309") (name "unconnected-(U106-1_NC-Pad2)") (class "Default")
      (node (ref "U106") (pin "2") (pinfunction "1_NC_2") (pintype "passive"))
    )
    (net (code "310") (name "unconnected-(U106-2_NC-Pad4)") (class "Default")
      (node (ref "U106") (pin "4") (pinfunction "2_NC_4") (pintype "passive"))
    )
    (net (code "311") (name "unconnected-(U107-1_NC-Pad2)") (class "Default")
      (node (ref "U107") (pin "2") (pinfunction "1_NC_2") (pintype "passive"))
    )
    (net (code "312") (name "unconnected-(U107-2_NC-Pad4)") (class "Default")
      (node (ref "U107") (pin "4") (pinfunction "2_NC_4") (pintype "passive"))
    )
    (net (code "313") (name "unconnected-(U108-1_NC-Pad2)") (class "Default")
      (node (ref "U108") (pin "2") (pinfunction "1_NC_2") (pintype "passive"))
    )
    (net (code "314") (name "unconnected-(U108-2_NC-Pad4)") (class "Default")
      (node (ref "U108") (pin "4") (pinfunction "2_NC_4") (pintype "passive"))
    )
    (net (code "315") (name "unconnected-(U109-1_NC-Pad2)") (class "Default")
      (node (ref "U109") (pin "2") (pinfunction "1_NC_2") (pintype "passive"))
    )
    (net (code "316") (name "unconnected-(U109-2_NC-Pad4)") (class "Default")
      (node (ref "U109") (pin "4") (pinfunction "2_NC_4") (pintype "passive"))
    )
    (net (code "317") (name "unconnected-(U110-1_NC-Pad2)") (class "Default")
      (node (ref "U110") (pin "2") (pinfunction "1_NC_2") (pintype "passive"))
    )
    (net (code "318") (name "unconnected-(U110-2_NC-Pad4)") (class "Default")
      (node (ref "U110") (pin "4") (pinfunction "2_NC_4") (pintype "passive"))
    )
    (net (code "319") (name "unconnected-(U111-1_NC-Pad2)") (class "Default")
      (node (ref "U111") (pin "2") (pinfunction "1_NC_2") (pintype "passive"))
    )
    (net (code "320") (name "unconnected-(U111-2_NC-Pad4)") (class "Default")
      (node (ref "U111") (pin "4") (pinfunction "2_NC_4") (pintype "passive"))
    )
    (net (code "321") (name "unconnected-(U112-1_NC-Pad2)") (class "Default")
      (node (ref "U112") (pin "2") (pinfunction "1_NC_2") (pintype "passive"))
    )
    (net (code "322") (name "unconnected-(U112-2_NC-Pad4)") (class "Default")
      (node (ref "U112") (pin "4") (pinfunction "2_NC_4") (pintype "passive"))
    )
    (net (code "323") (name "unconnected-(U113-1_NC-Pad2)") (class "Default")
      (node (ref "U113") (pin "2") (pinfunction "1_NC_2") (pintype "passive"))
    )
    (net (code "324") (name "unconnected-(U113-2_NC-Pad4)") (class "Default")
      (node (ref "U113") (pin "4") (pinfunction "2_NC_4") (pintype "passive"))
    )
    (net (code "325") (name "unconnected-(U114-1_NC-Pad2)") (class "Default")
      (node (ref "U114") (pin "2") (pinfunction "1_NC_2") (pintype "passive"))
    )
    (net (code "326") (name "unconnected-(U114-2_NC-Pad4)") (class "Default")
      (node (ref "U114") (pin "4") (pinfunction "2_NC_4") (pintype "passive"))
    )
    (net (code "327") (name "unconnected-(U115-1_NC-Pad2)") (class "Default")
      (node (ref "U115") (pin "2") (pinfunction "1_NC_2") (pintype "passive"))
    )
    (net (code "328") (name "unconnected-(U115-2_NC-Pad4)") (class "Default")
      (node (ref "U115") (pin "4") (pinfunction "2_NC_4") (pintype "passive"))
    )
    (net (code "329") (name "unconnected-(U116-1_NC-Pad2)") (class "Default")
      (node (ref "U116") (pin "2") (pinfunction "1_NC_2") (pintype "passive"))
    )
    (net (code "330") (name "unconnected-(U116-2_NC-Pad4)") (class "Default")
      (node (ref "U116") (pin "4") (pinfunction "2_NC_4") (pintype "passive"))
    )
    (net (code "331") (name "unconnected-(U117-1_NC-Pad2)") (class "Default")
      (node (ref "U117") (pin "2") (pinfunction "1_NC_2") (pintype "passive"))
    )
    (net (code "332") (name "unconnected-(U117-2_NC-Pad4)") (class "Default")
      (node (ref "U117") (pin "4") (pinfunction "2_NC_4") (pintype "passive"))
    )
    (net (code "333") (name "unconnected-(U118-1_NC-Pad2)") (class "Default")
      (node (ref "U118") (pin "2") (pinfunction "1_NC_2") (pintype "passive"))
    )
    (net (code "334") (name "unconnected-(U118-2_NC-Pad4)") (class "Default")
      (node (ref "U118") (pin "4") (pinfunction "2_NC_4") (pintype "passive"))
    )
    (net (code "335") (name "unconnected-(U119-1_NC-Pad2)") (class "Default")
      (node (ref "U119") (pin "2") (pinfunction "1_NC_2") (pintype "passive"))
    )
    (net (code "336") (name "unconnected-(U119-2_NC-Pad4)") (class "Default")
      (node (ref "U119") (pin "4") (pinfunction "2_NC_4") (pintype "passive"))
    )
    (net (code "337") (name "unconnected-(U120-1_NC-Pad2)") (class "Default")
      (node (ref "U120") (pin "2") (pinfunction "1_NC_2") (pintype "passive"))
    )
    (net (code "338") (name "unconnected-(U120-2_NC-Pad4)") (class "Default")
      (node (ref "U120") (pin "4") (pinfunction "2_NC_4") (pintype "passive"))
    )
    (net (code "339") (name "unconnected-(U121-1_NC-Pad2)") (class "Default")
      (node (ref "U121") (pin "2") (pinfunction "1_NC_2") (pintype "passive"))
    )
    (net (code "340") (name "unconnected-(U121-2_NC-Pad4)") (class "Default")
      (node (ref "U121") (pin "4") (pinfunction "2_NC_4") (pintype "passive"))
    )
    (net (code "341") (name "unconnected-(U122-1_NC-Pad2)") (class "Default")
      (node (ref "U122") (pin "2") (pinfunction "1_NC_2") (pintype "passive"))
    )
    (net (code "342") (name "unconnected-(U122-2_NC-Pad4)") (class "Default")
      (node (ref "U122") (pin "4") (pinfunction "2_NC_4") (pintype "passive"))
    )
    (net (code "343") (name "unconnected-(U123-1_NC-Pad2)") (class "Default")
      (node (ref "U123") (pin "2") (pinfunction "1_NC_2") (pintype "passive"))
    )
    (net (code "344") (name "unconnected-(U123-2_NC-Pad4)") (class "Default")
      (node (ref "U123") (pin "4") (pinfunction "2_NC_4") (pintype "passive"))
    )
    (net (code "345") (name "unconnected-(U124-1_NC-Pad2)") (class "Default")
      (node (ref "U124") (pin "2") (pinfunction "1_NC_2") (pintype "passive"))
    )
    (net (code "346") (name "unconnected-(U124-2_NC-Pad4)") (class "Default")
      (node (ref "U124") (pin "4") (pinfunction "2_NC_4") (pintype "passive"))
    )
    (net (code "347") (name "unconnected-(U125-1_NC-Pad2)") (class "Default")
      (node (ref "U125") (pin "2") (pinfunction "1_NC_2") (pintype "passive"))
    )
    (net (code "348") (name "unconnected-(U125-2_NC-Pad4)") (class "Default")
      (node (ref "U125") (pin "4") (pinfunction "2_NC_4") (pintype "passive"))
    )
    (net (code "349") (name "unconnected-(U126-1_NC-Pad2)") (class "Default")
      (node (ref "U126") (pin "2") (pinfunction "1_NC_2") (pintype "passive"))
    )
    (net (code "350") (name "unconnected-(U126-2_NC-Pad4)") (class "Default")
      (node (ref "U126") (pin "4") (pinfunction "2_NC_4") (pintype "passive"))
    )
    (net (code "351") (name "unconnected-(U127-1_NC-Pad2)") (class "Default")
      (node (ref "U127") (pin "2") (pinfunction "1_NC_2") (pintype "passive"))
    )
    (net (code "352") (name "unconnected-(U127-2_NC-Pad4)") (class "Default")
      (node (ref "U127") (pin "4") (pinfunction "2_NC_4") (pintype "passive"))
    )
    (net (code "353") (name "unconnected-(U128-1_NC-Pad2)") (class "Default")
      (node (ref "U128") (pin "2") (pinfunction "1_NC_2") (pintype "passive"))
    )
    (net (code "354") (name "unconnected-(U128-2_NC-Pad4)") (class "Default")
      (node (ref "U128") (pin "4") (pinfunction "2_NC_4") (pintype "passive"))
    )
    (net (code "355") (name "unconnected-(U129-1_NC-Pad2)") (class "Default")
      (node (ref "U129") (pin "2") (pinfunction "1_NC_2") (pintype "passive"))
    )
    (net (code "356") (name "unconnected-(U129-2_NC-Pad4)") (class "Default")
      (node (ref "U129") (pin "4") (pinfunction "2_NC_4") (pintype "passive"))
    )
    (net (code "357") (name "unconnected-(U130-1_NC-Pad2)") (class "Default")
      (node (ref "U130") (pin "2") (pinfunction "1_NC_2") (pintype "passive"))
    )
    (net (code "358") (name "unconnected-(U130-2_NC-Pad4)") (class "Default")
      (node (ref "U130") (pin "4") (pinfunction "2_NC_4") (pintype "passive"))
    )
    (net (code "359") (name "unconnected-(U131-1_NC-Pad2)") (class "Default")
      (node (ref "U131") (pin "2") (pinfunction "1_NC_2") (pintype "passive"))
    )
    (net (code "360") (name "unconnected-(U131-2_NC-Pad4)") (class "Default")
      (node (ref "U131") (pin "4") (pinfunction "2_NC_4") (pintype "passive"))
    )
    (net (code "361") (name "unconnected-(U132-1_NC-Pad2)") (class "Default")
      (node (ref "U132") (pin "2") (pinfunction "1_NC_2") (pintype "passive"))
    )
    (net (code "362") (name "unconnected-(U132-2_NC-Pad4)") (class "Default")
      (node (ref "U132") (pin "4") (pinfunction "2_NC_4") (pintype "passive"))
    )
    (net (code "363") (name "unconnected-(U133-1_NC-Pad2)") (class "Default")
      (node (ref "U133") (pin "2") (pinfunction "1_NC_2") (pintype "passive"))
    )
    (net (code "364") (name "unconnected-(U133-2_NC-Pad4)") (class "Default")
      (node (ref "U133") (pin "4") (pinfunction "2_NC_4") (pintype "passive"))
    )
    (net (code "365") (name "unconnected-(U134-1_NC-Pad2)") (class "Default")
      (node (ref "U134") (pin "2") (pinfunction "1_NC_2") (pintype "passive"))
    )
    (net (code "366") (name "unconnected-(U134-2_NC-Pad4)") (class "Default")
      (node (ref "U134") (pin "4") (pinfunction "2_NC_4") (pintype "passive"))
    )
    (net (code "367") (name "unconnected-(U135-1_NC-Pad2)") (class "Default")
      (node (ref "U135") (pin "2") (pinfunction "1_NC_2") (pintype "passive"))
    )
    (net (code "368") (name "unconnected-(U135-2_NC-Pad4)") (class "Default")
      (node (ref "U135") (pin "4") (pinfunction "2_NC_4") (pintype "passive"))
    )
    (net (code "369") (name "unconnected-(U136-1_NC-Pad2)") (class "Default")
      (node (ref "U136") (pin "2") (pinfunction "1_NC_2") (pintype "passive"))
    )
    (net (code "370") (name "unconnected-(U136-2_NC-Pad4)") (class "Default")
      (node (ref "U136") (pin "4") (pinfunction "2_NC_4") (pintype "passive"))
    )
    (net (code "371") (name "unconnected-(U137-1_NC-Pad2)") (class "Default")
      (node (ref "U137") (pin "2") (pinfunction "1_NC_2") (pintype "passive"))
    )
    (net (code "372") (name "unconnected-(U137-2_NC-Pad4)") (class "Default")
      (node (ref "U137") (pin "4") (pinfunction "2_NC_4") (pintype "passive"))
    )
    (net (code "373") (name "unconnected-(U138-1_NC-Pad2)") (class "Default")
      (node (ref "U138") (pin "2") (pinfunction "1_NC_2") (pintype "passive"))
    )
    (net (code "374") (name "unconnected-(U138-2_NC-Pad4)") (class "Default")
      (node (ref "U138") (pin "4") (pinfunction "2_NC_4") (pintype "passive"))
    )
    (net (code "375") (name "unconnected-(U139-1_NC-Pad2)") (class "Default")
      (node (ref "U139") (pin "2") (pinfunction "1_NC_2") (pintype "passive"))
    )
    (net (code "376") (name "unconnected-(U139-2_NC-Pad4)") (class "Default")
      (node (ref "U139") (pin "4") (pinfunction "2_NC_4") (pintype "passive"))
    )
    (net (code "377") (name "unconnected-(U140-1_NC-Pad2)") (class "Default")
      (node (ref "U140") (pin "2") (pinfunction "1_NC_2") (pintype "passive"))
    )
    (net (code "378") (name "unconnected-(U140-2_NC-Pad4)") (class "Default")
      (node (ref "U140") (pin "4") (pinfunction "2_NC_4") (pintype "passive"))
    )
    (net (code "379") (name "unconnected-(U141-1_NC-Pad2)") (class "Default")
      (node (ref "U141") (pin "2") (pinfunction "1_NC_2") (pintype "passive"))
    )
    (net (code "380") (name "unconnected-(U141-2_NC-Pad4)") (class "Default")
      (node (ref "U141") (pin "4") (pinfunction "2_NC_4") (pintype "passive"))
    )
    (net (code "381") (name "unconnected-(U142-1_NC-Pad2)") (class "Default")
      (node (ref "U142") (pin "2") (pinfunction "1_NC_2") (pintype "passive"))
    )
    (net (code "382") (name "unconnected-(U142-2_NC-Pad4)") (class "Default")
      (node (ref "U142") (pin "4") (pinfunction "2_NC_4") (pintype "passive"))
    )
    (net (code "383") (name "unconnected-(U143-1_NC-Pad2)") (class "Default")
      (node (ref "U143") (pin "2") (pinfunction "1_NC_2") (pintype "passive"))
    )
    (net (code "384") (name "unconnected-(U143-2_NC-Pad4)") (class "Default")
      (node (ref "U143") (pin "4") (pinfunction "2_NC_4") (pintype "passive"))
    )
    (net (code "385") (name "unconnected-(U144-1_NC-Pad2)") (class "Default")
      (node (ref "U144") (pin "2") (pinfunction "1_NC_2") (pintype "passive"))
    )
    (net (code "386") (name "unconnected-(U144-2_NC-Pad4)") (class "Default")
      (node (ref "U144") (pin "4") (pinfunction "2_NC_4") (pintype "passive"))
    )
    (net (code "387") (name "unconnected-(U145-1_NC-Pad2)") (class "Default")
      (node (ref "U145") (pin "2") (pinfunction "1_NC_2") (pintype "passive"))
    )
    (net (code "388") (name "unconnected-(U145-2_NC-Pad4)") (class "Default")
      (node (ref "U145") (pin "4") (pinfunction "2_NC_4") (pintype "passive"))
    )
    (net (code "389") (name "unconnected-(U146-1_NC-Pad2)") (class "Default")
      (node (ref "U146") (pin "2") (pinfunction "1_NC_2") (pintype "passive"))
    )
    (net (code "390") (name "unconnected-(U146-2_NC-Pad4)") (class "Default")
      (node (ref "U146") (pin "4") (pinfunction "2_NC_4") (pintype "passive"))
    )
    (net (code "391") (name "unconnected-(U147-1_NC-Pad2)") (class "Default")
      (node (ref "U147") (pin "2") (pinfunction "1_NC_2") (pintype "passive"))
    )
    (net (code "392") (name "unconnected-(U147-2_NC-Pad4)") (class "Default")
      (node (ref "U147") (pin "4") (pinfunction "2_NC_4") (pintype "passive"))
    )
    (net (code "393") (name "unconnected-(U148-1_NC-Pad2)") (class "Default")
      (node (ref "U148") (pin "2") (pinfunction "1_NC_2") (pintype "passive"))
    )
    (net (code "394") (name "unconnected-(U148-2_NC-Pad4)") (class "Default")
      (node (ref "U148") (pin "4") (pinfunction "2_NC_4") (pintype "passive"))
    )
    (net (code "395") (name "unconnected-(U149-1_NC-Pad2)") (class "Default")
      (node (ref "U149") (pin "2") (pinfunction "1_NC_2") (pintype "passive"))
    )
    (net (code "396") (name "unconnected-(U149-2_NC-Pad4)") (class "Default")
      (node (ref "U149") (pin "4") (pinfunction "2_NC_4") (pintype "passive"))
    )
    (net (code "397") (name "unconnected-(U150-1_NC-Pad2)") (class "Default")
      (node (ref "U150") (pin "2") (pinfunction "1_NC_2") (pintype "passive"))
    )
    (net (code "398") (name "unconnected-(U150-2_NC-Pad4)") (class "Default")
      (node (ref "U150") (pin "4") (pinfunction "2_NC_4") (pintype "passive"))
    )
    (net (code "399") (name "unconnected-(U151-1_NC-Pad2)") (class "Default")
      (node (ref "U151") (pin "2") (pinfunction "1_NC_2") (pintype "passive"))
    )
    (net (code "400") (name "unconnected-(U151-2_NC-Pad4)") (class "Default")
      (node (ref "U151") (pin "4") (pinfunction "2_NC_4") (pintype "passive"))
    )
    (net (code "401") (name "unconnected-(U152-1_NC-Pad2)") (class "Default")
      (node (ref "U152") (pin "2") (pinfunction "1_NC_2") (pintype "passive"))
    )
    (net (code "402") (name "unconnected-(U152-2_NC-Pad4)") (class "Default")
      (node (ref "U152") (pin "4") (pinfunction "2_NC_4") (pintype "passive"))
    )
    (net (code "403") (name "unconnected-(U153-1_NC-Pad2)") (class "Default")
      (node (ref "U153") (pin "2") (pinfunction "1_NC_2") (pintype "passive"))
    )
    (net (code "404") (name "unconnected-(U153-2_NC-Pad4)") (class "Default")
      (node (ref "U153") (pin "4") (pinfunction "2_NC_4") (pintype "passive"))
    )
    (net (code "405") (name "unconnected-(U154-1_NC-Pad2)") (class "Default")
      (node (ref "U154") (pin "2") (pinfunction "1_NC_2") (pintype "passive"))
    )
    (net (code "406") (name "unconnected-(U154-2_NC-Pad4)") (class "Default")
      (node (ref "U154") (pin "4") (pinfunction "2_NC_4") (pintype "passive"))
    )
    (net (code "407") (name "unconnected-(U155-1_NC-Pad2)") (class "Default")
      (node (ref "U155") (pin "2") (pinfunction "1_NC_2") (pintype "passive"))
    )
    (net (code "408") (name "unconnected-(U155-2_NC-Pad4)") (class "Default")
      (node (ref "U155") (pin "4") (pinfunction "2_NC_4") (pintype "passive"))
    )
    (net (code "409") (name "unconnected-(U156-1_NC-Pad2)") (class "Default")
      (node (ref "U156") (pin "2") (pinfunction "1_NC_2") (pintype "passive"))
    )
    (net (code "410") (name "unconnected-(U156-2_NC-Pad4)") (class "Default")
      (node (ref "U156") (pin "4") (pinfunction "2_NC_4") (pintype "passive"))
    )
    (net (code "411") (name "unconnected-(U157-1_NC-Pad2)") (class "Default")
      (node (ref "U157") (pin "2") (pinfunction "1_NC_2") (pintype "passive"))
    )
    (net (code "412") (name "unconnected-(U157-2_NC-Pad4)") (class "Default")
      (node (ref "U157") (pin "4") (pinfunction "2_NC_4") (pintype "passive"))
    )
    (net (code "413") (name "unconnected-(U158-1_NC-Pad2)") (class "Default")
      (node (ref "U158") (pin "2") (pinfunction "1_NC_2") (pintype "passive"))
    )
    (net (code "414") (name "unconnected-(U158-2_NC-Pad4)") (class "Default")
      (node (ref "U158") (pin "4") (pinfunction "2_NC_4") (pintype "passive"))
    )
    (net (code "415") (name "unconnected-(U159-1_NC-Pad2)") (class "Default")
      (node (ref "U159") (pin "2") (pinfunction "1_NC_2") (pintype "passive"))
    )
    (net (code "416") (name "unconnected-(U159-2_NC-Pad4)") (class "Default")
      (node (ref "U159") (pin "4") (pinfunction "2_NC_4") (pintype "passive"))
    )
    (net (code "417") (name "unconnected-(U160-1_NC-Pad2)") (class "Default")
      (node (ref "U160") (pin "2") (pinfunction "1_NC_2") (pintype "passive"))
    )
    (net (code "418") (name "unconnected-(U160-2_NC-Pad4)") (class "Default")
      (node (ref "U160") (pin "4") (pinfunction "2_NC_4") (pintype "passive"))
    )
    (net (code "419") (name "unconnected-(U161-1_NC-Pad2)") (class "Default")
      (node (ref "U161") (pin "2") (pinfunction "1_NC_2") (pintype "passive"))
    )
    (net (code "420") (name "unconnected-(U161-2_NC-Pad4)") (class "Default")
      (node (ref "U161") (pin "4") (pinfunction "2_NC_4") (pintype "passive"))
    )
    (net (code "421") (name "unconnected-(U162-1_NC-Pad2)") (class "Default")
      (node (ref "U162") (pin "2") (pinfunction "1_NC_2") (pintype "passive"))
    )
    (net (code "422") (name "unconnected-(U162-2_NC-Pad4)") (class "Default")
      (node (ref "U162") (pin "4") (pinfunction "2_NC_4") (pintype "passive"))
    )
    (net (code "423") (name "unconnected-(U163-1_NC-Pad2)") (class "Default")
      (node (ref "U163") (pin "2") (pinfunction "1_NC_2") (pintype "passive"))
    )
    (net (code "424") (name "unconnected-(U163-2_NC-Pad4)") (class "Default")
      (node (ref "U163") (pin "4") (pinfunction "2_NC_4") (pintype "passive"))
    )
    (net (code "425") (name "unconnected-(U164-1_NC-Pad2)") (class "Default")
      (node (ref "U164") (pin "2") (pinfunction "1_NC_2") (pintype "passive"))
    )
    (net (code "426") (name "unconnected-(U164-2_NC-Pad4)") (class "Default")
      (node (ref "U164") (pin "4") (pinfunction "2_NC_4") (pintype "passive"))
    )
    (net (code "427") (name "unconnected-(U165-1_NC-Pad2)") (class "Default")
      (node (ref "U165") (pin "2") (pinfunction "1_NC_2") (pintype "passive"))
    )
    (net (code "428") (name "unconnected-(U165-2_NC-Pad4)") (class "Default")
      (node (ref "U165") (pin "4") (pinfunction "2_NC_4") (pintype "passive"))
    )
    (net (code "429") (name "unconnected-(U166-1_NC-Pad2)") (class "Default")
      (node (ref "U166") (pin "2") (pinfunction "1_NC_2") (pintype "passive"))
    )
    (net (code "430") (name "unconnected-(U166-2_NC-Pad4)") (class "Default")
      (node (ref "U166") (pin "4") (pinfunction "2_NC_4") (pintype "passive"))
    )
    (net (code "431") (name "unconnected-(U167-1_NC-Pad2)") (class "Default")
      (node (ref "U167") (pin "2") (pinfunction "1_NC_2") (pintype "passive"))
    )
    (net (code "432") (name "unconnected-(U167-2_NC-Pad4)") (class "Default")
      (node (ref "U167") (pin "4") (pinfunction "2_NC_4") (pintype "passive"))
    )
    (net (code "433") (name "unconnected-(U168-1_NC-Pad2)") (class "Default")
      (node (ref "U168") (pin "2") (pinfunction "1_NC_2") (pintype "passive"))
    )
    (net (code "434") (name "unconnected-(U168-2_NC-Pad4)") (class "Default")
      (node (ref "U168") (pin "4") (pinfunction "2_NC_4") (pintype "passive"))
    )
    (net (code "435") (name "unconnected-(U169-1_NC-Pad2)") (class "Default")
      (node (ref "U169") (pin "2") (pinfunction "1_NC_2") (pintype "passive"))
    )
    (net (code "436") (name "unconnected-(U169-2_NC-Pad4)") (class "Default")
      (node (ref "U169") (pin "4") (pinfunction "2_NC_4") (pintype "passive"))
    )
    (net (code "437") (name "unconnected-(U170-1_NC-Pad2)") (class "Default")
      (node (ref "U170") (pin "2") (pinfunction "1_NC_2") (pintype "passive"))
    )
    (net (code "438") (name "unconnected-(U170-2_NC-Pad4)") (class "Default")
      (node (ref "U170") (pin "4") (pinfunction "2_NC_4") (pintype "passive"))
    )
    (net (code "439") (name "unconnected-(U171-1_NC-Pad2)") (class "Default")
      (node (ref "U171") (pin "2") (pinfunction "1_NC_2") (pintype "passive"))
    )
    (net (code "440") (name "unconnected-(U171-2_NC-Pad4)") (class "Default")
      (node (ref "U171") (pin "4") (pinfunction "2_NC_4") (pintype "passive"))
    )
    (net (code "441") (name "unconnected-(U172-1_NC-Pad2)") (class "Default")
      (node (ref "U172") (pin "2") (pinfunction "1_NC_2") (pintype "passive"))
    )
    (net (code "442") (name "unconnected-(U172-2_NC-Pad4)") (class "Default")
      (node (ref "U172") (pin "4") (pinfunction "2_NC_4") (pintype "passive"))
    )
    (net (code "443") (name "unconnected-(U173-1_NC-Pad2)") (class "Default")
      (node (ref "U173") (pin "2") (pinfunction "1_NC_2") (pintype "passive"))
    )
    (net (code "444") (name "unconnected-(U173-2_NC-Pad4)") (class "Default")
      (node (ref "U173") (pin "4") (pinfunction "2_NC_4") (pintype "passive"))
    )
    (net (code "445") (name "unconnected-(U174-1_NC-Pad2)") (class "Default")
      (node (ref "U174") (pin "2") (pinfunction "1_NC_2") (pintype "passive"))
    )
    (net (code "446") (name "unconnected-(U174-2_NC-Pad4)") (class "Default")
      (node (ref "U174") (pin "4") (pinfunction "2_NC_4") (pintype "passive"))
    )
    (net (code "447") (name "unconnected-(U175-1_NC-Pad2)") (class "Default")
      (node (ref "U175") (pin "2") (pinfunction "1_NC_2") (pintype "passive"))
    )
    (net (code "448") (name "unconnected-(U175-2_NC-Pad4)") (class "Default")
      (node (ref "U175") (pin "4") (pinfunction "2_NC_4") (pintype "passive"))
    )
    (net (code "449") (name "unconnected-(U176-1_NC-Pad2)") (class "Default")
      (node (ref "U176") (pin "2") (pinfunction "1_NC_2") (pintype "passive"))
    )
    (net (code "450") (name "unconnected-(U176-2_NC-Pad4)") (class "Default")
      (node (ref "U176") (pin "4") (pinfunction "2_NC_4") (pintype "passive"))
    )
    (net (code "451") (name "unconnected-(U177-1_NC-Pad2)") (class "Default")
      (node (ref "U177") (pin "2") (pinfunction "1_NC_2") (pintype "passive"))
    )
    (net (code "452") (name "unconnected-(U177-2_NC-Pad4)") (class "Default")
      (node (ref "U177") (pin "4") (pinfunction "2_NC_4") (pintype "passive"))
    )
    (net (code "453") (name "unconnected-(U178-1_NC-Pad2)") (class "Default")
      (node (ref "U178") (pin "2") (pinfunction "1_NC_2") (pintype "passive"))
    )
    (net (code "454") (name "unconnected-(U178-2_NC-Pad4)") (class "Default")
      (node (ref "U178") (pin "4") (pinfunction "2_NC_4") (pintype "passive"))
    )
    (net (code "455") (name "unconnected-(U179-1_NC-Pad2)") (class "Default")
      (node (ref "U179") (pin "2") (pinfunction "1_NC_2") (pintype "passive"))
    )
    (net (code "456") (name "unconnected-(U179-2_NC-Pad4)") (class "Default")
      (node (ref "U179") (pin "4") (pinfunction "2_NC_4") (pintype "passive"))
    )
    (net (code "457") (name "unconnected-(U180-1_NC-Pad2)") (class "Default")
      (node (ref "U180") (pin "2") (pinfunction "1_NC_2") (pintype "passive"))
    )
    (net (code "458") (name "unconnected-(U180-2_NC-Pad4)") (class "Default")
      (node (ref "U180") (pin "4") (pinfunction "2_NC_4") (pintype "passive"))
    )
    (net (code "459") (name "unconnected-(U184-1_NC-Pad2)") (class "Default")
      (node (ref "U184") (pin "2") (pinfunction "1_NC_2") (pintype "passive"))
    )
    (net (code "460") (name "unconnected-(U184-2_NC-Pad4)") (class "Default")
      (node (ref "U184") (pin "4") (pinfunction "2_NC_4") (pintype "passive"))
    )
    (net (code "461") (name "unconnected-(U185-1_NC-Pad2)") (class "Default")
      (node (ref "U185") (pin "2") (pinfunction "1_NC_2") (pintype "passive"))
    )
    (net (code "462") (name "unconnected-(U185-2_NC-Pad4)") (class "Default")
      (node (ref "U185") (pin "4") (pinfunction "2_NC_4") (pintype "passive"))
    )
    (net (code "463") (name "unconnected-(U186-1_NC-Pad2)") (class "Default")
      (node (ref "U186") (pin "2") (pinfunction "1_NC_2") (pintype "passive"))
    )
    (net (code "464") (name "unconnected-(U186-2_NC-Pad4)") (class "Default")
      (node (ref "U186") (pin "4") (pinfunction "2_NC_4") (pintype "passive"))
    )
    (net (code "465") (name "unconnected-(U192-1_NC-Pad2)") (class "Default")
      (node (ref "U192") (pin "2") (pinfunction "1_NC_2") (pintype "passive"))
    )
    (net (code "466") (name "unconnected-(U192-2_NC-Pad4)") (class "Default")
      (node (ref "U192") (pin "4") (pinfunction "2_NC_4") (pintype "passive"))
    )
    (net (code "467") (name "unconnected-(U193-1_NC-Pad2)") (class "Default")
      (node (ref "U193") (pin "2") (pinfunction "1_NC_2") (pintype "passive"))
    )
    (net (code "468") (name "unconnected-(U193-2_NC-Pad4)") (class "Default")
      (node (ref "U193") (pin "4") (pinfunction "2_NC_4") (pintype "passive"))
    )
    (net (code "469") (name "unconnected-(U194-1_NC-Pad2)") (class "Default")
      (node (ref "U194") (pin "2") (pinfunction "1_NC_2") (pintype "passive"))
    )
    (net (code "470") (name "unconnected-(U194-2_NC-Pad4)") (class "Default")
      (node (ref "U194") (pin "4") (pinfunction "2_NC_4") (pintype "passive"))
    )
    (net (code "471") (name "unconnected-(U195-1_NC-Pad2)") (class "Default")
      (node (ref "U195") (pin "2") (pinfunction "1_NC_2") (pintype "passive"))
    )
    (net (code "472") (name "unconnected-(U195-2_NC-Pad4)") (class "Default")
      (node (ref "U195") (pin "4") (pinfunction "2_NC_4") (pintype "passive"))
    )
    (net (code "473") (name "unconnected-(U196-1_NC-Pad2)") (class "Default")
      (node (ref "U196") (pin "2") (pinfunction "1_NC_2") (pintype "passive"))
    )
    (net (code "474") (name "unconnected-(U196-2_NC-Pad4)") (class "Default")
      (node (ref "U196") (pin "4") (pinfunction "2_NC_4") (pintype "passive"))
    )
    (net (code "475") (name "unconnected-(U197-1_NC-Pad2)") (class "Default")
      (node (ref "U197") (pin "2") (pinfunction "1_NC_2") (pintype "passive"))
    )
    (net (code "476") (name "unconnected-(U197-2_NC-Pad4)") (class "Default")
      (node (ref "U197") (pin "4") (pinfunction "2_NC_4") (pintype "passive"))
    )
    (net (code "477") (name "unconnected-(U198-1_NC-Pad2)") (class "Default")
      (node (ref "U198") (pin "2") (pinfunction "1_NC_2") (pintype "passive"))
    )
    (net (code "478") (name "unconnected-(U198-2_NC-Pad4)") (class "Default")
      (node (ref "U198") (pin "4") (pinfunction "2_NC_4") (pintype "passive"))
    )
    (net (code "479") (name "unconnected-(U199-1_NC-Pad2)") (class "Default")
      (node (ref "U199") (pin "2") (pinfunction "1_NC_2") (pintype "passive"))
    )
    (net (code "480") (name "unconnected-(U199-2_NC-Pad4)") (class "Default")
      (node (ref "U199") (pin "4") (pinfunction "2_NC_4") (pintype "passive"))
    )
    (net (code "481") (name "unconnected-(U200-1_NC-Pad2)") (class "Default")
      (node (ref "U200") (pin "2") (pinfunction "1_NC_2") (pintype "passive"))
    )
    (net (code "482") (name "unconnected-(U200-2_NC-Pad4)") (class "Default")
      (node (ref "U200") (pin "4") (pinfunction "2_NC_4") (pintype "passive"))
    )
    (net (code "483") (name "unconnected-(U201-1_NC-Pad2)") (class "Default")
      (node (ref "U201") (pin "2") (pinfunction "1_NC_2") (pintype "passive"))
    )
    (net (code "484") (name "unconnected-(U201-2_NC-Pad4)") (class "Default")
      (node (ref "U201") (pin "4") (pinfunction "2_NC_4") (pintype "passive"))
    )
    (net (code "485") (name "unconnected-(U202-1_NC-Pad2)") (class "Default")
      (node (ref "U202") (pin "2") (pinfunction "1_NC_2") (pintype "passive"))
    )
    (net (code "486") (name "unconnected-(U202-2_NC-Pad4)") (class "Default")
      (node (ref "U202") (pin "4") (pinfunction "2_NC_4") (pintype "passive"))
    )
    (net (code "487") (name "unconnected-(U203-1_NC-Pad2)") (class "Default")
      (node (ref "U203") (pin "2") (pinfunction "1_NC_2") (pintype "passive"))
    )
    (net (code "488") (name "unconnected-(U203-2_NC-Pad4)") (class "Default")
      (node (ref "U203") (pin "4") (pinfunction "2_NC_4") (pintype "passive"))
    )
    (net (code "489") (name "unconnected-(U204-1_NC-Pad2)") (class "Default")
      (node (ref "U204") (pin "2") (pinfunction "1_NC_2") (pintype "passive"))
    )
    (net (code "490") (name "unconnected-(U204-2_NC-Pad4)") (class "Default")
      (node (ref "U204") (pin "4") (pinfunction "2_NC_4") (pintype "passive"))
    )
    (net (code "491") (name "unconnected-(U205-1_NC-Pad2)") (class "Default")
      (node (ref "U205") (pin "2") (pinfunction "1_NC_2") (pintype "passive"))
    )
    (net (code "492") (name "unconnected-(U205-2_NC-Pad4)") (class "Default")
      (node (ref "U205") (pin "4") (pinfunction "2_NC_4") (pintype "passive"))
    )
    (net (code "493") (name "unconnected-(U206-1_NC-Pad2)") (class "Default")
      (node (ref "U206") (pin "2") (pinfunction "1_NC_2") (pintype "passive"))
    )
    (net (code "494") (name "unconnected-(U206-2_NC-Pad4)") (class "Default")
      (node (ref "U206") (pin "4") (pinfunction "2_NC_4") (pintype "passive"))
    )
    (net (code "495") (name "unconnected-(U207-1_NC-Pad2)") (class "Default")
      (node (ref "U207") (pin "2") (pinfunction "1_NC_2") (pintype "passive"))
    )
    (net (code "496") (name "unconnected-(U207-2_NC-Pad4)") (class "Default")
      (node (ref "U207") (pin "4") (pinfunction "2_NC_4") (pintype "passive"))
    )
    (net (code "497") (name "unconnected-(U208-1_NC-Pad2)") (class "Default")
      (node (ref "U208") (pin "2") (pinfunction "1_NC_2") (pintype "passive"))
    )
    (net (code "498") (name "unconnected-(U208-2_NC-Pad4)") (class "Default")
      (node (ref "U208") (pin "4") (pinfunction "2_NC_4") (pintype "passive"))
    )
    (net (code "499") (name "unconnected-(U209-1_NC-Pad2)") (class "Default")
      (node (ref "U209") (pin "2") (pinfunction "1_NC_2") (pintype "passive"))
    )
    (net (code "500") (name "unconnected-(U209-2_NC-Pad4)") (class "Default")
      (node (ref "U209") (pin "4") (pinfunction "2_NC_4") (pintype "passive"))
    )
    (net (code "501") (name "unconnected-(U210-1_NC-Pad2)") (class "Default")
      (node (ref "U210") (pin "2") (pinfunction "1_NC_2") (pintype "passive"))
    )
    (net (code "502") (name "unconnected-(U210-2_NC-Pad4)") (class "Default")
      (node (ref "U210") (pin "4") (pinfunction "2_NC_4") (pintype "passive"))
    )
    (net (code "503") (name "unconnected-(U211-1_NC-Pad2)") (class "Default")
      (node (ref "U211") (pin "2") (pinfunction "1_NC_2") (pintype "passive"))
    )
    (net (code "504") (name "unconnected-(U211-2_NC-Pad4)") (class "Default")
      (node (ref "U211") (pin "4") (pinfunction "2_NC_4") (pintype "passive"))
    )
    (net (code "505") (name "unconnected-(U212-1_NC-Pad2)") (class "Default")
      (node (ref "U212") (pin "2") (pinfunction "1_NC_2") (pintype "passive"))
    )
    (net (code "506") (name "unconnected-(U212-2_NC-Pad4)") (class "Default")
      (node (ref "U212") (pin "4") (pinfunction "2_NC_4") (pintype "passive"))
    )
    (net (code "507") (name "unconnected-(U213-1_NC-Pad2)") (class "Default")
      (node (ref "U213") (pin "2") (pinfunction "1_NC_2") (pintype "passive"))
    )
    (net (code "508") (name "unconnected-(U213-2_NC-Pad4)") (class "Default")
      (node (ref "U213") (pin "4") (pinfunction "2_NC_4") (pintype "passive"))
    )
    (net (code "509") (name "unconnected-(U214-1_NC-Pad2)") (class "Default")
      (node (ref "U214") (pin "2") (pinfunction "1_NC_2") (pintype "passive"))
    )
    (net (code "510") (name "unconnected-(U214-2_NC-Pad4)") (class "Default")
      (node (ref "U214") (pin "4") (pinfunction "2_NC_4") (pintype "passive"))
    )
    (net (code "511") (name "unconnected-(U215-1_NC-Pad2)") (class "Default")
      (node (ref "U215") (pin "2") (pinfunction "1_NC_2") (pintype "passive"))
    )
    (net (code "512") (name "unconnected-(U215-2_NC-Pad4)") (class "Default")
      (node (ref "U215") (pin "4") (pinfunction "2_NC_4") (pintype "passive"))
    )
    (net (code "513") (name "unconnected-(U216-1_NC-Pad2)") (class "Default")
      (node (ref "U216") (pin "2") (pinfunction "1_NC_2") (pintype "passive"))
    )
    (net (code "514") (name "unconnected-(U216-2_NC-Pad4)") (class "Default")
      (node (ref "U216") (pin "4") (pinfunction "2_NC_4") (pintype "passive"))
    )
    (net (code "515") (name "unconnected-(U217-1_NC-Pad2)") (class "Default")
      (node (ref "U217") (pin "2") (pinfunction "1_NC_2") (pintype "passive"))
    )
    (net (code "516") (name "unconnected-(U217-2_NC-Pad4)") (class "Default")
      (node (ref "U217") (pin "4") (pinfunction "2_NC_4") (pintype "passive"))
    )
    (net (code "517") (name "unconnected-(U218-1_NC-Pad2)") (class "Default")
      (node (ref "U218") (pin "2") (pinfunction "1_NC_2") (pintype "passive"))
    )
    (net (code "518") (name "unconnected-(U218-2_NC-Pad4)") (class "Default")
      (node (ref "U218") (pin "4") (pinfunction "2_NC_4") (pintype "passive"))
    )
    (net (code "519") (name "unconnected-(U219-1_NC-Pad2)") (class "Default")
      (node (ref "U219") (pin "2") (pinfunction "1_NC_2") (pintype "passive"))
    )
    (net (code "520") (name "unconnected-(U219-2_NC-Pad4)") (class "Default")
      (node (ref "U219") (pin "4") (pinfunction "2_NC_4") (pintype "passive"))
    )
    (net (code "521") (name "unconnected-(U220-1_NC-Pad2)") (class "Default")
      (node (ref "U220") (pin "2") (pinfunction "1_NC_2") (pintype "passive"))
    )
    (net (code "522") (name "unconnected-(U220-2_NC-Pad4)") (class "Default")
      (node (ref "U220") (pin "4") (pinfunction "2_NC_4") (pintype "passive"))
    )
    (net (code "523") (name "unconnected-(U221-1_NC-Pad2)") (class "Default")
      (node (ref "U221") (pin "2") (pinfunction "1_NC_2") (pintype "passive"))
    )
    (net (code "524") (name "unconnected-(U221-2_NC-Pad4)") (class "Default")
      (node (ref "U221") (pin "4") (pinfunction "2_NC_4") (pintype "passive"))
    )
    (net (code "525") (name "unconnected-(U222-1_NC-Pad2)") (class "Default")
      (node (ref "U222") (pin "2") (pinfunction "1_NC_2") (pintype "passive"))
    )
    (net (code "526") (name "unconnected-(U222-2_NC-Pad4)") (class "Default")
      (node (ref "U222") (pin "4") (pinfunction "2_NC_4") (pintype "passive"))
    )
    (net (code "527") (name "unconnected-(U223-1_NC-Pad2)") (class "Default")
      (node (ref "U223") (pin "2") (pinfunction "1_NC_2") (pintype "passive"))
    )
    (net (code "528") (name "unconnected-(U223-2_NC-Pad4)") (class "Default")
      (node (ref "U223") (pin "4") (pinfunction "2_NC_4") (pintype "passive"))
    )
    (net (code "529") (name "unconnected-(U224-1_NC-Pad2)") (class "Default")
      (node (ref "U224") (pin "2") (pinfunction "1_NC_2") (pintype "passive"))
    )
    (net (code "530") (name "unconnected-(U224-2_NC-Pad4)") (class "Default")
      (node (ref "U224") (pin "4") (pinfunction "2_NC_4") (pintype "passive"))
    )
    (net (code "531") (name "unconnected-(U225-1_NC-Pad2)") (class "Default")
      (node (ref "U225") (pin "2") (pinfunction "1_NC_2") (pintype "passive"))
    )
    (net (code "532") (name "unconnected-(U225-2_NC-Pad4)") (class "Default")
      (node (ref "U225") (pin "4") (pinfunction "2_NC_4") (pintype "passive"))
    )
    (net (code "533") (name "unconnected-(U226-1_NC-Pad2)") (class "Default")
      (node (ref "U226") (pin "2") (pinfunction "1_NC_2") (pintype "passive"))
    )
    (net (code "534") (name "unconnected-(U226-2_NC-Pad4)") (class "Default")
      (node (ref "U226") (pin "4") (pinfunction "2_NC_4") (pintype "passive"))
    )
    (net (code "535") (name "unconnected-(U227-1_NC-Pad2)") (class "Default")
      (node (ref "U227") (pin "2") (pinfunction "1_NC_2") (pintype "passive"))
    )
    (net (code "536") (name "unconnected-(U227-2_NC-Pad4)") (class "Default")
      (node (ref "U227") (pin "4") (pinfunction "2_NC_4") (pintype "passive"))
    )
    (net (code "537") (name "unconnected-(U228-1_NC-Pad2)") (class "Default")
      (node (ref "U228") (pin "2") (pinfunction "1_NC_2") (pintype "passive"))
    )
    (net (code "538") (name "unconnected-(U228-2_NC-Pad4)") (class "Default")
      (node (ref "U228") (pin "4") (pinfunction "2_NC_4") (pintype "passive"))
    )
    (net (code "539") (name "unconnected-(U229-1_NC-Pad2)") (class "Default")
      (node (ref "U229") (pin "2") (pinfunction "1_NC_2") (pintype "passive"))
    )
    (net (code "540") (name "unconnected-(U229-2_NC-Pad4)") (class "Default")
      (node (ref "U229") (pin "4") (pinfunction "2_NC_4") (pintype "passive"))
    )
    (net (code "541") (name "unconnected-(U230-1_NC-Pad2)") (class "Default")
      (node (ref "U230") (pin "2") (pinfunction "1_NC_2") (pintype "passive"))
    )
    (net (code "542") (name "unconnected-(U230-2_NC-Pad4)") (class "Default")
      (node (ref "U230") (pin "4") (pinfunction "2_NC_4") (pintype "passive"))
    )
    (net (code "543") (name "unconnected-(U231-1_NC-Pad2)") (class "Default")
      (node (ref "U231") (pin "2") (pinfunction "1_NC_2") (pintype "passive"))
    )
    (net (code "544") (name "unconnected-(U231-2_NC-Pad4)") (class "Default")
      (node (ref "U231") (pin "4") (pinfunction "2_NC_4") (pintype "passive"))
    )
    (net (code "545") (name "unconnected-(U232-1_NC-Pad2)") (class "Default")
      (node (ref "U232") (pin "2") (pinfunction "1_NC_2") (pintype "passive"))
    )
    (net (code "546") (name "unconnected-(U232-2_NC-Pad4)") (class "Default")
      (node (ref "U232") (pin "4") (pinfunction "2_NC_4") (pintype "passive"))
    )
    (net (code "547") (name "unconnected-(U233-1_NC-Pad2)") (class "Default")
      (node (ref "U233") (pin "2") (pinfunction "1_NC_2") (pintype "passive"))
    )
    (net (code "548") (name "unconnected-(U233-2_NC-Pad4)") (class "Default")
      (node (ref "U233") (pin "4") (pinfunction "2_NC_4") (pintype "passive"))
    )
    (net (code "549") (name "unconnected-(U234-1_NC-Pad2)") (class "Default")
      (node (ref "U234") (pin "2") (pinfunction "1_NC_2") (pintype "passive"))
    )
    (net (code "550") (name "unconnected-(U234-2_NC-Pad4)") (class "Default")
      (node (ref "U234") (pin "4") (pinfunction "2_NC_4") (pintype "passive"))
    )
    (net (code "551") (name "unconnected-(U235-1_NC-Pad2)") (class "Default")
      (node (ref "U235") (pin "2") (pinfunction "1_NC_2") (pintype "passive"))
    )
    (net (code "552") (name "unconnected-(U235-2_NC-Pad4)") (class "Default")
      (node (ref "U235") (pin "4") (pinfunction "2_NC_4") (pintype "passive"))
    )
    (net (code "553") (name "unconnected-(U236-1_NC-Pad2)") (class "Default")
      (node (ref "U236") (pin "2") (pinfunction "1_NC_2") (pintype "passive"))
    )
    (net (code "554") (name "unconnected-(U236-2_NC-Pad4)") (class "Default")
      (node (ref "U236") (pin "4") (pinfunction "2_NC_4") (pintype "passive"))
    )
    (net (code "555") (name "unconnected-(U237-1_NC-Pad2)") (class "Default")
      (node (ref "U237") (pin "2") (pinfunction "1_NC_2") (pintype "passive"))
    )
    (net (code "556") (name "unconnected-(U237-2_NC-Pad4)") (class "Default")
      (node (ref "U237") (pin "4") (pinfunction "2_NC_4") (pintype "passive"))
    )
    (net (code "557") (name "unconnected-(U238-1_NC-Pad2)") (class "Default")
      (node (ref "U238") (pin "2") (pinfunction "1_NC_2") (pintype "passive"))
    )
    (net (code "558") (name "unconnected-(U238-2_NC-Pad4)") (class "Default")
      (node (ref "U238") (pin "4") (pinfunction "2_NC_4") (pintype "passive"))
    )
    (net (code "559") (name "unconnected-(U239-1_NC-Pad2)") (class "Default")
      (node (ref "U239") (pin "2") (pinfunction "1_NC_2") (pintype "passive"))
    )
    (net (code "560") (name "unconnected-(U239-2_NC-Pad4)") (class "Default")
      (node (ref "U239") (pin "4") (pinfunction "2_NC_4") (pintype "passive"))
    )
    (net (code "561") (name "unconnected-(U240-1_NC-Pad2)") (class "Default")
      (node (ref "U240") (pin "2") (pinfunction "1_NC_2") (pintype "passive"))
    )
    (net (code "562") (name "unconnected-(U240-2_NC-Pad4)") (class "Default")
      (node (ref "U240") (pin "4") (pinfunction "2_NC_4") (pintype "passive"))
    )
    (net (code "563") (name "unconnected-(U241-1_NC-Pad2)") (class "Default")
      (node (ref "U241") (pin "2") (pinfunction "1_NC_2") (pintype "passive"))
    )
    (net (code "564") (name "unconnected-(U241-2_NC-Pad4)") (class "Default")
      (node (ref "U241") (pin "4") (pinfunction "2_NC_4") (pintype "passive"))
    )
    (net (code "565") (name "unconnected-(U242-1_NC-Pad2)") (class "Default")
      (node (ref "U242") (pin "2") (pinfunction "1_NC_2") (pintype "passive"))
    )
    (net (code "566") (name "unconnected-(U242-2_NC-Pad4)") (class "Default")
      (node (ref "U242") (pin "4") (pinfunction "2_NC_4") (pintype "passive"))
    )
    (net (code "567") (name "unconnected-(U246-1_NC-Pad2)") (class "Default")
      (node (ref "U246") (pin "2") (pinfunction "1_NC_2") (pintype "passive"))
    )
    (net (code "568") (name "unconnected-(U246-2_NC-Pad4)") (class "Default")
      (node (ref "U246") (pin "4") (pinfunction "2_NC_4") (pintype "passive"))
    )
    (net (code "569") (name "unconnected-(U247-1_NC-Pad2)") (class "Default")
      (node (ref "U247") (pin "2") (pinfunction "1_NC_2") (pintype "passive"))
    )
    (net (code "570") (name "unconnected-(U247-2_NC-Pad4)") (class "Default")
      (node (ref "U247") (pin "4") (pinfunction "2_NC_4") (pintype "passive"))
    )
    (net (code "571") (name "unconnected-(U248-1_NC-Pad2)") (class "Default")
      (node (ref "U248") (pin "2") (pinfunction "1_NC_2") (pintype "passive"))
    )
    (net (code "572") (name "unconnected-(U248-2_NC-Pad4)") (class "Default")
      (node (ref "U248") (pin "4") (pinfunction "2_NC_4") (pintype "passive"))
    )
    (net (code "573") (name "unconnected-(U249-1_NC-Pad2)") (class "Default")
      (node (ref "U249") (pin "2") (pinfunction "1_NC_2") (pintype "passive"))
    )
    (net (code "574") (name "unconnected-(U249-2_NC-Pad4)") (class "Default")
      (node (ref "U249") (pin "4") (pinfunction "2_NC_4") (pintype "passive"))
    )
    (net (code "575") (name "unconnected-(U250-1_NC-Pad2)") (class "Default")
      (node (ref "U250") (pin "2") (pinfunction "1_NC_2") (pintype "passive"))
    )
    (net (code "576") (name "unconnected-(U250-2_NC-Pad4)") (class "Default")
      (node (ref "U250") (pin "4") (pinfunction "2_NC_4") (pintype "passive"))
    )
    (net (code "577") (name "unconnected-(U251-1_NC-Pad2)") (class "Default")
      (node (ref "U251") (pin "2") (pinfunction "1_NC_2") (pintype "passive"))
    )
    (net (code "578") (name "unconnected-(U251-2_NC-Pad4)") (class "Default")
      (node (ref "U251") (pin "4") (pinfunction "2_NC_4") (pintype "passive"))
    )
    (net (code "579") (name "unconnected-(U252-1_NC-Pad2)") (class "Default")
      (node (ref "U252") (pin "2") (pinfunction "1_NC_2") (pintype "passive"))
    )
    (net (code "580") (name "unconnected-(U252-2_NC-Pad4)") (class "Default")
      (node (ref "U252") (pin "4") (pinfunction "2_NC_4") (pintype "passive"))
    )
    (net (code "581") (name "unconnected-(U253-1_NC-Pad2)") (class "Default")
      (node (ref "U253") (pin "2") (pinfunction "1_NC_2") (pintype "passive"))
    )
    (net (code "582") (name "unconnected-(U253-2_NC-Pad4)") (class "Default")
      (node (ref "U253") (pin "4") (pinfunction "2_NC_4") (pintype "passive"))
    )
    (net (code "583") (name "unconnected-(U254-1_NC-Pad2)") (class "Default")
      (node (ref "U254") (pin "2") (pinfunction "1_NC_2") (pintype "passive"))
    )
    (net (code "584") (name "unconnected-(U254-2_NC-Pad4)") (class "Default")
      (node (ref "U254") (pin "4") (pinfunction "2_NC_4") (pintype "passive"))
    )
    (net (code "585") (name "unconnected-(U255-1_NC-Pad2)") (class "Default")
      (node (ref "U255") (pin "2") (pinfunction "1_NC_2") (pintype "passive"))
    )
    (net (code "586") (name "unconnected-(U255-2_NC-Pad4)") (class "Default")
      (node (ref "U255") (pin "4") (pinfunction "2_NC_4") (pintype "passive"))
    )
    (net (code "587") (name "unconnected-(U256-1_NC-Pad2)") (class "Default")
      (node (ref "U256") (pin "2") (pinfunction "1_NC_2") (pintype "passive"))
    )
    (net (code "588") (name "unconnected-(U256-2_NC-Pad4)") (class "Default")
      (node (ref "U256") (pin "4") (pinfunction "2_NC_4") (pintype "passive"))
    )
    (net (code "589") (name "unconnected-(U257-1_NC-Pad2)") (class "Default")
      (node (ref "U257") (pin "2") (pinfunction "1_NC_2") (pintype "passive"))
    )
    (net (code "590") (name "unconnected-(U257-2_NC-Pad4)") (class "Default")
      (node (ref "U257") (pin "4") (pinfunction "2_NC_4") (pintype "passive"))
    )
    (net (code "591") (name "unconnected-(U258-1_NC-Pad2)") (class "Default")
      (node (ref "U258") (pin "2") (pinfunction "1_NC_2") (pintype "passive"))
    )
    (net (code "592") (name "unconnected-(U258-2_NC-Pad4)") (class "Default")
      (node (ref "U258") (pin "4") (pinfunction "2_NC_4") (pintype "passive"))
    )
    (net (code "593") (name "unconnected-(U259-1_NC-Pad2)") (class "Default")
      (node (ref "U259") (pin "2") (pinfunction "1_NC_2") (pintype "passive"))
    )
    (net (code "594") (name "unconnected-(U259-2_NC-Pad4)") (class "Default")
      (node (ref "U259") (pin "4") (pinfunction "2_NC_4") (pintype "passive"))
    )
    (net (code "595") (name "unconnected-(U260-1_NC-Pad2)") (class "Default")
      (node (ref "U260") (pin "2") (pinfunction "1_NC_2") (pintype "passive"))
    )
    (net (code "596") (name "unconnected-(U260-2_NC-Pad4)") (class "Default")
      (node (ref "U260") (pin "4") (pinfunction "2_NC_4") (pintype "passive"))
    )
    (net (code "597") (name "unconnected-(U261-1_NC-Pad2)") (class "Default")
      (node (ref "U261") (pin "2") (pinfunction "1_NC_2") (pintype "passive"))
    )
    (net (code "598") (name "unconnected-(U261-2_NC-Pad4)") (class "Default")
      (node (ref "U261") (pin "4") (pinfunction "2_NC_4") (pintype "passive"))
    )
    (net (code "599") (name "unconnected-(U262-1_NC-Pad2)") (class "Default")
      (node (ref "U262") (pin "2") (pinfunction "1_NC_2") (pintype "passive"))
    )
    (net (code "600") (name "unconnected-(U262-2_NC-Pad4)") (class "Default")
      (node (ref "U262") (pin "4") (pinfunction "2_NC_4") (pintype "passive"))
    )
    (net (code "601") (name "unconnected-(U263-1_NC-Pad2)") (class "Default")
      (node (ref "U263") (pin "2") (pinfunction "1_NC_2") (pintype "passive"))
    )
    (net (code "602") (name "unconnected-(U263-2_NC-Pad4)") (class "Default")
      (node (ref "U263") (pin "4") (pinfunction "2_NC_4") (pintype "passive"))
    )
    (net (code "603") (name "unconnected-(U264-1_NC-Pad2)") (class "Default")
      (node (ref "U264") (pin "2") (pinfunction "1_NC_2") (pintype "passive"))
    )
    (net (code "604") (name "unconnected-(U264-2_NC-Pad4)") (class "Default")
      (node (ref "U264") (pin "4") (pinfunction "2_NC_4") (pintype "passive"))
    )
    (net (code "605") (name "unconnected-(U265-1_NC-Pad2)") (class "Default")
      (node (ref "U265") (pin "2") (pinfunction "1_NC_2") (pintype "passive"))
    )
    (net (code "606") (name "unconnected-(U265-2_NC-Pad4)") (class "Default")
      (node (ref "U265") (pin "4") (pinfunction "2_NC_4") (pintype "passive"))
    )
    (net (code "607") (name "unconnected-(U266-1_NC-Pad2)") (class "Default")
      (node (ref "U266") (pin "2") (pinfunction "1_NC_2") (pintype "passive"))
    )
    (net (code "608") (name "unconnected-(U266-2_NC-Pad4)") (class "Default")
      (node (ref "U266") (pin "4") (pinfunction "2_NC_4") (pintype "passive"))
    )
    (net (code "609") (name "unconnected-(U267-1_NC-Pad2)") (class "Default")
      (node (ref "U267") (pin "2") (pinfunction "1_NC_2") (pintype "passive"))
    )
    (net (code "610") (name "unconnected-(U267-2_NC-Pad4)") (class "Default")
      (node (ref "U267") (pin "4") (pinfunction "2_NC_4") (pintype "passive"))
    )
    (net (code "611") (name "unconnected-(U268-1_NC-Pad2)") (class "Default")
      (node (ref "U268") (pin "2") (pinfunction "1_NC_2") (pintype "passive"))
    )
    (net (code "612") (name "unconnected-(U268-2_NC-Pad4)") (class "Default")
      (node (ref "U268") (pin "4") (pinfunction "2_NC_4") (pintype "passive"))
    )
    (net (code "613") (name "unconnected-(U269-1_NC-Pad2)") (class "Default")
      (node (ref "U269") (pin "2") (pinfunction "1_NC_2") (pintype "passive"))
    )
    (net (code "614") (name "unconnected-(U269-2_NC-Pad4)") (class "Default")
      (node (ref "U269") (pin "4") (pinfunction "2_NC_4") (pintype "passive"))
    )
    (net (code "615") (name "unconnected-(U270-1_NC-Pad2)") (class "Default")
      (node (ref "U270") (pin "2") (pinfunction "1_NC_2") (pintype "passive"))
    )
    (net (code "616") (name "unconnected-(U270-2_NC-Pad4)") (class "Default")
      (node (ref "U270") (pin "4") (pinfunction "2_NC_4") (pintype "passive"))
    )
    (net (code "617") (name "unconnected-(U271-1_NC-Pad2)") (class "Default")
      (node (ref "U271") (pin "2") (pinfunction "1_NC_2") (pintype "passive"))
    )
    (net (code "618") (name "unconnected-(U271-2_NC-Pad4)") (class "Default")
      (node (ref "U271") (pin "4") (pinfunction "2_NC_4") (pintype "passive"))
    )
    (net (code "619") (name "unconnected-(U272-1_NC-Pad2)") (class "Default")
      (node (ref "U272") (pin "2") (pinfunction "1_NC_2") (pintype "passive"))
    )
    (net (code "620") (name "unconnected-(U272-2_NC-Pad4)") (class "Default")
      (node (ref "U272") (pin "4") (pinfunction "2_NC_4") (pintype "passive"))
    )
    (net (code "621") (name "unconnected-(U273-1_NC-Pad2)") (class "Default")
      (node (ref "U273") (pin "2") (pinfunction "1_NC_2") (pintype "passive"))
    )
    (net (code "622") (name "unconnected-(U273-2_NC-Pad4)") (class "Default")
      (node (ref "U273") (pin "4") (pinfunction "2_NC_4") (pintype "passive"))
    )
    (net (code "623") (name "unconnected-(U274-1_NC-Pad2)") (class "Default")
      (node (ref "U274") (pin "2") (pinfunction "1_NC_2") (pintype "passive"))
    )
    (net (code "624") (name "unconnected-(U274-2_NC-Pad4)") (class "Default")
      (node (ref "U274") (pin "4") (pinfunction "2_NC_4") (pintype "passive"))
    )
    (net (code "625") (name "unconnected-(U275-1_NC-Pad2)") (class "Default")
      (node (ref "U275") (pin "2") (pinfunction "1_NC_2") (pintype "passive"))
    )
    (net (code "626") (name "unconnected-(U275-2_NC-Pad4)") (class "Default")
      (node (ref "U275") (pin "4") (pinfunction "2_NC_4") (pintype "passive"))
    )
  )
)
